# openadc_ztex.net
KiCad netlist of a schematic drawn in EAGLE
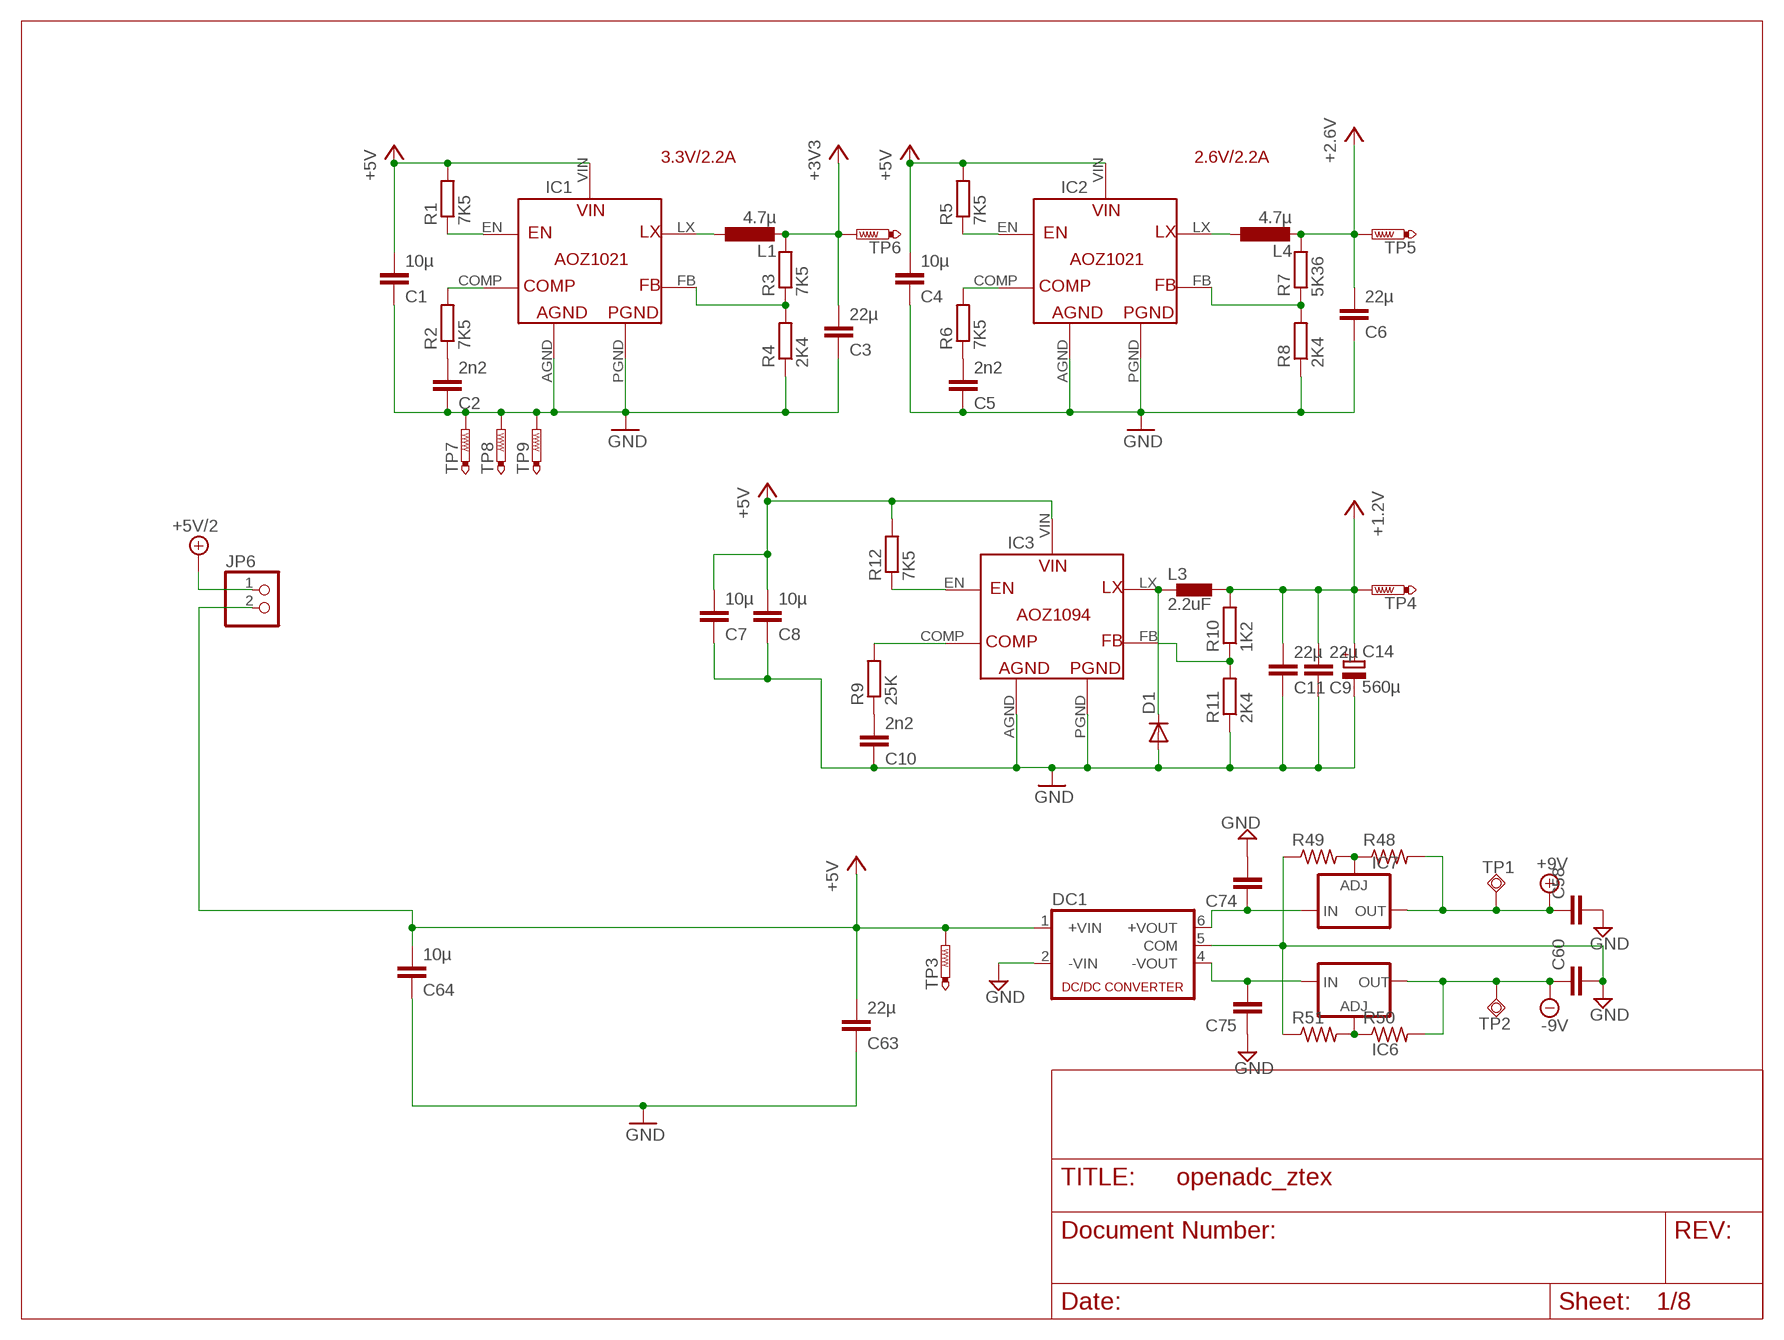
[diagram p0: schematic, sheet 1]
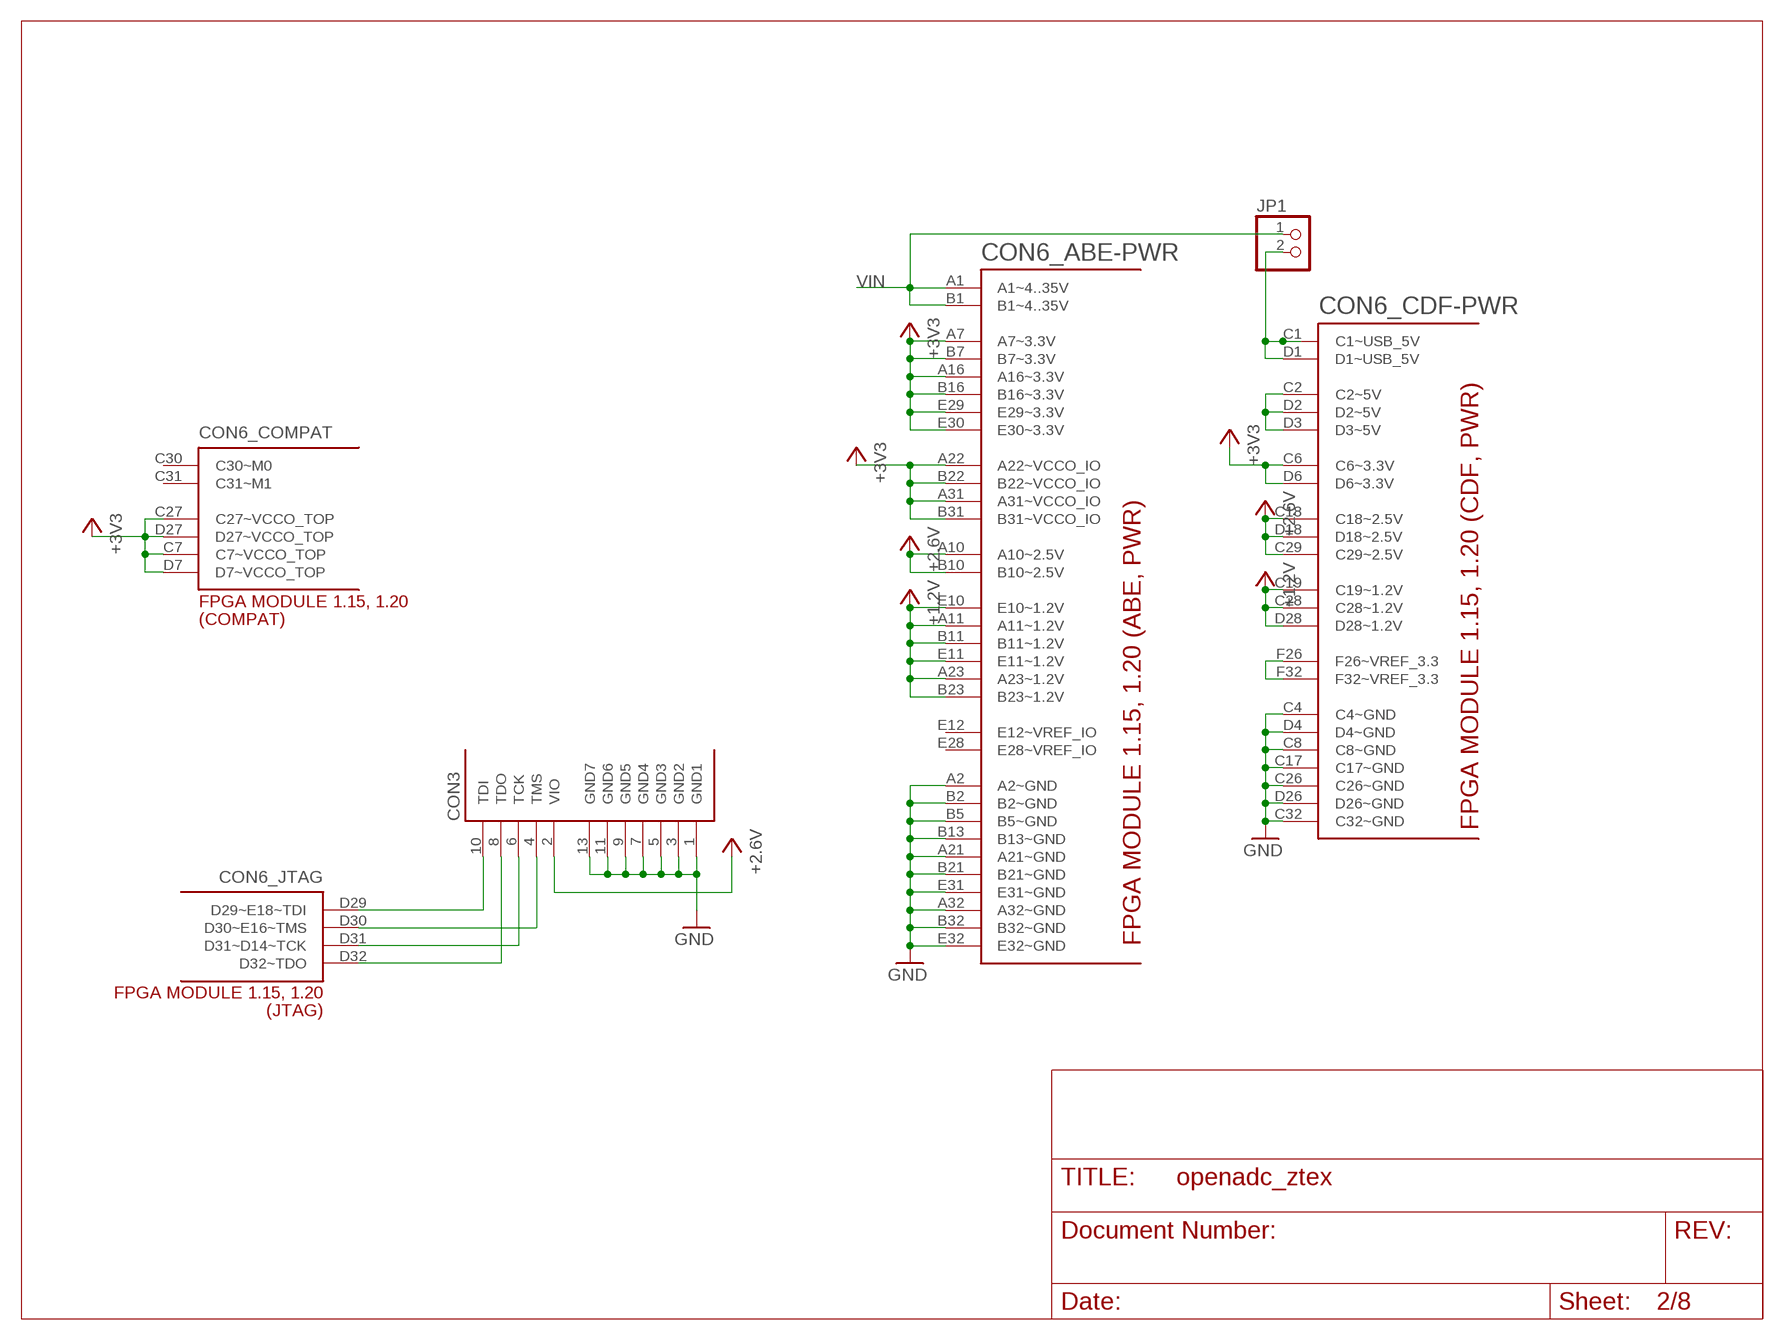
[diagram p1: schematic, sheet 2]
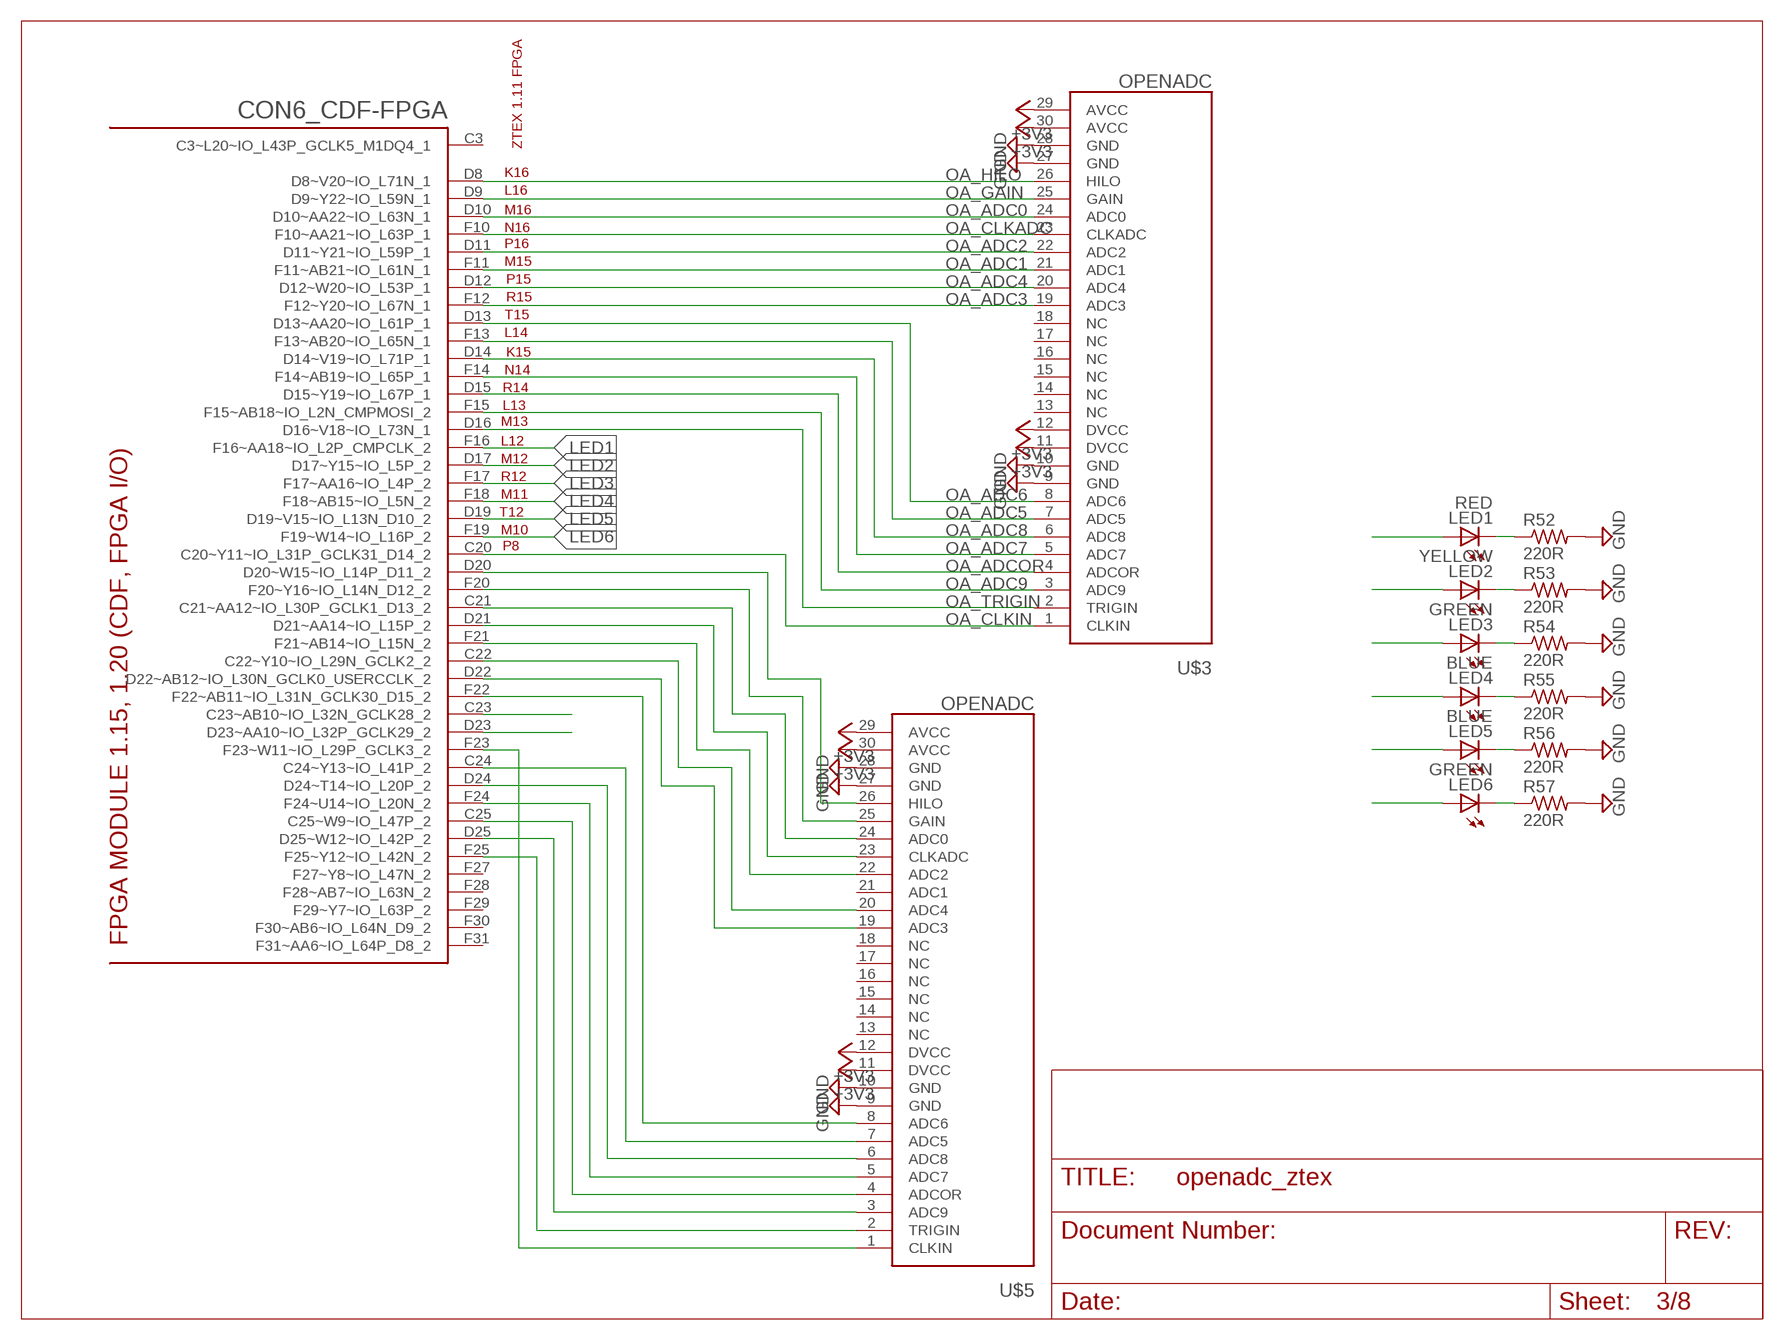
[diagram p2: schematic, sheet 3]
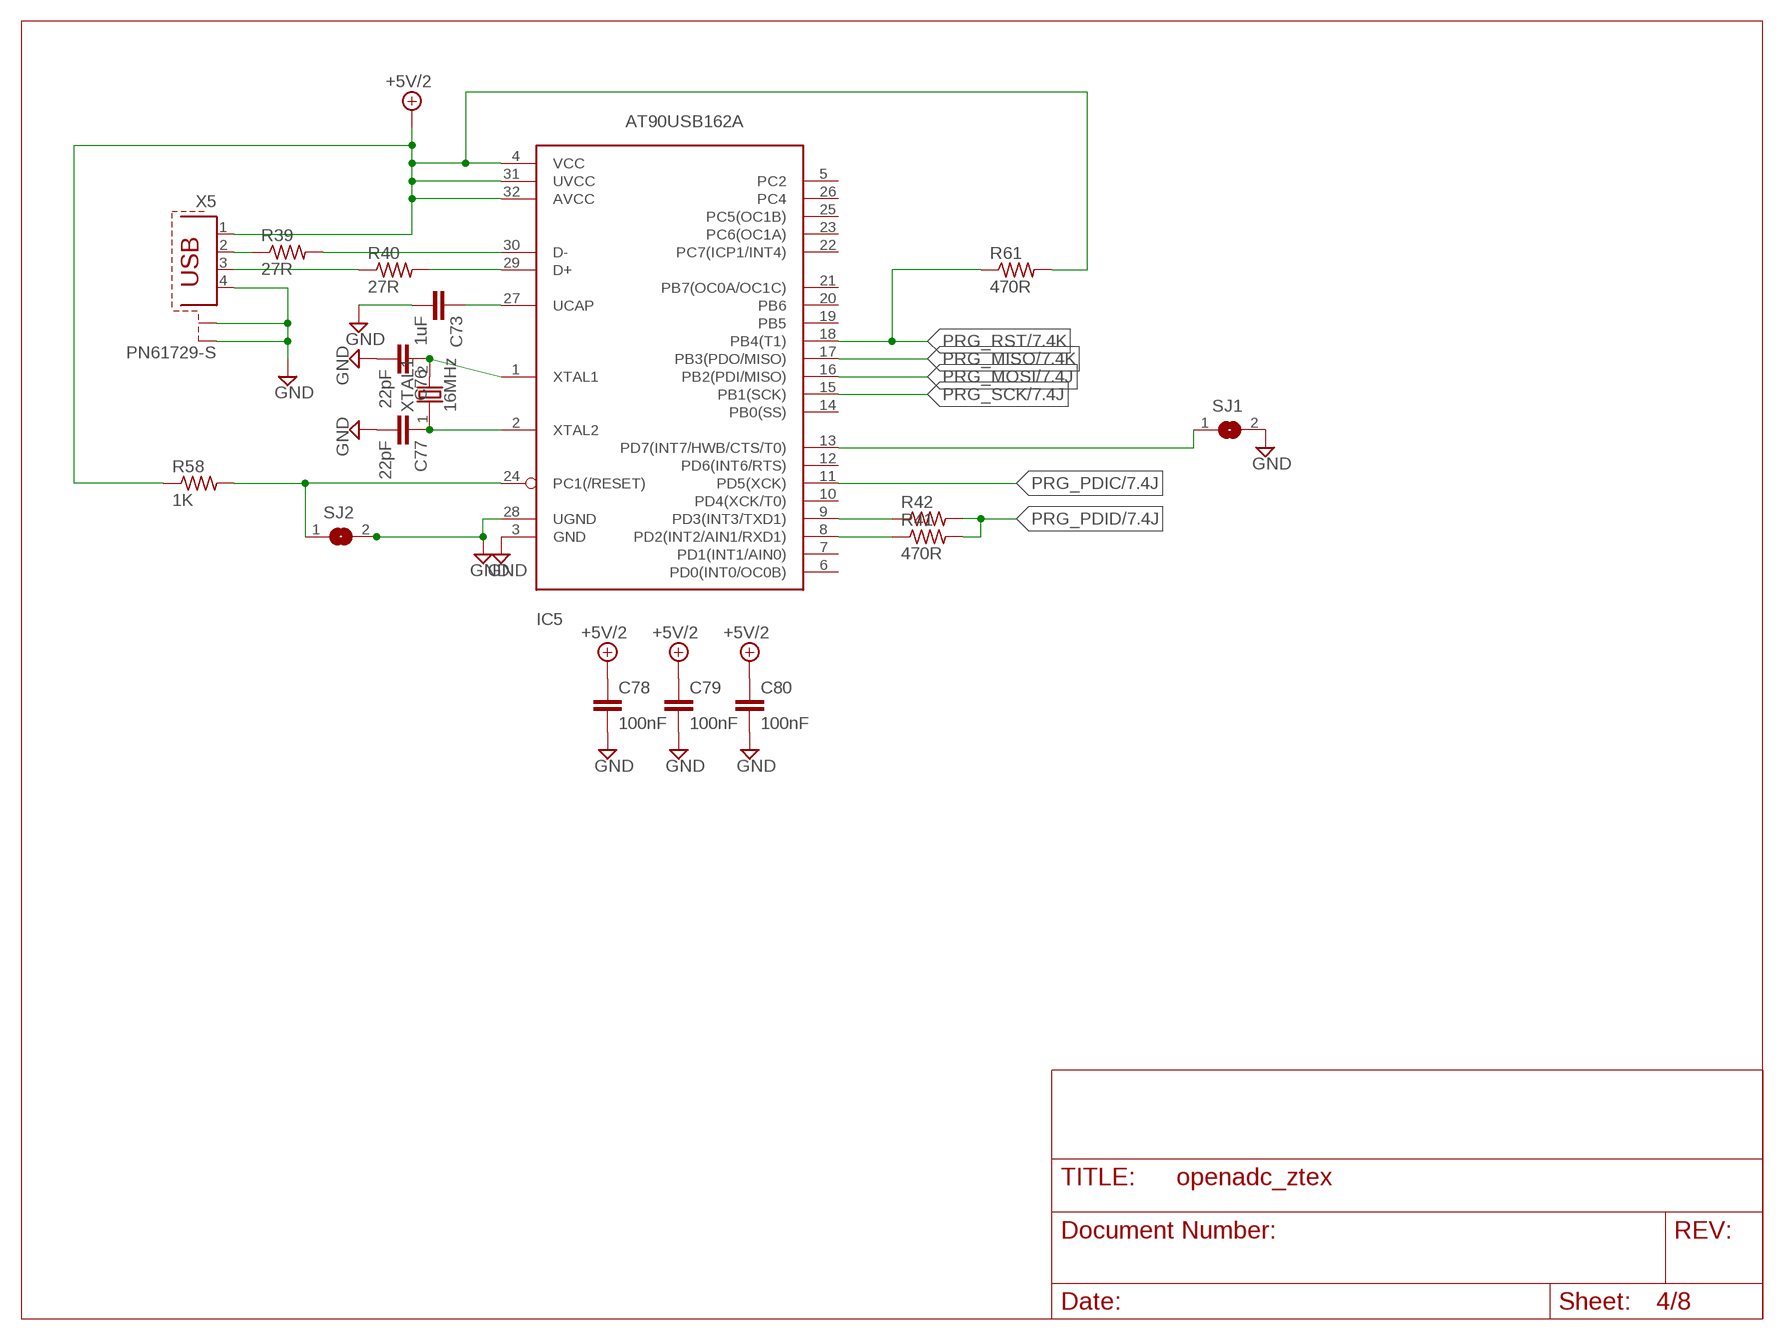
[diagram p3: schematic, sheet 4]
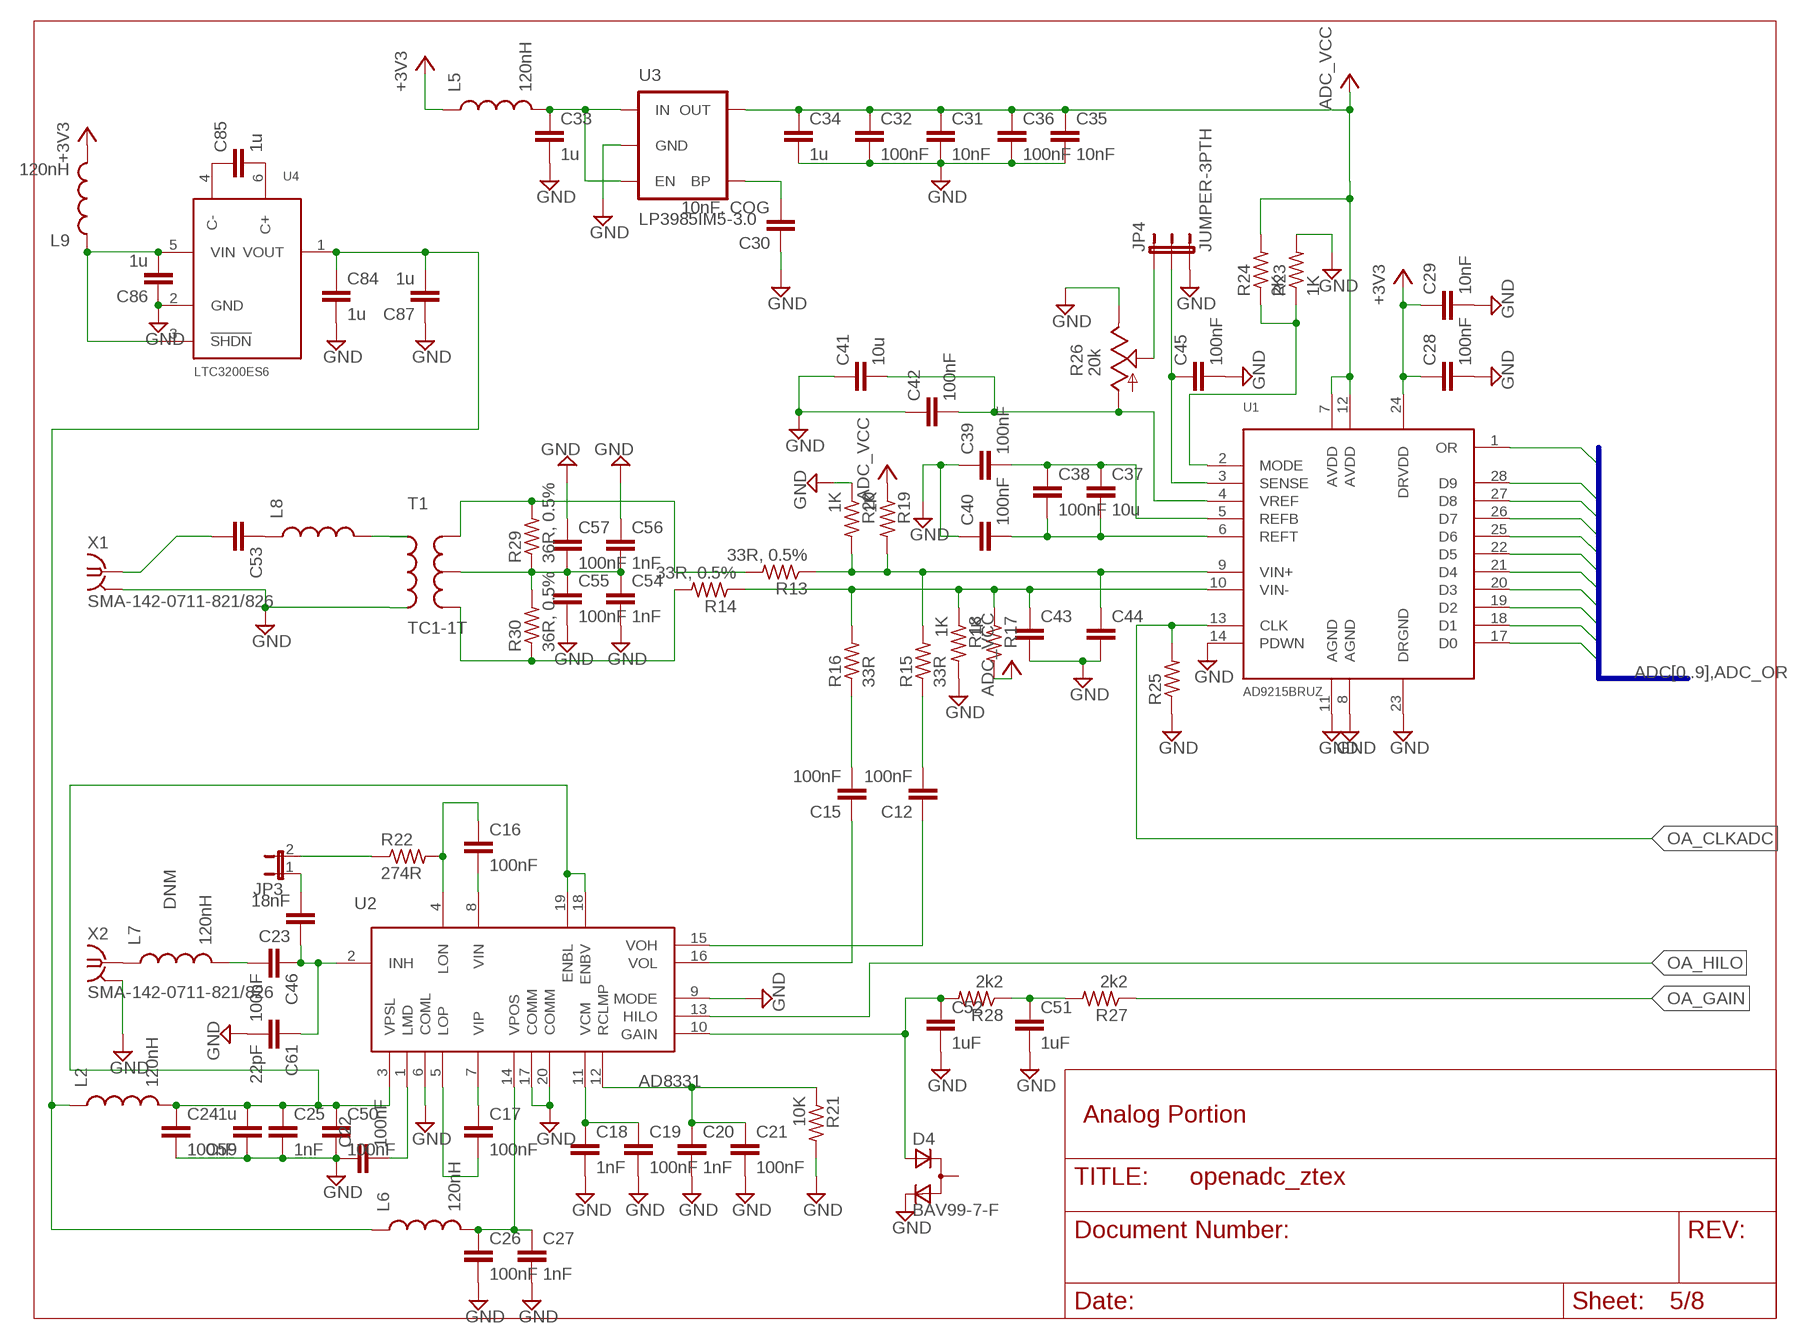
[diagram p4: schematic, sheet 5]
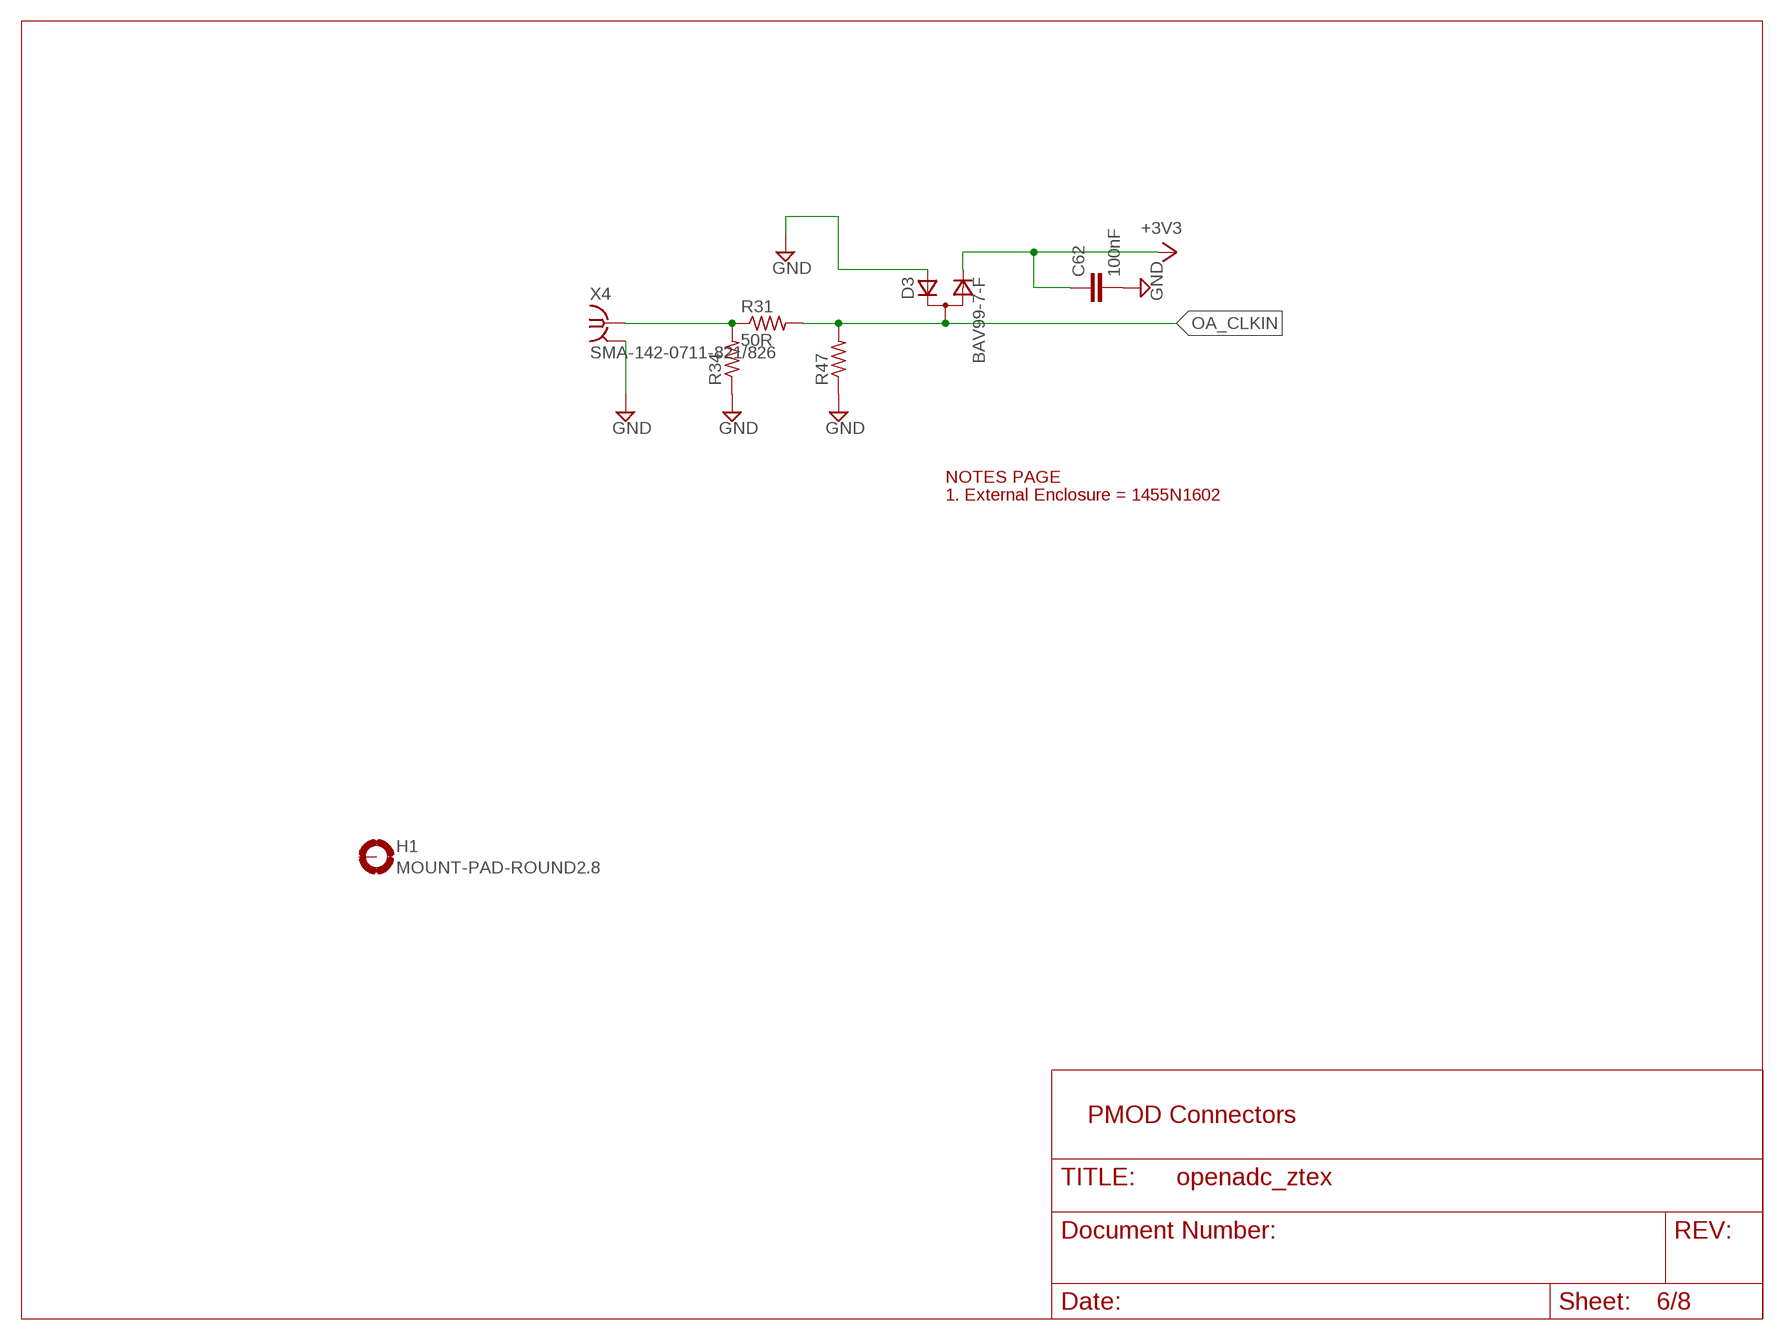
[diagram p5: schematic, sheet 6]
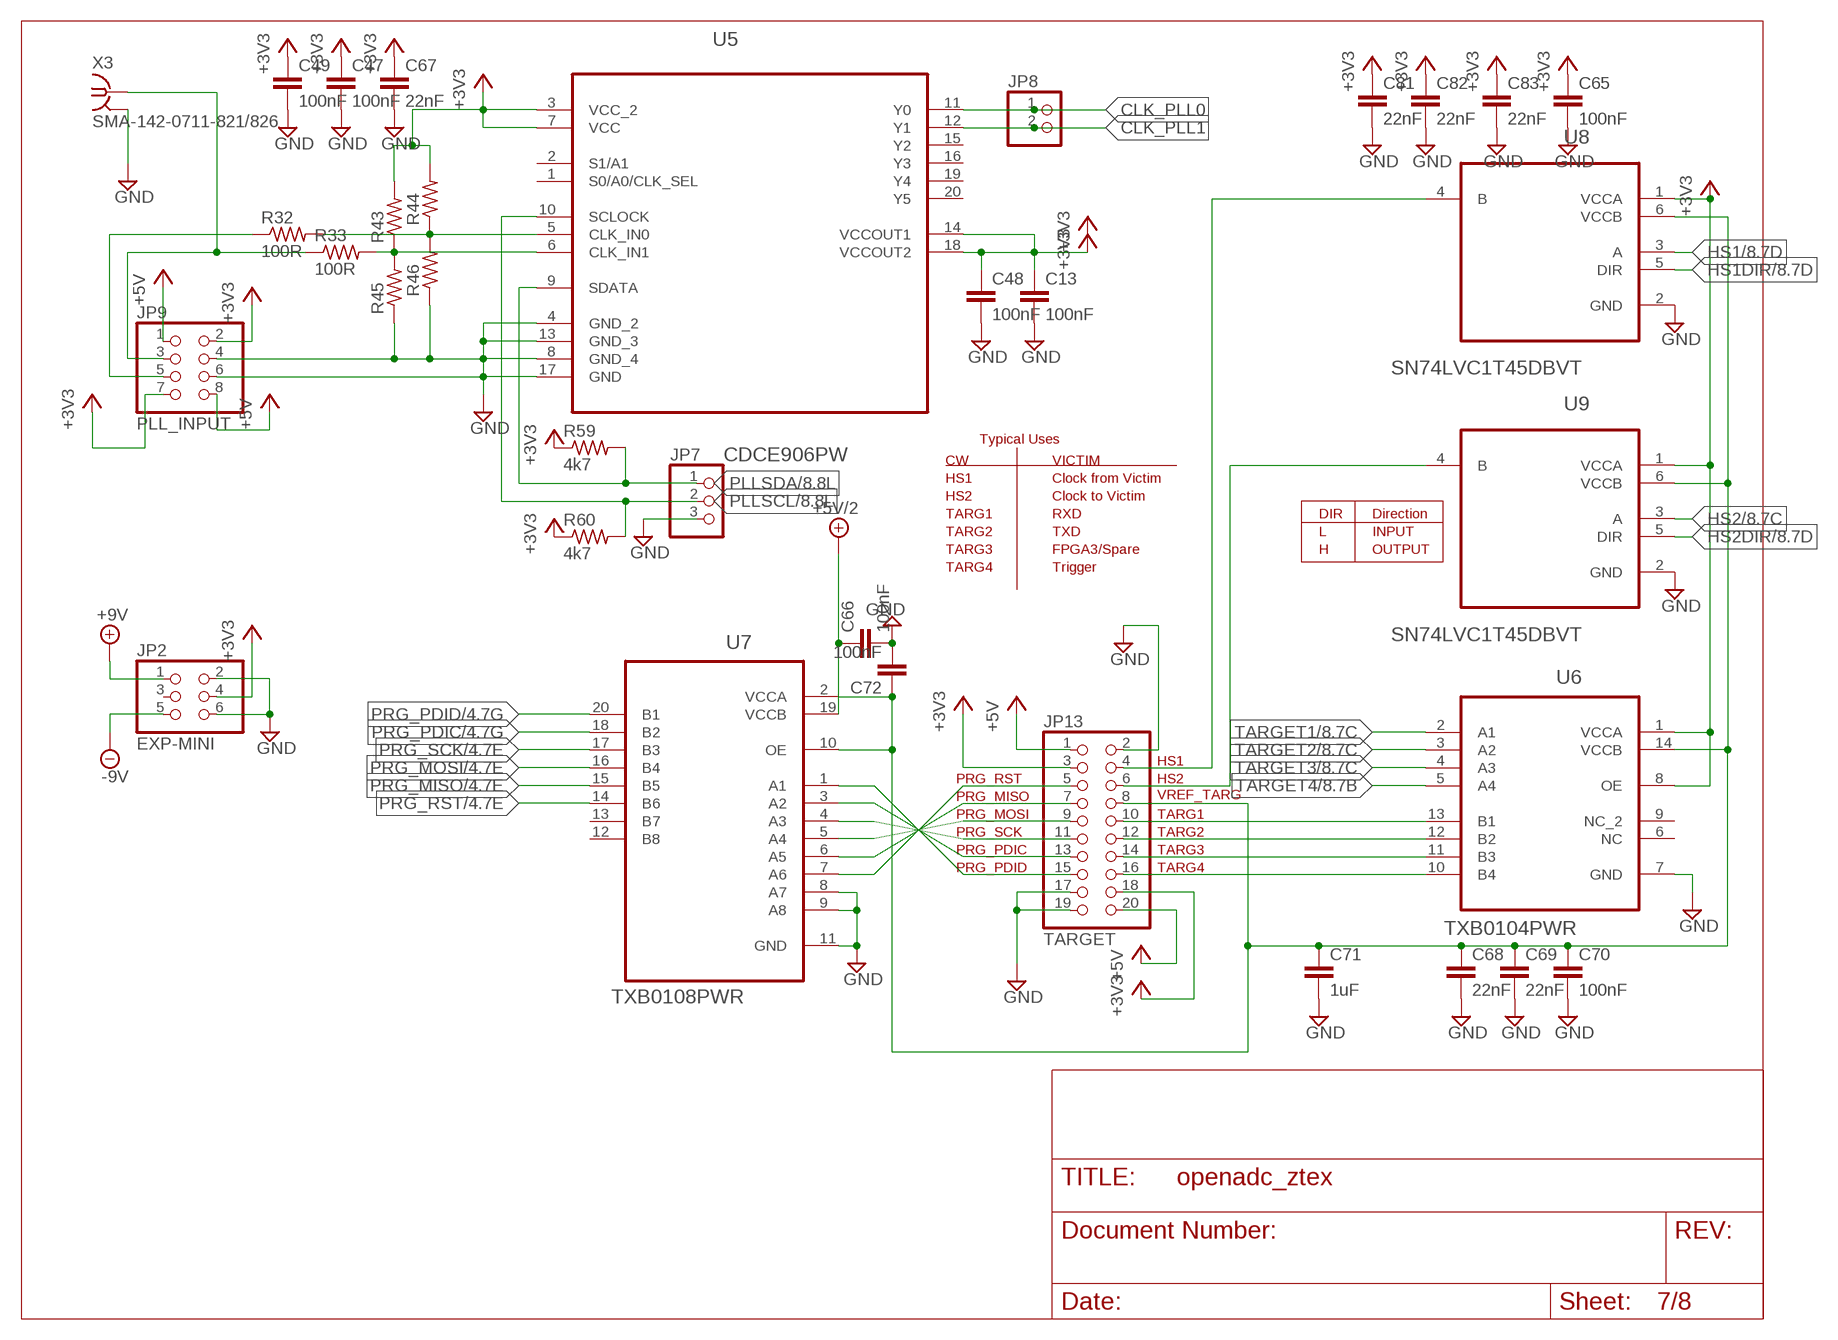
[diagram p6: schematic, sheet 7]
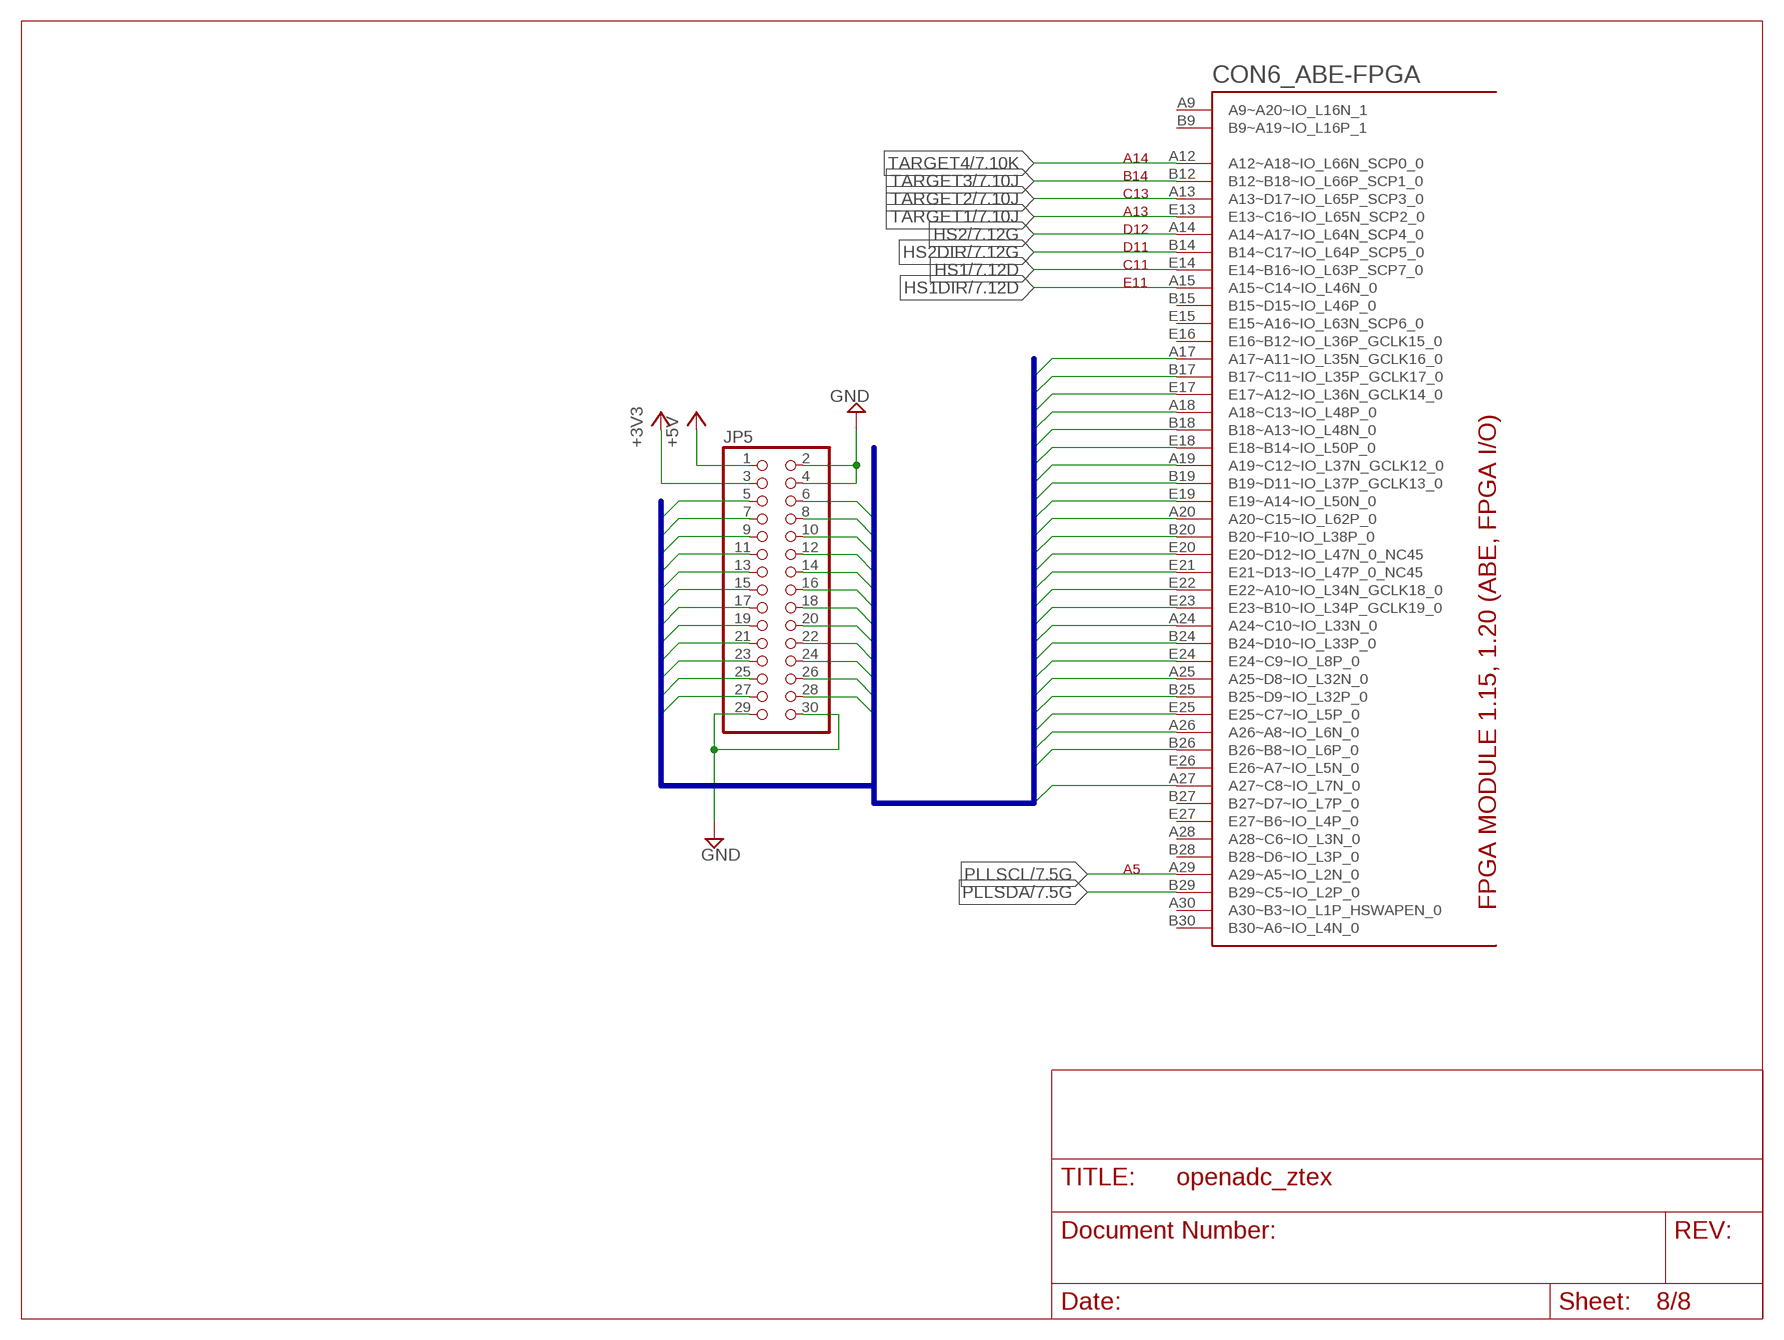
[diagram p7: schematic, sheet 8]

(export (version "E")
  (design (tool "Eeschema 10.0.6"))
  (components
    (comp (ref "C62")
      (value "100nF")
      (footprint "eagle-import:C0603")
      (libsource (lib "eagle-import") (part "C-EUC0603"))
    )
    (comp (ref "D3")
      (value "BAV99-7-F")
      (footprint "eagle-import:SOT-23")
      (libsource (lib "eagle-import") (part "D_ACACSOT23"))
    )
    (comp (ref "H1")
      (value "MOUNT-PAD-ROUND2.8")
      (footprint "eagle-import:2,8-PAD")
      (libsource (lib "eagle-import") (part "MOUNT-PAD-ROUND2.8"))
    )
    (comp (ref "R31")
      (value "50R")
      (footprint "eagle-import:R0805")
      (libsource (lib "eagle-import") (part "R-US_R0805"))
    )
    (comp (ref "R34")
      (value "R-US_R0805")
      (footprint "eagle-import:R0805")
      (libsource (lib "eagle-import") (part "R-US_R0805"))
    )
    (comp (ref "R47")
      (value "R-US_R0805")
      (footprint "eagle-import:R0805")
      (libsource (lib "eagle-import") (part "R-US_R0805"))
    )
    (comp (ref "X4")
      (value "SMA-142-0711-821/826")
      (footprint "eagle-import:J502-ND-142-0711-821_826")
      (fields (field (name "MF") "JOHNSON COMPONENTS") (field (name "MPN") "142-0711-821"))
      (libsource (lib "eagle-import") (part "SMA-142-0711-821/826"))
    )
    (comp (ref "C12")
      (value "100nF")
      (footprint "eagle-import:C0603K")
      (libsource (lib "eagle-import") (part "rcl_C-EUC0603K"))
    )
    (comp (ref "C15")
      (value "100nF")
      (footprint "eagle-import:C0603K")
      (libsource (lib "eagle-import") (part "rcl_C-EUC0603K"))
    )
    (comp (ref "C16")
      (value "100nF")
      (footprint "eagle-import:C0402")
      (libsource (lib "eagle-import") (part "rcl_C-EUC0402"))
    )
    (comp (ref "C17")
      (value "100nF")
      (footprint "eagle-import:C0402")
      (libsource (lib "eagle-import") (part "rcl_C-EUC0402"))
    )
    (comp (ref "C18")
      (value "1nF")
      (footprint "eagle-import:C0402")
      (fields (field (name "PART#") "C1005X7R1E102K"))
      (libsource (lib "eagle-import") (part "rcl_C-EUC0402"))
    )
    (comp (ref "C19")
      (value "100nF")
      (footprint "eagle-import:C0402")
      (fields (field (name "PART#") "GRM155R61A104KA01D"))
      (libsource (lib "eagle-import") (part "rcl_C-EUC0402"))
    )
    (comp (ref "C20")
      (value "1nF")
      (footprint "eagle-import:C0402")
      (fields (field (name "PART#") "C1005X7R1E102K"))
      (libsource (lib "eagle-import") (part "rcl_C-EUC0402"))
    )
    (comp (ref "C21")
      (value "100nF")
      (footprint "eagle-import:C0402")
      (fields (field (name "PART#") "GRM155R61A104KA01D"))
      (libsource (lib "eagle-import") (part "rcl_C-EUC0402"))
    )
    (comp (ref "C22")
      (value "100nF")
      (footprint "eagle-import:C0402")
      (fields (field (name "PART#") "GRM155R61A104KA01D"))
      (libsource (lib "eagle-import") (part "rcl_C-EUC0402"))
    )
    (comp (ref "C23")
      (value "18nF")
      (footprint "eagle-import:C0603")
      (libsource (lib "eagle-import") (part "rcl_C-EUC0603"))
    )
    (comp (ref "C24")
      (value "100nF")
      (footprint "eagle-import:C0402")
      (fields (field (name "PART#") "GRM155R61A104KA01D"))
      (libsource (lib "eagle-import") (part "rcl_C-EUC0402"))
    )
    (comp (ref "C25")
      (value "1nF")
      (footprint "eagle-import:C0402")
      (fields (field (name "PART#") "C1005X7R1E102K"))
      (libsource (lib "eagle-import") (part "rcl_C-EUC0402"))
    )
    (comp (ref "C26")
      (value "100nF")
      (footprint "eagle-import:C0402")
      (fields (field (name "PART#") "GRM155R61A104KA01D"))
      (libsource (lib "eagle-import") (part "rcl_C-EUC0402"))
    )
    (comp (ref "C27")
      (value "1nF")
      (footprint "eagle-import:C0402")
      (fields (field (name "PART#") "C1005X7R1E102K"))
      (libsource (lib "eagle-import") (part "rcl_C-EUC0402"))
    )
    (comp (ref "C28")
      (value "100nF")
      (footprint "eagle-import:C0402")
      (fields (field (name "PART#") "GRM155R61A104KA01D"))
      (libsource (lib "eagle-import") (part "rcl_C-EUC0402"))
    )
    (comp (ref "C29")
      (value "10nF")
      (footprint "eagle-import:C0402")
      (libsource (lib "eagle-import") (part "rcl_C-EUC0402"))
    )
    (comp (ref "C30")
      (value "10nF, COG")
      (footprint "eagle-import:C0402")
      (libsource (lib "eagle-import") (part "rcl_C-EUC0402"))
    )
    (comp (ref "C31")
      (value "10nF")
      (footprint "eagle-import:C0402")
      (fields (field (name "PART#") "GRM155R71E103KA01D"))
      (libsource (lib "eagle-import") (part "rcl_C-EUC0402"))
    )
    (comp (ref "C32")
      (value "100nF")
      (footprint "eagle-import:C0402")
      (fields (field (name "PART#") "GRM155R61A104KA01D"))
      (libsource (lib "eagle-import") (part "rcl_C-EUC0402"))
    )
    (comp (ref "C33")
      (value "1u")
      (footprint "eagle-import:C0603")
      (fields (field (name "PART#") "GRM188R61A105KA61D"))
      (libsource (lib "eagle-import") (part "rcl_C-EUC0603"))
    )
    (comp (ref "C34")
      (value "1u")
      (footprint "eagle-import:C0603")
      (fields (field (name "PART#") "GRM188R61A105KA61D"))
      (libsource (lib "eagle-import") (part "rcl_C-EUC0603"))
    )
    (comp (ref "C35")
      (value "10nF")
      (footprint "eagle-import:C0402")
      (fields (field (name "PART#") "GRM155R71E103KA01D"))
      (libsource (lib "eagle-import") (part "rcl_C-EUC0402"))
    )
    (comp (ref "C36")
      (value "100nF")
      (footprint "eagle-import:C0402")
      (fields (field (name "PART#") "GRM155R61A104KA01D"))
      (libsource (lib "eagle-import") (part "rcl_C-EUC0402"))
    )
    (comp (ref "C37")
      (value "10u")
      (footprint "eagle-import:C0603")
      (libsource (lib "eagle-import") (part "rcl_C-EUC0603"))
    )
    (comp (ref "C38")
      (value "100nF")
      (footprint "eagle-import:C0402")
      (fields (field (name "PART#") "GRM155R61A104KA01D"))
      (libsource (lib "eagle-import") (part "rcl_C-EUC0402"))
    )
    (comp (ref "C39")
      (value "100nF")
      (footprint "eagle-import:C0402")
      (fields (field (name "PART#") "GRM155R61A104KA01D"))
      (libsource (lib "eagle-import") (part "rcl_C-EUC0402"))
    )
    (comp (ref "C40")
      (value "100nF")
      (footprint "eagle-import:C0402")
      (fields (field (name "PART#") "GRM155R61A104KA01D"))
      (libsource (lib "eagle-import") (part "rcl_C-EUC0402"))
    )
    (comp (ref "C41")
      (value "10u")
      (footprint "eagle-import:C0603")
      (libsource (lib "eagle-import") (part "rcl_C-EUC0603"))
    )
    (comp (ref "C42")
      (value "100nF")
      (footprint "eagle-import:C0402")
      (fields (field (name "PART#") "GRM155R61A104KA01D"))
      (libsource (lib "eagle-import") (part "rcl_C-EUC0402"))
    )
    (comp (ref "C43")
      (value "C-EUC0402")
      (footprint "eagle-import:C0402")
      (libsource (lib "eagle-import") (part "rcl_C-EUC0402"))
    )
    (comp (ref "C44")
      (value "C-EUC0402")
      (footprint "eagle-import:C0402")
      (libsource (lib "eagle-import") (part "rcl_C-EUC0402"))
    )
    (comp (ref "C45")
      (value "100nF")
      (footprint "eagle-import:C0402")
      (fields (field (name "PART#") "GRM155R61A104KA01D"))
      (libsource (lib "eagle-import") (part "rcl_C-EUC0402"))
    )
    (comp (ref "C46")
      (value "100nF")
      (footprint "eagle-import:C0603K")
      (libsource (lib "eagle-import") (part "rcl_C-EUC0603K"))
    )
    (comp (ref "C50")
      (value "100nF")
      (footprint "eagle-import:C0402")
      (fields (field (name "PART#") "GRM155R61A104KA01D"))
      (libsource (lib "eagle-import") (part "rcl_C-EUC0402"))
    )
    (comp (ref "C51")
      (value "1uF")
      (footprint "eagle-import:C0603")
      (libsource (lib "eagle-import") (part "rcl_C-EUC0603"))
    )
    (comp (ref "C52")
      (value "1uF")
      (footprint "eagle-import:C0603")
      (libsource (lib "eagle-import") (part "rcl_C-EUC0603"))
    )
    (comp (ref "C53")
      (value "C-EUC0603K")
      (footprint "eagle-import:C0603K")
      (libsource (lib "eagle-import") (part "rcl_C-EUC0603K"))
    )
    (comp (ref "C54")
      (value "1nF")
      (footprint "eagle-import:C0402")
      (fields (field (name "PART#") "C1005X7R1E102K"))
      (libsource (lib "eagle-import") (part "rcl_C-EUC0402"))
    )
    (comp (ref "C55")
      (value "100nF")
      (footprint "eagle-import:C0402")
      (fields (field (name "PART#") "GRM155R61A104KA01D"))
      (libsource (lib "eagle-import") (part "rcl_C-EUC0402"))
    )
    (comp (ref "C56")
      (value "1nF")
      (footprint "eagle-import:C0402")
      (fields (field (name "PART#") "C1005X7R1E102K"))
      (libsource (lib "eagle-import") (part "rcl_C-EUC0402"))
    )
    (comp (ref "C57")
      (value "100nF")
      (footprint "eagle-import:C0402")
      (fields (field (name "PART#") "GRM155R61A104KA01D"))
      (libsource (lib "eagle-import") (part "rcl_C-EUC0402"))
    )
    (comp (ref "C59")
      (value "1u")
      (footprint "eagle-import:C0402")
      (fields (field (name "PART#") "GRM188R61A105KA61D"))
      (libsource (lib "eagle-import") (part "rcl_C-EUC0402"))
    )
    (comp (ref "C61")
      (value "22pF")
      (footprint "eagle-import:C0603")
      (libsource (lib "eagle-import") (part "rcl_C-EUC0603"))
    )
    (comp (ref "C84")
      (value "1u")
      (footprint "eagle-import:C0603")
      (fields (field (name "PART#") "GRM188R61A105KA61D"))
      (libsource (lib "eagle-import") (part "rcl_C-EUC0603"))
    )
    (comp (ref "C85")
      (value "1u")
      (footprint "eagle-import:C0603")
      (fields (field (name "PART#") "GRM188R61A105KA61D"))
      (libsource (lib "eagle-import") (part "rcl_C-EUC0603"))
    )
    (comp (ref "C86")
      (value "1u")
      (footprint "eagle-import:C0603")
      (fields (field (name "PART#") "GRM188R61A105KA61D"))
      (libsource (lib "eagle-import") (part "rcl_C-EUC0603"))
    )
    (comp (ref "C87")
      (value "1u")
      (footprint "eagle-import:C0603")
      (fields (field (name "PART#") "GRM188R61A105KA61D"))
      (libsource (lib "eagle-import") (part "rcl_C-EUC0603"))
    )
    (comp (ref "D4")
      (value "BAV99-7-F")
      (footprint "eagle-import:SOT-23")
      (libsource (lib "eagle-import") (part "D_ACACSOT23"))
    )
    (comp (ref "JP3")
      (value "JUMPER-2SMD-NC")
      (footprint "eagle-import:SJ_2S")
      (libsource (lib "eagle-import") (part "JUMPER-2SMD-NC"))
    )
    (comp (ref "JP4")
      (value "JUMPER-3PTH")
      (footprint "eagle-import:1X03")
      (libsource (lib "eagle-import") (part "JUMPER-3PTH"))
    )
    (comp (ref "L2")
      (value "120nH")
      (footprint "eagle-import:0603")
      (fields (field (name "PART#") "MLF1608DR12M"))
      (libsource (lib "eagle-import") (part "INDUCTOR0603"))
    )
    (comp (ref "L5")
      (value "120nH")
      (footprint "eagle-import:0603")
      (libsource (lib "eagle-import") (part "INDUCTOR0603"))
    )
    (comp (ref "L6")
      (value "120nH")
      (footprint "eagle-import:0603")
      (libsource (lib "eagle-import") (part "INDUCTOR0603"))
    )
    (comp (ref "L7")
      (value "120nH")
      (footprint "eagle-import:0603")
      (libsource (lib "eagle-import") (part "INDUCTOR0603"))
    )
    (comp (ref "L8")
      (value "INDUCTOR0603")
      (footprint "eagle-import:0603")
      (libsource (lib "eagle-import") (part "INDUCTOR0603"))
    )
    (comp (ref "L9")
      (value "120nH")
      (footprint "eagle-import:0603")
      (libsource (lib "eagle-import") (part "INDUCTOR0603"))
    )
    (comp (ref "R13")
      (value "33R, 0.5%")
      (footprint "eagle-import:R0603")
      (libsource (lib "eagle-import") (part "R-US_R0603"))
    )
    (comp (ref "R14")
      (value "33R, 0.5%")
      (footprint "eagle-import:R0603")
      (libsource (lib "eagle-import") (part "R-US_R0603"))
    )
    (comp (ref "R15")
      (value "33R")
      (footprint "eagle-import:R0603")
      (libsource (lib "eagle-import") (part "R-US_R0603"))
    )
    (comp (ref "R16")
      (value "33R")
      (footprint "eagle-import:R0603")
      (libsource (lib "eagle-import") (part "R-US_R0603"))
    )
    (comp (ref "R17")
      (value "1K")
      (footprint "eagle-import:R0402")
      (libsource (lib "eagle-import") (part "R-US_R0402"))
    )
    (comp (ref "R18")
      (value "1K")
      (footprint "eagle-import:R0402")
      (libsource (lib "eagle-import") (part "R-US_R0402"))
    )
    (comp (ref "R19")
      (value "1K")
      (footprint "eagle-import:R0402")
      (libsource (lib "eagle-import") (part "R-US_R0402"))
    )
    (comp (ref "R20")
      (value "1K")
      (footprint "eagle-import:R0402")
      (libsource (lib "eagle-import") (part "R-US_R0402"))
    )
    (comp (ref "R21")
      (value "10K")
      (footprint "eagle-import:R0603")
      (libsource (lib "eagle-import") (part "R-US_R0603"))
    )
    (comp (ref "R22")
      (value "274R")
      (footprint "eagle-import:R0603")
      (libsource (lib "eagle-import") (part "R-US_R0603"))
    )
    (comp (ref "R23")
      (value "1K")
      (footprint "eagle-import:R0402")
      (libsource (lib "eagle-import") (part "R-US_R0402"))
    )
    (comp (ref "R24")
      (value "2K")
      (footprint "eagle-import:R0603")
      (libsource (lib "eagle-import") (part "R-US_R0603"))
    )
    (comp (ref "R25")
      (value "R-US_R0603")
      (footprint "eagle-import:R0603")
      (libsource (lib "eagle-import") (part "R-US_R0603"))
    )
    (comp (ref "R26")
      (value "20k")
      (footprint "eagle-import:3361P")
      (fields (field (name "PART#") "3361P-1-203GLF"))
      (libsource (lib "eagle-import") (part "TRIM_US-3361P"))
    )
    (comp (ref "R27")
      (value "2k2")
      (footprint "eagle-import:R0603")
      (libsource (lib "eagle-import") (part "R-US_R0603"))
    )
    (comp (ref "R28")
      (value "2k2")
      (footprint "eagle-import:R0603")
      (libsource (lib "eagle-import") (part "R-US_R0603"))
    )
    (comp (ref "R29")
      (value "36R, 0.5%")
      (footprint "eagle-import:R0603")
      (libsource (lib "eagle-import") (part "R-US_R0603"))
    )
    (comp (ref "R30")
      (value "36R, 0.5%")
      (footprint "eagle-import:R0603")
      (libsource (lib "eagle-import") (part "R-US_R0603"))
    )
    (comp (ref "T1")
      (value "TC1-1T")
      (footprint "eagle-import:AT224-1A")
      (libsource (lib "eagle-import") (part "TC1-1T"))
    )
    (comp (ref "U1")
      (value "AD9215BRUZ")
      (footprint "eagle-import:TSSOP28")
      (libsource (lib "eagle-import") (part "AD9215BRUZ"))
    )
    (comp (ref "U2")
      (value "AD8331")
      (footprint "eagle-import:QSOP20")
      (fields (field (name "PART#") "AD8331ARQZ"))
      (libsource (lib "eagle-import") (part "AD8331"))
    )
    (comp (ref "U3")
      (value "LP3985IM5-3.0")
      (footprint "eagle-import:SOT23-5")
      (libsource (lib "eagle-import") (part "V_REG_LDOSMD"))
    )
    (comp (ref "U4")
      (value "LTC3200ES6")
      (footprint "eagle-import:SOT23-6L")
      (libsource (lib "eagle-import") (part "LTC3200ES6"))
    )
    (comp (ref "X1")
      (value "SMA-142-0711-821/826")
      (footprint "eagle-import:J502-ND-142-0711-821_826")
      (fields (field (name "MF") "JOHNSON COMPONENTS") (field (name "MPN") "142-0711-821"))
      (libsource (lib "eagle-import") (part "SMA-142-0711-821/826"))
    )
    (comp (ref "X2")
      (value "SMA-142-0711-821/826")
      (footprint "eagle-import:J502-ND-142-0711-821_826")
      (fields (field (name "MF") "JOHNSON COMPONENTS") (field (name "MPN") "142-0711-821"))
      (libsource (lib "eagle-import") (part "SMA-142-0711-821/826"))
    )
    (comp (ref "C13")
      (value "100nF")
      (footprint "eagle-import:C0603")
      (libsource (lib "eagle-import") (part "rcl_C-EUC0603"))
    )
    (comp (ref "C47")
      (value "100nF")
      (footprint "eagle-import:C0603")
      (libsource (lib "eagle-import") (part "rcl_C-EUC0603"))
    )
    (comp (ref "C48")
      (value "100nF")
      (footprint "eagle-import:C0603")
      (libsource (lib "eagle-import") (part "rcl_C-EUC0603"))
    )
    (comp (ref "C49")
      (value "100nF")
      (footprint "eagle-import:C0603")
      (libsource (lib "eagle-import") (part "rcl_C-EUC0603"))
    )
    (comp (ref "C65")
      (value "100nF")
      (footprint "eagle-import:C0603")
      (libsource (lib "eagle-import") (part "rcl_C-EUC0603"))
    )
    (comp (ref "C66")
      (value "100nF")
      (footprint "eagle-import:C0603")
      (libsource (lib "eagle-import") (part "rcl_C-EUC0603"))
    )
    (comp (ref "C67")
      (value "22nF")
      (footprint "eagle-import:C0603")
      (libsource (lib "eagle-import") (part "rcl_C-EUC0603"))
    )
    (comp (ref "C68")
      (value "22nF")
      (footprint "eagle-import:C0603")
      (libsource (lib "eagle-import") (part "rcl_C-EUC0603"))
    )
    (comp (ref "C69")
      (value "22nF")
      (footprint "eagle-import:C0603")
      (libsource (lib "eagle-import") (part "rcl_C-EUC0603"))
    )
    (comp (ref "C70")
      (value "100nF")
      (footprint "eagle-import:C0603")
      (libsource (lib "eagle-import") (part "rcl_C-EUC0603"))
    )
    (comp (ref "C71")
      (value "1uF")
      (footprint "eagle-import:C0603")
      (libsource (lib "eagle-import") (part "rcl_C-EUC0603"))
    )
    (comp (ref "C72")
      (value "100nF")
      (footprint "eagle-import:C0603")
      (libsource (lib "eagle-import") (part "rcl_C-EUC0603"))
    )
    (comp (ref "C81")
      (value "22nF")
      (footprint "eagle-import:C0603")
      (libsource (lib "eagle-import") (part "rcl_C-EUC0603"))
    )
    (comp (ref "C82")
      (value "22nF")
      (footprint "eagle-import:C0603")
      (libsource (lib "eagle-import") (part "rcl_C-EUC0603"))
    )
    (comp (ref "C83")
      (value "22nF")
      (footprint "eagle-import:C0603")
      (libsource (lib "eagle-import") (part "rcl_C-EUC0603"))
    )
    (comp (ref "JP2")
      (value "EXP-MINI")
      (footprint "eagle-import:2X03_90")
      (libsource (lib "eagle-import") (part "PINHD-2X3/90"))
    )
    (comp (ref "JP7")
      (value "PINHD-1X3")
      (footprint "eagle-import:1X03")
      (libsource (lib "eagle-import") (part "PINHD-1X3"))
    )
    (comp (ref "JP8")
      (value "PINHD-1X2")
      (footprint "eagle-import:1X02")
      (libsource (lib "eagle-import") (part "PINHD-1X2"))
    )
    (comp (ref "JP9")
      (value "PLL_INPUT")
      (footprint "eagle-import:2X04_90")
      (libsource (lib "eagle-import") (part "PINHD-2X4/90"))
    )
    (comp (ref "JP13")
      (value "TARGET")
      (footprint "eagle-import:2X10_90")
      (libsource (lib "eagle-import") (part "PINHD-2X10/90"))
    )
    (comp (ref "R32")
      (value "100R")
      (footprint "eagle-import:R0603")
      (libsource (lib "eagle-import") (part "resistor_R-US_R0603"))
    )
    (comp (ref "R33")
      (value "100R")
      (footprint "eagle-import:R0603")
      (libsource (lib "eagle-import") (part "resistor_R-US_R0603"))
    )
    (comp (ref "R43")
      (value "R-US_R0603")
      (footprint "eagle-import:R0603")
      (libsource (lib "eagle-import") (part "resistor_R-US_R0603"))
    )
    (comp (ref "R44")
      (value "R-US_R0603")
      (footprint "eagle-import:R0603")
      (libsource (lib "eagle-import") (part "resistor_R-US_R0603"))
    )
    (comp (ref "R45")
      (value "R-US_R0603")
      (footprint "eagle-import:R0603")
      (libsource (lib "eagle-import") (part "resistor_R-US_R0603"))
    )
    (comp (ref "R46")
      (value "R-US_R0603")
      (footprint "eagle-import:R0603")
      (libsource (lib "eagle-import") (part "resistor_R-US_R0603"))
    )
    (comp (ref "R59")
      (value "4k7")
      (footprint "eagle-import:R0603")
      (libsource (lib "eagle-import") (part "resistor_R-US_R0603"))
    )
    (comp (ref "R60")
      (value "4k7")
      (footprint "eagle-import:R0603")
      (libsource (lib "eagle-import") (part "resistor_R-US_R0603"))
    )
    (comp (ref "U5")
      (value "CDCE906PW")
      (footprint "eagle-import:SOP65P640X120-20N")
      (libsource (lib "eagle-import") (part "CDCE906PW"))
    )
    (comp (ref "U6")
      (value "TXB0104PWR")
      (footprint "eagle-import:SOP65P640X120-14N")
      (libsource (lib "eagle-import") (part "TXB0104PWR"))
    )
    (comp (ref "U7")
      (value "TXB0108PWR")
      (footprint "eagle-import:SOP65P640X120-20N")
      (libsource (lib "eagle-import") (part "TXB0108PWR"))
    )
    (comp (ref "U8")
      (value "SN74LVC1T45DBVT")
      (footprint "eagle-import:SOT95P280X145-6N")
      (libsource (lib "eagle-import") (part "SN74LVC1T45DBVT"))
    )
    (comp (ref "U9")
      (value "SN74LVC1T45DBVT")
      (footprint "eagle-import:SOT95P280X145-6N")
      (libsource (lib "eagle-import") (part "SN74LVC1T45DBVT"))
    )
    (comp (ref "X3")
      (value "SMA-142-0711-821/826")
      (footprint "eagle-import:J502-ND-142-0711-821_826")
      (fields (field (name "MF") "JOHNSON COMPONENTS") (field (name "MPN") "142-0711-821"))
      (libsource (lib "eagle-import") (part "SMA-142-0711-821/826"))
    )
    (comp (ref "C73")
      (value "1uF")
      (footprint "eagle-import:C0603")
      (libsource (lib "eagle-import") (part "rcl_C-EUC0603"))
    )
    (comp (ref "C76")
      (value "22pF")
      (footprint "eagle-import:C0603")
      (libsource (lib "eagle-import") (part "rcl_C-EUC0603"))
    )
    (comp (ref "C77")
      (value "22pF")
      (footprint "eagle-import:C0603")
      (libsource (lib "eagle-import") (part "rcl_C-EUC0603"))
    )
    (comp (ref "C78")
      (value "100nF")
      (footprint "eagle-import:C0603")
      (libsource (lib "eagle-import") (part "rcl_C-EUC0603"))
    )
    (comp (ref "C79")
      (value "100nF")
      (footprint "eagle-import:C0603")
      (libsource (lib "eagle-import") (part "rcl_C-EUC0603"))
    )
    (comp (ref "C80")
      (value "100nF")
      (footprint "eagle-import:C0603")
      (libsource (lib "eagle-import") (part "rcl_C-EUC0603"))
    )
    (comp (ref "IC5")
      (value "AT90USB162A")
      (footprint "eagle-import:TQFP32-08")
      (libsource (lib "eagle-import") (part "AT90USB162A"))
    )
    (comp (ref "R39")
      (value "27R")
      (footprint "eagle-import:R0603")
      (libsource (lib "eagle-import") (part "resistor_R-US_R0603"))
    )
    (comp (ref "R40")
      (value "27R")
      (footprint "eagle-import:R0603")
      (libsource (lib "eagle-import") (part "resistor_R-US_R0603"))
    )
    (comp (ref "R41")
      (value "470R")
      (footprint "eagle-import:R0603")
      (libsource (lib "eagle-import") (part "resistor_R-US_R0603"))
    )
    (comp (ref "R42")
      (value "R-US_R0603")
      (footprint "eagle-import:R0603")
      (libsource (lib "eagle-import") (part "resistor_R-US_R0603"))
    )
    (comp (ref "R58")
      (value "1K")
      (footprint "eagle-import:R0603")
      (libsource (lib "eagle-import") (part "resistor_R-US_R0603"))
    )
    (comp (ref "R61")
      (value "470R")
      (footprint "eagle-import:R0603")
      (libsource (lib "eagle-import") (part "resistor_R-US_R0603"))
    )
    (comp (ref "SJ1") (value "SJ") (footprint "eagle-import:SJ") (libsource (lib "eagle-import") (part "SJ")))
    (comp (ref "SJ2") (value "SJ") (footprint "eagle-import:SJ") (libsource (lib "eagle-import") (part "SJ")))
    (comp (ref "X5")
      (value "PN61729-S")
      (footprint "eagle-import:PN61729-S")
      (libsource (lib "eagle-import") (part "PN61729-S"))
    )
    (comp (ref "XTAL1")
      (value "16MHz")
      (footprint "eagle-import:HC-49U")
      (libsource (lib "eagle-import") (part "OSC-XTAL-HC-49U-SMD"))
    )
    (comp (ref "CON6")
      (value "USB-FPGA1.15")
      (footprint "eagle-import:USB-FPGA1.15")
      (libsource (lib "eagle-import") (part "USB-FPGA1.15"))
    )
    (comp (ref "JP5")
      (value "PINHD-2X15/90")
      (footprint "eagle-import:2X15_90")
      (libsource (lib "eagle-import") (part "PINHD-2X15/90"))
    )
    (comp (ref "CON3")
      (value "JTAG")
      (footprint "eagle-import:JTAG")
      (libsource (lib "eagle-import") (part "JTAG"))
    )
    (comp (ref "JP1")
      (value "PINHD-1X2")
      (footprint "eagle-import:1X02")
      (libsource (lib "eagle-import") (part "PINHD-1X2"))
    )
    (comp (ref "LED1")
      (value "RED")
      (footprint "eagle-import:LED-3MM")
      (libsource (lib "eagle-import") (part "LED-3MM"))
    )
    (comp (ref "LED2")
      (value "YELLOW")
      (footprint "eagle-import:LED-3MM")
      (libsource (lib "eagle-import") (part "LED-3MM"))
    )
    (comp (ref "LED3")
      (value "GREEN")
      (footprint "eagle-import:LED-3MM")
      (libsource (lib "eagle-import") (part "LED-3MM"))
    )
    (comp (ref "LED4")
      (value "BLUE")
      (footprint "eagle-import:LED-3MM")
      (libsource (lib "eagle-import") (part "LED-3MM"))
    )
    (comp (ref "LED5")
      (value "BLUE")
      (footprint "eagle-import:LED-3MM")
      (libsource (lib "eagle-import") (part "LED-3MM"))
    )
    (comp (ref "LED6")
      (value "GREEN")
      (footprint "eagle-import:LED-3MM")
      (libsource (lib "eagle-import") (part "LED-3MM"))
    )
    (comp (ref "R52")
      (value "220R")
      (footprint "eagle-import:R0603")
      (libsource (lib "eagle-import") (part "resistor_R-US_R0603"))
    )
    (comp (ref "R53")
      (value "220R")
      (footprint "eagle-import:R0603")
      (libsource (lib "eagle-import") (part "resistor_R-US_R0603"))
    )
    (comp (ref "R54")
      (value "220R")
      (footprint "eagle-import:R0603")
      (libsource (lib "eagle-import") (part "resistor_R-US_R0603"))
    )
    (comp (ref "R55")
      (value "220R")
      (footprint "eagle-import:R0603")
      (libsource (lib "eagle-import") (part "resistor_R-US_R0603"))
    )
    (comp (ref "R56")
      (value "220R")
      (footprint "eagle-import:R0603")
      (libsource (lib "eagle-import") (part "resistor_R-US_R0603"))
    )
    (comp (ref "R57")
      (value "220R")
      (footprint "eagle-import:R0603")
      (libsource (lib "eagle-import") (part "resistor_R-US_R0603"))
    )
    (comp (ref "U$3")
      (value "OPENADC")
      (footprint "eagle-import:OPENADCREV1")
      (libsource (lib "eagle-import") (part "OPENADC"))
    )
    (comp (ref "U$5")
      (value "OPENADC")
      (footprint "eagle-import:OPENADCREV1")
      (libsource (lib "eagle-import") (part "OPENADC"))
    )
    (comp (ref "C1")
      (value "10µ")
      (footprint "eagle-import:C1206")
      (libsource (lib "eagle-import") (part "myrcl_C-EUC1206"))
    )
    (comp (ref "C2")
      (value "2n2")
      (footprint "eagle-import:C0805K")
      (libsource (lib "eagle-import") (part "myrcl_C-EUC0805K"))
    )
    (comp (ref "C3")
      (value "22µ")
      (footprint "eagle-import:C0805K")
      (libsource (lib "eagle-import") (part "myrcl_C-EUC0805K"))
    )
    (comp (ref "C4")
      (value "10µ")
      (footprint "eagle-import:C1206")
      (libsource (lib "eagle-import") (part "myrcl_C-EUC1206"))
    )
    (comp (ref "C5")
      (value "2n2")
      (footprint "eagle-import:C0805K")
      (libsource (lib "eagle-import") (part "myrcl_C-EUC0805K"))
    )
    (comp (ref "C6")
      (value "22µ")
      (footprint "eagle-import:C0805K")
      (libsource (lib "eagle-import") (part "myrcl_C-EUC0805K"))
    )
    (comp (ref "C7")
      (value "10µ")
      (footprint "eagle-import:C1206")
      (libsource (lib "eagle-import") (part "myrcl_C-EUC1206"))
    )
    (comp (ref "C8")
      (value "10µ")
      (footprint "eagle-import:C1206")
      (libsource (lib "eagle-import") (part "myrcl_C-EUC1206"))
    )
    (comp (ref "C9")
      (value "22µ")
      (footprint "eagle-import:C0805K")
      (libsource (lib "eagle-import") (part "myrcl_C-EUC0805K"))
    )
    (comp (ref "C10")
      (value "2n2")
      (footprint "eagle-import:C0805K")
      (libsource (lib "eagle-import") (part "myrcl_C-EUC0805K"))
    )
    (comp (ref "C11")
      (value "22µ")
      (footprint "eagle-import:C0805K")
      (libsource (lib "eagle-import") (part "myrcl_C-EUC0805K"))
    )
    (comp (ref "C14")
      (value "560µ")
      (footprint "eagle-import:E2,5-6")
      (libsource (lib "eagle-import") (part "CPOL-EUE2.5-6"))
    )
    (comp (ref "C58")
      (value "C-EUC0603")
      (footprint "eagle-import:C0603")
      (libsource (lib "eagle-import") (part "resistor_C-EUC0603"))
    )
    (comp (ref "C60")
      (value "C-EUC0603")
      (footprint "eagle-import:C0603")
      (libsource (lib "eagle-import") (part "resistor_C-EUC0603"))
    )
    (comp (ref "C63")
      (value "22µ")
      (footprint "eagle-import:C0805K")
      (libsource (lib "eagle-import") (part "myrcl_C-EUC0805K"))
    )
    (comp (ref "C64")
      (value "10µ")
      (footprint "eagle-import:C1206")
      (libsource (lib "eagle-import") (part "myrcl_C-EUC1206"))
    )
    (comp (ref "C74")
      (value "C-EUC0603")
      (footprint "eagle-import:C0603")
      (libsource (lib "eagle-import") (part "resistor_C-EUC0603"))
    )
    (comp (ref "C75")
      (value "C-EUC0603")
      (footprint "eagle-import:C0603")
      (libsource (lib "eagle-import") (part "resistor_C-EUC0603"))
    )
    (comp (ref "D1")
      (value "DIODE-DO214AA")
      (footprint "eagle-import:DO214AA")
      (libsource (lib "eagle-import") (part "DIODE-DO214AA"))
    )
    (comp (ref "DC1")
      (value "NMA")
      (footprint "eagle-import:NMA")
      (fields (field (name "MF") "C & D TECHNOLOGIES, INC") (field (name "MPN") "NMA0515SC"))
      (libsource (lib "eagle-import") (part "NMA"))
    )
    (comp (ref "IC1")
      (value "AOZ1021")
      (footprint "eagle-import:AOZ1021")
      (libsource (lib "eagle-import") (part "AOZ1021"))
    )
    (comp (ref "IC2")
      (value "AOZ1021")
      (footprint "eagle-import:AOZ1021")
      (libsource (lib "eagle-import") (part "AOZ1021"))
    )
    (comp (ref "IC3")
      (value "AOZ1094")
      (footprint "eagle-import:AOZ1094.PAC")
      (libsource (lib "eagle-import") (part "AOZ1094"))
    )
    (comp (ref "IC6")
      (value "LM337L")
      (footprint "eagle-import:337L")
      (libsource (lib "eagle-import") (part "LM337L"))
    )
    (comp (ref "IC7")
      (value "LM317L")
      (footprint "eagle-import:317L")
      (libsource (lib "eagle-import") (part "LM317L"))
    )
    (comp (ref "JP6")
      (value "PINHD-1X2")
      (footprint "eagle-import:1X02")
      (libsource (lib "eagle-import") (part "PINHD-1X2"))
    )
    (comp (ref "L1")
      (value "4.7µ")
      (footprint "eagle-import:NR60")
      (libsource (lib "eagle-import") (part "L-EUNR60"))
    )
    (comp (ref "L3")
      (value "2.2uF")
      (footprint "eagle-import:DR1030")
      (fields (field (name "MPN") "CDRH104RNP-2R5NC"))
      (libsource (lib "eagle-import") (part "DR1030"))
    )
    (comp (ref "L4")
      (value "4.7µ")
      (footprint "eagle-import:NR60")
      (libsource (lib "eagle-import") (part "L-EUNR60"))
    )
    (comp (ref "R1")
      (value "7K5")
      (footprint "eagle-import:R0805K")
      (libsource (lib "eagle-import") (part "R-EU_R0805K"))
    )
    (comp (ref "R2")
      (value "7K5")
      (footprint "eagle-import:R0805K")
      (libsource (lib "eagle-import") (part "R-EU_R0805K"))
    )
    (comp (ref "R3")
      (value "7K5")
      (footprint "eagle-import:R0805K")
      (libsource (lib "eagle-import") (part "R-EU_R0805K"))
    )
    (comp (ref "R4")
      (value "2K4")
      (footprint "eagle-import:R0805K")
      (libsource (lib "eagle-import") (part "R-EU_R0805K"))
    )
    (comp (ref "R5")
      (value "7K5")
      (footprint "eagle-import:R0805K")
      (libsource (lib "eagle-import") (part "R-EU_R0805K"))
    )
    (comp (ref "R6")
      (value "7K5")
      (footprint "eagle-import:R0805K")
      (libsource (lib "eagle-import") (part "R-EU_R0805K"))
    )
    (comp (ref "R7")
      (value "5K36")
      (footprint "eagle-import:R0805K")
      (libsource (lib "eagle-import") (part "R-EU_R0805K"))
    )
    (comp (ref "R8")
      (value "2K4")
      (footprint "eagle-import:R0805K")
      (libsource (lib "eagle-import") (part "R-EU_R0805K"))
    )
    (comp (ref "R9")
      (value "25K")
      (footprint "eagle-import:R0805K")
      (libsource (lib "eagle-import") (part "R-EU_R0805K"))
    )
    (comp (ref "R10")
      (value "1K2")
      (footprint "eagle-import:R0805K")
      (libsource (lib "eagle-import") (part "R-EU_R0805K"))
    )
    (comp (ref "R11")
      (value "2K4")
      (footprint "eagle-import:R0805K")
      (libsource (lib "eagle-import") (part "R-EU_R0805K"))
    )
    (comp (ref "R12")
      (value "7K5")
      (footprint "eagle-import:R0805K")
      (libsource (lib "eagle-import") (part "R-EU_R0805K"))
    )
    (comp (ref "R48")
      (value "R-US_R0603")
      (footprint "eagle-import:R0603")
      (libsource (lib "eagle-import") (part "resistor_R-US_R0603"))
    )
    (comp (ref "R49")
      (value "R-US_R0603")
      (footprint "eagle-import:R0603")
      (libsource (lib "eagle-import") (part "resistor_R-US_R0603"))
    )
    (comp (ref "R50")
      (value "R-US_R0603")
      (footprint "eagle-import:R0603")
      (libsource (lib "eagle-import") (part "resistor_R-US_R0603"))
    )
    (comp (ref "R51")
      (value "R-US_R0603")
      (footprint "eagle-import:R0603")
      (libsource (lib "eagle-import") (part "resistor_R-US_R0603"))
    )
    (comp (ref "TP1")
      (value "TPSQPAD1-13")
      (footprint "eagle-import:P1-13")
      (libsource (lib "eagle-import") (part "TPSQPAD1-13"))
    )
    (comp (ref "TP2")
      (value "TPSQPAD1-13")
      (footprint "eagle-import:P1-13")
      (libsource (lib "eagle-import") (part "TPSQPAD1-13"))
    )
    (comp (ref "TP3")
      (value "PTR1PAD1-13")
      (footprint "eagle-import:P1-13")
      (libsource (lib "eagle-import") (part "PTR1PAD1-13"))
    )
    (comp (ref "TP4")
      (value "PTR1PAD1-13")
      (footprint "eagle-import:P1-13")
      (libsource (lib "eagle-import") (part "PTR1PAD1-13"))
    )
    (comp (ref "TP5")
      (value "PTR1PAD1-13")
      (footprint "eagle-import:P1-13")
      (libsource (lib "eagle-import") (part "PTR1PAD1-13"))
    )
    (comp (ref "TP6")
      (value "PTR1PAD1-13")
      (footprint "eagle-import:P1-13")
      (libsource (lib "eagle-import") (part "PTR1PAD1-13"))
    )
    (comp (ref "TP7")
      (value "PTR1PAD1-13")
      (footprint "eagle-import:P1-13")
      (libsource (lib "eagle-import") (part "PTR1PAD1-13"))
    )
    (comp (ref "TP8")
      (value "PTR1PAD1-13")
      (footprint "eagle-import:P1-13")
      (libsource (lib "eagle-import") (part "PTR1PAD1-13"))
    )
    (comp (ref "TP9")
      (value "PTR1PAD1-13")
      (footprint "eagle-import:P1-13")
      (libsource (lib "eagle-import") (part "PTR1PAD1-13"))
    )
  )
  (nets
    (net (code "2") (name "+1.2V") (class "Default")
      (node (ref "C11") (pin "2") (pinfunction "2_2") (pintype "passive"))
      (node (ref "C14") (pin "+") (pinfunction "+_+") (pintype "passive"))
      (node (ref "C9") (pin "2") (pinfunction "2_2") (pintype "passive"))
      (node (ref "CON6") (pin "A11") (pinfunction "A11~{1.2V}_A11") (pintype "bidirectional"))
      (node (ref "CON6") (pin "A23") (pinfunction "A23~{1.2V}_A23") (pintype "bidirectional"))
      (node (ref "CON6") (pin "B11") (pinfunction "B11~{1.2V}_B11") (pintype "bidirectional"))
      (node (ref "CON6") (pin "B23") (pinfunction "B23~{1.2V}_B23") (pintype "bidirectional"))
      (node (ref "CON6") (pin "C19") (pinfunction "C19~{1.2V}_C19") (pintype "bidirectional"))
      (node (ref "CON6") (pin "C28") (pinfunction "C28~{1.2V}_C28") (pintype "bidirectional"))
      (node (ref "CON6") (pin "D28") (pinfunction "D28~{1.2V}_D28") (pintype "bidirectional"))
      (node (ref "CON6") (pin "E10") (pinfunction "E10~{1.2V}_E10") (pintype "bidirectional"))
      (node (ref "CON6") (pin "E11") (pinfunction "E11~{1.2V}_E11") (pintype "bidirectional"))
      (node (ref "L3") (pin "2") (pinfunction "2_2") (pintype "passive"))
      (node (ref "R10") (pin "2") (pinfunction "2_2") (pintype "passive"))
      (node (ref "TP4") (pin "TP") (pinfunction "TP_TP") (pintype "input"))
    )
    (net (code "3") (name "+2.6V") (class "Default")
      (node (ref "C6") (pin "2") (pinfunction "2_2") (pintype "passive"))
      (node (ref "CON3") (pin "2") (pinfunction "VIO_2") (pintype "bidirectional"))
      (node (ref "CON6") (pin "A10") (pinfunction "A10~{2.5V}_A10") (pintype "bidirectional"))
      (node (ref "CON6") (pin "B10") (pinfunction "B10~{2.5V}_B10") (pintype "bidirectional"))
      (node (ref "CON6") (pin "C18") (pinfunction "C18~{2.5V}_C18") (pintype "bidirectional"))
      (node (ref "CON6") (pin "C29") (pinfunction "C29~{2.5V}_C29") (pintype "bidirectional"))
      (node (ref "CON6") (pin "D18") (pinfunction "D18~{2.5V}_D18") (pintype "bidirectional"))
      (node (ref "L4") (pin "P$2") (pinfunction "2_P$2") (pintype "passive"))
      (node (ref "R7") (pin "2") (pinfunction "2_2") (pintype "passive"))
      (node (ref "TP5") (pin "TP") (pinfunction "TP_TP") (pintype "input"))
    )
    (net (code "4") (name "+3V3") (class "Default")
      (node (ref "C13") (pin "1") (pinfunction "1_1") (pintype "passive"))
      (node (ref "C28") (pin "1") (pinfunction "1_1") (pintype "passive"))
      (node (ref "C29") (pin "1") (pinfunction "1_1") (pintype "passive"))
      (node (ref "C3") (pin "2") (pinfunction "2_2") (pintype "passive"))
      (node (ref "C47") (pin "1") (pinfunction "1_1") (pintype "passive"))
      (node (ref "C48") (pin "1") (pinfunction "1_1") (pintype "passive"))
      (node (ref "C49") (pin "1") (pinfunction "1_1") (pintype "passive"))
      (node (ref "C62") (pin "1") (pinfunction "1_1") (pintype "passive"))
      (node (ref "C65") (pin "1") (pinfunction "1_1") (pintype "passive"))
      (node (ref "C67") (pin "1") (pinfunction "1_1") (pintype "passive"))
      (node (ref "C81") (pin "1") (pinfunction "1_1") (pintype "passive"))
      (node (ref "C82") (pin "1") (pinfunction "1_1") (pintype "passive"))
      (node (ref "C83") (pin "1") (pinfunction "1_1") (pintype "passive"))
      (node (ref "CON6") (pin "A16") (pinfunction "A16~{3.3V}_A16") (pintype "bidirectional"))
      (node (ref "CON6") (pin "A22") (pinfunction "A22~{VCCO_IO}_A22") (pintype "bidirectional"))
      (node (ref "CON6") (pin "A31") (pinfunction "A31~{VCCO_IO}_A31") (pintype "bidirectional"))
      (node (ref "CON6") (pin "A7") (pinfunction "A7~{3.3V}_A7") (pintype "bidirectional"))
      (node (ref "CON6") (pin "B16") (pinfunction "B16~{3.3V}_B16") (pintype "bidirectional"))
      (node (ref "CON6") (pin "B22") (pinfunction "B22~{VCCO_IO}_B22") (pintype "bidirectional"))
      (node (ref "CON6") (pin "B31") (pinfunction "B31~{VCCO_IO}_B31") (pintype "bidirectional"))
      (node (ref "CON6") (pin "B7") (pinfunction "B7~{3.3V}_B7") (pintype "bidirectional"))
      (node (ref "CON6") (pin "C27") (pinfunction "C27~{VCCO_TOP}_C27") (pintype "bidirectional"))
      (node (ref "CON6") (pin "C6") (pinfunction "C6~{3.3V}_C6") (pintype "bidirectional"))
      (node (ref "CON6") (pin "C7") (pinfunction "C7~{VCCO_TOP}_C7") (pintype "bidirectional"))
      (node (ref "CON6") (pin "D27") (pinfunction "D27~{VCCO_TOP}_D27") (pintype "bidirectional"))
      (node (ref "CON6") (pin "D6") (pinfunction "D6~{3.3V}_D6") (pintype "bidirectional"))
      (node (ref "CON6") (pin "D7") (pinfunction "D7~{VCCO_TOP}_D7") (pintype "bidirectional"))
      (node (ref "CON6") (pin "E29") (pinfunction "E29~{3.3V}_E29") (pintype "bidirectional"))
      (node (ref "CON6") (pin "E30") (pinfunction "E30~{3.3V}_E30") (pintype "bidirectional"))
      (node (ref "D3") (pin "2") (pinfunction "C_2") (pintype "passive"))
      (node (ref "JP13") (pin "18") (pinfunction "18_18") (pintype "passive"))
      (node (ref "JP13") (pin "3") (pinfunction "3_3") (pintype "passive"))
      (node (ref "JP2") (pin "4") (pinfunction "4_4") (pintype "passive"))
      (node (ref "JP5") (pin "3") (pinfunction "3_3") (pintype "passive"))
      (node (ref "JP9") (pin "2") (pinfunction "2_2") (pintype "passive"))
      (node (ref "JP9") (pin "7") (pinfunction "7_7") (pintype "passive"))
      (node (ref "L1") (pin "P$2") (pinfunction "2_P$2") (pintype "passive"))
      (node (ref "L5") (pin "1") (pinfunction "1_1") (pintype "passive"))
      (node (ref "L9") (pin "2") (pinfunction "2_2") (pintype "passive"))
      (node (ref "R3") (pin "2") (pinfunction "2_2") (pintype "passive"))
      (node (ref "R43") (pin "2") (pinfunction "2_2") (pintype "passive"))
      (node (ref "R44") (pin "2") (pinfunction "2_2") (pintype "passive"))
      (node (ref "R59") (pin "1") (pinfunction "1_1") (pintype "passive"))
      (node (ref "R60") (pin "1") (pinfunction "1_1") (pintype "passive"))
      (node (ref "TP6") (pin "TP") (pinfunction "TP_TP") (pintype "input"))
      (node (ref "U$3") (pin "11") (pinfunction "DVCC_11") (pintype "bidirectional"))
      (node (ref "U$3") (pin "12") (pinfunction "DVCC_12") (pintype "bidirectional"))
      (node (ref "U$3") (pin "29") (pinfunction "AVCC_29") (pintype "bidirectional"))
      (node (ref "U$3") (pin "30") (pinfunction "AVCC_30") (pintype "bidirectional"))
      (node (ref "U$5") (pin "11") (pinfunction "DVCC_11") (pintype "bidirectional"))
      (node (ref "U$5") (pin "12") (pinfunction "DVCC_12") (pintype "bidirectional"))
      (node (ref "U$5") (pin "29") (pinfunction "AVCC_29") (pintype "bidirectional"))
      (node (ref "U$5") (pin "30") (pinfunction "AVCC_30") (pintype "bidirectional"))
      (node (ref "U1") (pin "24") (pinfunction "DRVDD_24") (pintype "bidirectional"))
      (node (ref "U5") (pin "14") (pinfunction "VCCOUT1_14") (pintype "output"))
      (node (ref "U5") (pin "18") (pinfunction "VCCOUT2_18") (pintype "output"))
      (node (ref "U5") (pin "3") (pinfunction "VCC_2_3") (pintype "power_in"))
      (node (ref "U5") (pin "7") (pinfunction "VCC_7") (pintype "power_in"))
      (node (ref "U6") (pin "1") (pinfunction "VCCA_1") (pintype "power_in"))
      (node (ref "U6") (pin "8") (pinfunction "OE_8") (pintype "input"))
      (node (ref "U8") (pin "1") (pinfunction "VCCA_1") (pintype "power_in"))
      (node (ref "U9") (pin "1") (pinfunction "VCCA_1") (pintype "power_in"))
    )
    (net (code "5") (name "+5V") (class "Default")
      (node (ref "C1") (pin "2") (pinfunction "2_2") (pintype "passive"))
      (node (ref "C4") (pin "2") (pinfunction "2_2") (pintype "passive"))
      (node (ref "C63") (pin "2") (pinfunction "2_2") (pintype "passive"))
      (node (ref "C64") (pin "2") (pinfunction "2_2") (pintype "passive"))
      (node (ref "C7") (pin "2") (pinfunction "2_2") (pintype "passive"))
      (node (ref "C8") (pin "2") (pinfunction "2_2") (pintype "passive"))
      (node (ref "DC1") (pin "1") (pinfunction "+VIN_1") (pintype "passive"))
      (node (ref "IC1") (pin "VIN") (pinfunction "VIN_VIN") (pintype "bidirectional"))
      (node (ref "IC2") (pin "VIN") (pinfunction "VIN_VIN") (pintype "bidirectional"))
      (node (ref "IC3") (pin "VIN") (pinfunction "VIN_VIN") (pintype "bidirectional"))
      (node (ref "JP13") (pin "1") (pinfunction "1_1") (pintype "passive"))
      (node (ref "JP13") (pin "20") (pinfunction "20_20") (pintype "passive"))
      (node (ref "JP5") (pin "1") (pinfunction "1_1") (pintype "passive"))
      (node (ref "JP6") (pin "2") (pinfunction "2_2") (pintype "passive"))
      (node (ref "JP9") (pin "1") (pinfunction "1_1") (pintype "passive"))
      (node (ref "JP9") (pin "8") (pinfunction "8_8") (pintype "passive"))
      (node (ref "R1") (pin "2") (pinfunction "2_2") (pintype "passive"))
      (node (ref "R12") (pin "2") (pinfunction "2_2") (pintype "passive"))
      (node (ref "R5") (pin "2") (pinfunction "2_2") (pintype "passive"))
      (node (ref "TP3") (pin "TP") (pinfunction "TP_TP") (pintype "input"))
    )
    (net (code "6") (name "+5V{slash}2") (class "Default")
      (node (ref "C66") (pin "1") (pinfunction "1_1") (pintype "passive"))
      (node (ref "C78") (pin "1") (pinfunction "1_1") (pintype "passive"))
      (node (ref "C79") (pin "1") (pinfunction "1_1") (pintype "passive"))
      (node (ref "C80") (pin "1") (pinfunction "1_1") (pintype "passive"))
      (node (ref "IC5") (pin "31") (pinfunction "UVCC_31") (pintype "bidirectional"))
      (node (ref "IC5") (pin "32") (pinfunction "AVCC_32") (pintype "bidirectional"))
      (node (ref "IC5") (pin "4") (pinfunction "VCC_4") (pintype "bidirectional"))
      (node (ref "JP6") (pin "1") (pinfunction "1_1") (pintype "passive"))
      (node (ref "R58") (pin "1") (pinfunction "1_1") (pintype "passive"))
      (node (ref "R61") (pin "2") (pinfunction "2_2") (pintype "passive"))
      (node (ref "U7") (pin "19") (pinfunction "VCCB_19") (pintype "power_in"))
      (node (ref "X5") (pin "1") (pinfunction "1_1") (pintype "passive"))
    )
    (net (code "7") (name "+9V") (class "Default")
      (node (ref "C58") (pin "1") (pinfunction "1_1") (pintype "passive"))
      (node (ref "IC7") (pin "2") (pinfunction "OUT_2") (pintype "passive"))
      (node (ref "JP2") (pin "1") (pinfunction "1_1") (pintype "passive"))
      (node (ref "R48") (pin "2") (pinfunction "2_2") (pintype "passive"))
      (node (ref "TP1") (pin "TP") (pinfunction "TP_TP") (pintype "input"))
    )
    (net (code "8") (name "-9V") (class "Default")
      (node (ref "C60") (pin "1") (pinfunction "1_1") (pintype "passive"))
      (node (ref "IC6") (pin "OUT") (pinfunction "OUT_OUT") (pintype "passive"))
      (node (ref "JP2") (pin "5") (pinfunction "5_5") (pintype "passive"))
      (node (ref "R50") (pin "2") (pinfunction "2_2") (pintype "passive"))
      (node (ref "TP2") (pin "TP") (pinfunction "TP_TP") (pintype "input"))
    )
    (net (code "10") (name "ADC_VCC") (class "Default")
      (node (ref "C31") (pin "1") (pinfunction "1_1") (pintype "passive"))
      (node (ref "C32") (pin "1") (pinfunction "1_1") (pintype "passive"))
      (node (ref "C34") (pin "1") (pinfunction "1_1") (pintype "passive"))
      (node (ref "C35") (pin "1") (pinfunction "1_1") (pintype "passive"))
      (node (ref "C36") (pin "1") (pinfunction "1_1") (pintype "passive"))
      (node (ref "R17") (pin "2") (pinfunction "2_2") (pintype "passive"))
      (node (ref "R19") (pin "1") (pinfunction "1_1") (pintype "passive"))
      (node (ref "R24") (pin "2") (pinfunction "2_2") (pintype "passive"))
      (node (ref "U1") (pin "12") (pinfunction "AVDD_12") (pintype "bidirectional"))
      (node (ref "U1") (pin "7") (pinfunction "AVDD_7") (pintype "bidirectional"))
      (node (ref "U3") (pin "5") (pinfunction "OUT_5") (pintype "passive"))
    )
    (net (code "11") (name "CLK_PLL0") (class "Default")
      (node (ref "CON6") (pin "D23") (pinfunction "D23~{AA10}IO_L32P_GCLK29_2_D23") (pintype "bidirectional"))
      (node (ref "JP8") (pin "1") (pinfunction "1_1") (pintype "passive"))
      (node (ref "U5") (pin "11") (pinfunction "Y0_11") (pintype "output"))
    )
    (net (code "12") (name "CLK_PLL1") (class "Default")
      (node (ref "CON6") (pin "C23") (pinfunction "C23~{AB10}IO_L32N_GCLK28_2_C23") (pintype "bidirectional"))
      (node (ref "JP8") (pin "2") (pinfunction "2_2") (pintype "passive"))
      (node (ref "U5") (pin "12") (pinfunction "Y1_12") (pintype "output"))
    )
    (net (code "13") (name "EXPIO5") (class "Default")
      (node (ref "CON6") (pin "A27") (pinfunction "A27~{C8}IO_L7N_0_A27") (pintype "bidirectional"))
      (node (ref "JP5") (pin "5") (pinfunction "5_5") (pintype "passive"))
    )
    (net (code "14") (name "EXPIO6") (class "Default")
      (node (ref "CON6") (pin "B26") (pinfunction "B26~{B8}IO_L6P_0_B26") (pintype "bidirectional"))
      (node (ref "JP5") (pin "6") (pinfunction "6_6") (pintype "passive"))
    )
    (net (code "15") (name "EXPIO7") (class "Default")
      (node (ref "CON6") (pin "A26") (pinfunction "A26~{A8}IO_L6N_0_A26") (pintype "bidirectional"))
      (node (ref "JP5") (pin "7") (pinfunction "7_7") (pintype "passive"))
    )
    (net (code "16") (name "EXPIO8") (class "Default")
      (node (ref "CON6") (pin "A25") (pinfunction "A25~{D8}IO_L32N_0_A25") (pintype "bidirectional"))
      (node (ref "JP5") (pin "8") (pinfunction "8_8") (pintype "passive"))
    )
    (net (code "17") (name "EXPIO9") (class "Default")
      (node (ref "CON6") (pin "B25") (pinfunction "B25~{D9}IO_L32P_0_B25") (pintype "bidirectional"))
      (node (ref "JP5") (pin "9") (pinfunction "9_9") (pintype "passive"))
    )
    (net (code "18") (name "EXPIO10") (class "Default")
      (node (ref "CON6") (pin "E25") (pinfunction "E25~{C7}IO_L5P_0_E25") (pintype "bidirectional"))
      (node (ref "JP5") (pin "10") (pinfunction "10_10") (pintype "passive"))
    )
    (net (code "19") (name "EXPIO11") (class "Default")
      (node (ref "CON6") (pin "A24") (pinfunction "A24~{C10}IO_L33N_0_A24") (pintype "bidirectional"))
      (node (ref "JP5") (pin "11") (pinfunction "11_11") (pintype "passive"))
    )
    (net (code "20") (name "EXPIO12") (class "Default")
      (node (ref "CON6") (pin "B24") (pinfunction "B24~{D10}IO_L33P_0_B24") (pintype "bidirectional"))
      (node (ref "JP5") (pin "12") (pinfunction "12_12") (pintype "passive"))
    )
    (net (code "21") (name "EXPIO13") (class "Default")
      (node (ref "CON6") (pin "E24") (pinfunction "E24~{C9}IO_L8P_0_E24") (pintype "bidirectional"))
      (node (ref "JP5") (pin "13") (pinfunction "13_13") (pintype "passive"))
    )
    (net (code "22") (name "EXPIO14") (class "Default")
      (node (ref "CON6") (pin "E23") (pinfunction "E23~{B10}IO_L34P_GCLK19_0_E23") (pintype "bidirectional"))
      (node (ref "JP5") (pin "14") (pinfunction "14_14") (pintype "passive"))
    )
    (net (code "23") (name "EXPIO15") (class "Default")
      (node (ref "CON6") (pin "E22") (pinfunction "E22~{A10}IO_L34N_GCLK18_0_E22") (pintype "bidirectional"))
      (node (ref "JP5") (pin "15") (pinfunction "15_15") (pintype "passive"))
    )
    (net (code "24") (name "EXPIO16") (class "Default")
      (node (ref "CON6") (pin "E21") (pinfunction "E21~{D13}IO_L47P_0_NC45_E21") (pintype "bidirectional"))
      (node (ref "JP5") (pin "16") (pinfunction "16_16") (pintype "passive"))
    )
    (net (code "25") (name "EXPIO17") (class "Default")
      (node (ref "CON6") (pin "E20") (pinfunction "E20~{D12}IO_L47N_0_NC45_E20") (pintype "bidirectional"))
      (node (ref "JP5") (pin "17") (pinfunction "17_17") (pintype "passive"))
    )
    (net (code "26") (name "EXPIO18") (class "Default")
      (node (ref "CON6") (pin "B20") (pinfunction "B20~{F10}IO_L38P_0_B20") (pintype "bidirectional"))
      (node (ref "JP5") (pin "18") (pinfunction "18_18") (pintype "passive"))
    )
    (net (code "27") (name "EXPIO19") (class "Default")
      (node (ref "CON6") (pin "A20") (pinfunction "A20~{C15}IO_L62P_0_A20") (pintype "bidirectional"))
      (node (ref "JP5") (pin "19") (pinfunction "19_19") (pintype "passive"))
    )
    (net (code "28") (name "EXPIO20") (class "Default")
      (node (ref "CON6") (pin "E19") (pinfunction "E19~{A14}IO_L50N_0_E19") (pintype "bidirectional"))
      (node (ref "JP5") (pin "20") (pinfunction "20_20") (pintype "passive"))
    )
    (net (code "29") (name "EXPIO21") (class "Default")
      (node (ref "CON6") (pin "B19") (pinfunction "B19~{D11}IO_L37P_GCLK13_0_B19") (pintype "bidirectional"))
      (node (ref "JP5") (pin "21") (pinfunction "21_21") (pintype "passive"))
    )
    (net (code "30") (name "EXPIO22") (class "Default")
      (node (ref "CON6") (pin "A19") (pinfunction "A19~{C12}IO_L37N_GCLK12_0_A19") (pintype "bidirectional"))
      (node (ref "JP5") (pin "22") (pinfunction "22_22") (pintype "passive"))
    )
    (net (code "31") (name "EXPIO23") (class "Default")
      (node (ref "CON6") (pin "A18") (pinfunction "A18~{C13}IO_L48P_0_A18") (pintype "bidirectional"))
      (node (ref "JP5") (pin "23") (pinfunction "23_23") (pintype "passive"))
    )
    (net (code "32") (name "EXPIO24") (class "Default")
      (node (ref "CON6") (pin "B18") (pinfunction "B18~{A13}IO_L48N_0_B18") (pintype "bidirectional"))
      (node (ref "JP5") (pin "24") (pinfunction "24_24") (pintype "passive"))
    )
    (net (code "33") (name "EXPIO25") (class "Default")
      (node (ref "CON6") (pin "E18") (pinfunction "E18~{B14}IO_L50P_0_E18") (pintype "bidirectional"))
      (node (ref "JP5") (pin "25") (pinfunction "25_25") (pintype "passive"))
    )
    (net (code "34") (name "EXPIO26") (class "Default")
      (node (ref "CON6") (pin "B17") (pinfunction "B17~{C11}IO_L35P_GCLK17_0_B17") (pintype "bidirectional"))
      (node (ref "JP5") (pin "26") (pinfunction "26_26") (pintype "passive"))
    )
    (net (code "35") (name "EXPIO27") (class "Default")
      (node (ref "CON6") (pin "A17") (pinfunction "A17~{A11}IO_L35N_GCLK16_0_A17") (pintype "bidirectional"))
      (node (ref "JP5") (pin "27") (pinfunction "27_27") (pintype "passive"))
    )
    (net (code "36") (name "EXPIO28") (class "Default")
      (node (ref "CON6") (pin "E17") (pinfunction "E17~{A12}IO_L36N_GCLK14_0_E17") (pintype "bidirectional"))
      (node (ref "JP5") (pin "28") (pinfunction "28_28") (pintype "passive"))
    )
    (net (code "37") (name "GND") (class "Default")
      (node (ref "C1") (pin "1") (pinfunction "1_1") (pintype "passive"))
      (node (ref "C10") (pin "1") (pinfunction "1_1") (pintype "passive"))
      (node (ref "C11") (pin "1") (pinfunction "1_1") (pintype "passive"))
      (node (ref "C13") (pin "2") (pinfunction "2_2") (pintype "passive"))
      (node (ref "C14") (pin "-") (pinfunction "-_-") (pintype "passive"))
      (node (ref "C18") (pin "2") (pinfunction "2_2") (pintype "passive"))
      (node (ref "C19") (pin "2") (pinfunction "2_2") (pintype "passive"))
      (node (ref "C2") (pin "1") (pinfunction "1_1") (pintype "passive"))
      (node (ref "C20") (pin "2") (pinfunction "2_2") (pintype "passive"))
      (node (ref "C21") (pin "2") (pinfunction "2_2") (pintype "passive"))
      (node (ref "C22") (pin "1") (pinfunction "1_1") (pintype "passive"))
      (node (ref "C24") (pin "2") (pinfunction "2_2") (pintype "passive"))
      (node (ref "C25") (pin "2") (pinfunction "2_2") (pintype "passive"))
      (node (ref "C26") (pin "2") (pinfunction "2_2") (pintype "passive"))
      (node (ref "C27") (pin "2") (pinfunction "2_2") (pintype "passive"))
      (node (ref "C28") (pin "2") (pinfunction "2_2") (pintype "passive"))
      (node (ref "C29") (pin "2") (pinfunction "2_2") (pintype "passive"))
      (node (ref "C3") (pin "1") (pinfunction "1_1") (pintype "passive"))
      (node (ref "C30") (pin "1") (pinfunction "1_1") (pintype "passive"))
      (node (ref "C31") (pin "2") (pinfunction "2_2") (pintype "passive"))
      (node (ref "C32") (pin "2") (pinfunction "2_2") (pintype "passive"))
      (node (ref "C33") (pin "2") (pinfunction "2_2") (pintype "passive"))
      (node (ref "C34") (pin "2") (pinfunction "2_2") (pintype "passive"))
      (node (ref "C35") (pin "2") (pinfunction "2_2") (pintype "passive"))
      (node (ref "C36") (pin "2") (pinfunction "2_2") (pintype "passive"))
      (node (ref "C39") (pin "1") (pinfunction "1_1") (pintype "passive"))
      (node (ref "C4") (pin "1") (pinfunction "1_1") (pintype "passive"))
      (node (ref "C40") (pin "1") (pinfunction "1_1") (pintype "passive"))
      (node (ref "C41") (pin "1") (pinfunction "1_1") (pintype "passive"))
      (node (ref "C42") (pin "1") (pinfunction "1_1") (pintype "passive"))
      (node (ref "C43") (pin "2") (pinfunction "2_2") (pintype "passive"))
      (node (ref "C44") (pin "2") (pinfunction "2_2") (pintype "passive"))
      (node (ref "C45") (pin "2") (pinfunction "2_2") (pintype "passive"))
      (node (ref "C47") (pin "2") (pinfunction "2_2") (pintype "passive"))
      (node (ref "C48") (pin "2") (pinfunction "2_2") (pintype "passive"))
      (node (ref "C49") (pin "2") (pinfunction "2_2") (pintype "passive"))
      (node (ref "C5") (pin "1") (pinfunction "1_1") (pintype "passive"))
      (node (ref "C50") (pin "2") (pinfunction "2_2") (pintype "passive"))
      (node (ref "C51") (pin "2") (pinfunction "2_2") (pintype "passive"))
      (node (ref "C52") (pin "2") (pinfunction "2_2") (pintype "passive"))
      (node (ref "C54") (pin "2") (pinfunction "2_2") (pintype "passive"))
      (node (ref "C55") (pin "2") (pinfunction "2_2") (pintype "passive"))
      (node (ref "C56") (pin "1") (pinfunction "1_1") (pintype "passive"))
      (node (ref "C57") (pin "1") (pinfunction "1_1") (pintype "passive"))
      (node (ref "C58") (pin "2") (pinfunction "2_2") (pintype "passive"))
      (node (ref "C59") (pin "1") (pinfunction "1_1") (pintype "passive"))
      (node (ref "C6") (pin "1") (pinfunction "1_1") (pintype "passive"))
      (node (ref "C60") (pin "2") (pinfunction "2_2") (pintype "passive"))
      (node (ref "C61") (pin "2") (pinfunction "2_2") (pintype "passive"))
      (node (ref "C62") (pin "2") (pinfunction "2_2") (pintype "passive"))
      (node (ref "C63") (pin "1") (pinfunction "1_1") (pintype "passive"))
      (node (ref "C64") (pin "1") (pinfunction "1_1") (pintype "passive"))
      (node (ref "C65") (pin "2") (pinfunction "2_2") (pintype "passive"))
      (node (ref "C66") (pin "2") (pinfunction "2_2") (pintype "passive"))
      (node (ref "C67") (pin "2") (pinfunction "2_2") (pintype "passive"))
      (node (ref "C68") (pin "2") (pinfunction "2_2") (pintype "passive"))
      (node (ref "C69") (pin "2") (pinfunction "2_2") (pintype "passive"))
      (node (ref "C7") (pin "1") (pinfunction "1_1") (pintype "passive"))
      (node (ref "C70") (pin "2") (pinfunction "2_2") (pintype "passive"))
      (node (ref "C71") (pin "2") (pinfunction "2_2") (pintype "passive"))
      (node (ref "C72") (pin "2") (pinfunction "2_2") (pintype "passive"))
      (node (ref "C73") (pin "2") (pinfunction "2_2") (pintype "passive"))
      (node (ref "C74") (pin "2") (pinfunction "2_2") (pintype "passive"))
      (node (ref "C75") (pin "1") (pinfunction "1_1") (pintype "passive"))
      (node (ref "C76") (pin "2") (pinfunction "2_2") (pintype "passive"))
      (node (ref "C77") (pin "2") (pinfunction "2_2") (pintype "passive"))
      (node (ref "C78") (pin "2") (pinfunction "2_2") (pintype "passive"))
      (node (ref "C79") (pin "2") (pinfunction "2_2") (pintype "passive"))
      (node (ref "C8") (pin "1") (pinfunction "1_1") (pintype "passive"))
      (node (ref "C80") (pin "2") (pinfunction "2_2") (pintype "passive"))
      (node (ref "C81") (pin "2") (pinfunction "2_2") (pintype "passive"))
      (node (ref "C82") (pin "2") (pinfunction "2_2") (pintype "passive"))
      (node (ref "C83") (pin "2") (pinfunction "2_2") (pintype "passive"))
      (node (ref "C84") (pin "2") (pinfunction "2_2") (pintype "passive"))
      (node (ref "C86") (pin "1") (pinfunction "1_1") (pintype "passive"))
      (node (ref "C87") (pin "1") (pinfunction "1_1") (pintype "passive"))
      (node (ref "C9") (pin "1") (pinfunction "1_1") (pintype "passive"))
      (node (ref "CON3") (pin "1") (pinfunction "GND1_1") (pintype "bidirectional"))
      (node (ref "CON3") (pin "11") (pinfunction "GND6_11") (pintype "bidirectional"))
      (node (ref "CON3") (pin "13") (pinfunction "GND7_13") (pintype "bidirectional"))
      (node (ref "CON3") (pin "3") (pinfunction "GND2_3") (pintype "bidirectional"))
      (node (ref "CON3") (pin "5") (pinfunction "GND3_5") (pintype "bidirectional"))
      (node (ref "CON3") (pin "7") (pinfunction "GND4_7") (pintype "bidirectional"))
      (node (ref "CON3") (pin "9") (pinfunction "GND5_9") (pintype "bidirectional"))
      (node (ref "CON6") (pin "A2") (pinfunction "A2~{GND}_A2") (pintype "bidirectional"))
      (node (ref "CON6") (pin "A21") (pinfunction "A21~{GND}_A21") (pintype "bidirectional"))
      (node (ref "CON6") (pin "A32") (pinfunction "A32~{GND}_A32") (pintype "bidirectional"))
      (node (ref "CON6") (pin "B13") (pinfunction "B13~{GND}_B13") (pintype "bidirectional"))
      (node (ref "CON6") (pin "B2") (pinfunction "B2~{GND}_B2") (pintype "bidirectional"))
      (node (ref "CON6") (pin "B21") (pinfunction "B21~{GND}_B21") (pintype "bidirectional"))
      (node (ref "CON6") (pin "B32") (pinfunction "B32~{GND}_B32") (pintype "bidirectional"))
      (node (ref "CON6") (pin "B5") (pinfunction "B5~{GND}_B5") (pintype "bidirectional"))
      (node (ref "CON6") (pin "C17") (pinfunction "C17~{GND}_C17") (pintype "bidirectional"))
      (node (ref "CON6") (pin "C26") (pinfunction "C26~{GND}_C26") (pintype "bidirectional"))
      (node (ref "CON6") (pin "C32") (pinfunction "C32~{GND}_C32") (pintype "bidirectional"))
      (node (ref "CON6") (pin "C4") (pinfunction "C4~{GND}_C4") (pintype "bidirectional"))
      (node (ref "CON6") (pin "C8") (pinfunction "C8~{GND}_C8") (pintype "bidirectional"))
      (node (ref "CON6") (pin "D26") (pinfunction "D26~{GND}_D26") (pintype "bidirectional"))
      (node (ref "CON6") (pin "D4") (pinfunction "D4~{GND}_D4") (pintype "bidirectional"))
      (node (ref "CON6") (pin "E31") (pinfunction "E31~{GND}_E31") (pintype "bidirectional"))
      (node (ref "CON6") (pin "E32") (pinfunction "E32~{GND}_E32") (pintype "bidirectional"))
      (node (ref "D1") (pin "A") (pinfunction "A_A") (pintype "passive"))
      (node (ref "D3") (pin "3") (pinfunction "A_3") (pintype "passive"))
      (node (ref "D4") (pin "2") (pinfunction "C_2") (pintype "passive"))
      (node (ref "DC1") (pin "2") (pinfunction "-VIN_2") (pintype "passive"))
      (node (ref "DC1") (pin "5") (pinfunction "COM_5") (pintype "passive"))
      (node (ref "IC1") (pin "AGND") (pinfunction "AGND_AGND") (pintype "bidirectional"))
      (node (ref "IC1") (pin "PGND") (pinfunction "PGND_PGND") (pintype "bidirectional"))
      (node (ref "IC2") (pin "AGND") (pinfunction "AGND_AGND") (pintype "bidirectional"))
      (node (ref "IC2") (pin "PGND") (pinfunction "PGND_PGND") (pintype "bidirectional"))
      (node (ref "IC3") (pin "AGND") (pinfunction "AGND_AGND") (pintype "bidirectional"))
      (node (ref "IC3") (pin "PGND") (pinfunction "PGND_PGND") (pintype "bidirectional"))
      (node (ref "IC5") (pin "28") (pinfunction "UGND_28") (pintype "bidirectional"))
      (node (ref "IC5") (pin "3") (pinfunction "GND_3") (pintype "bidirectional"))
      (node (ref "JP13") (pin "17") (pinfunction "17_17") (pintype "passive"))
      (node (ref "JP13") (pin "19") (pinfunction "19_19") (pintype "passive"))
      (node (ref "JP13") (pin "2") (pinfunction "2_2") (pintype "passive"))
      (node (ref "JP2") (pin "2") (pinfunction "2_2") (pintype "passive"))
      (node (ref "JP2") (pin "6") (pinfunction "6_6") (pintype "passive"))
      (node (ref "JP4") (pin "3") (pinfunction "3_3") (pintype "passive"))
      (node (ref "JP5") (pin "2") (pinfunction "2_2") (pintype "passive"))
      (node (ref "JP5") (pin "29") (pinfunction "29_29") (pintype "passive"))
      (node (ref "JP5") (pin "30") (pinfunction "30_30") (pintype "passive"))
      (node (ref "JP5") (pin "4") (pinfunction "4_4") (pintype "passive"))
      (node (ref "JP7") (pin "3") (pinfunction "3_3") (pintype "passive"))
      (node (ref "JP9") (pin "4") (pinfunction "4_4") (pintype "passive"))
      (node (ref "JP9") (pin "6") (pinfunction "6_6") (pintype "passive"))
      (node (ref "R11") (pin "1") (pinfunction "1_1") (pintype "passive"))
      (node (ref "R18") (pin "2") (pinfunction "2_2") (pintype "passive"))
      (node (ref "R20") (pin "1") (pinfunction "1_1") (pintype "passive"))
      (node (ref "R21") (pin "2") (pinfunction "2_2") (pintype "passive"))
      (node (ref "R23") (pin "2") (pinfunction "2_2") (pintype "passive"))
      (node (ref "R25") (pin "1") (pinfunction "1_1") (pintype "passive"))
      (node (ref "R26") (pin "1") (pinfunction "E_1") (pintype "passive"))
      (node (ref "R34") (pin "1") (pinfunction "1_1") (pintype "passive"))
      (node (ref "R4") (pin "1") (pinfunction "1_1") (pintype "passive"))
      (node (ref "R45") (pin "1") (pinfunction "1_1") (pintype "passive"))
      (node (ref "R46") (pin "1") (pinfunction "1_1") (pintype "passive"))
      (node (ref "R47") (pin "1") (pinfunction "1_1") (pintype "passive"))
      (node (ref "R49") (pin "1") (pinfunction "1_1") (pintype "passive"))
      (node (ref "R51") (pin "1") (pinfunction "1_1") (pintype "passive"))
      (node (ref "R52") (pin "2") (pinfunction "2_2") (pintype "passive"))
      (node (ref "R53") (pin "2") (pinfunction "2_2") (pintype "passive"))
      (node (ref "R54") (pin "2") (pinfunction "2_2") (pintype "passive"))
      (node (ref "R55") (pin "2") (pinfunction "2_2") (pintype "passive"))
      (node (ref "R56") (pin "2") (pinfunction "2_2") (pintype "passive"))
      (node (ref "R57") (pin "2") (pinfunction "2_2") (pintype "passive"))
      (node (ref "R8") (pin "1") (pinfunction "1_1") (pintype "passive"))
      (node (ref "SJ1") (pin "2") (pinfunction "2_2") (pintype "passive"))
      (node (ref "SJ2") (pin "2") (pinfunction "2_2") (pintype "passive"))
      (node (ref "T1") (pin "4") (pinfunction "P2_4") (pintype "passive"))
      (node (ref "TP7") (pin "TP") (pinfunction "TP_TP") (pintype "input"))
      (node (ref "TP8") (pin "TP") (pinfunction "TP_TP") (pintype "input"))
      (node (ref "TP9") (pin "TP") (pinfunction "TP_TP") (pintype "input"))
      (node (ref "U$3") (pin "10") (pinfunction "GND_10") (pintype "bidirectional"))
      (node (ref "U$3") (pin "27") (pinfunction "GND_27") (pintype "bidirectional"))
      (node (ref "U$3") (pin "28") (pinfunction "GND_28") (pintype "bidirectional"))
      (node (ref "U$3") (pin "9") (pinfunction "GND_9") (pintype "bidirectional"))
      (node (ref "U$5") (pin "10") (pinfunction "GND_10") (pintype "bidirectional"))
      (node (ref "U$5") (pin "27") (pinfunction "GND_27") (pintype "bidirectional"))
      (node (ref "U$5") (pin "28") (pinfunction "GND_28") (pintype "bidirectional"))
      (node (ref "U$5") (pin "9") (pinfunction "GND_9") (pintype "bidirectional"))
      (node (ref "U1") (pin "11") (pinfunction "AGND_11") (pintype "bidirectional"))
      (node (ref "U1") (pin "14") (pinfunction "PDWN_14") (pintype "bidirectional"))
      (node (ref "U1") (pin "23") (pinfunction "DRGND_23") (pintype "bidirectional"))
      (node (ref "U1") (pin "8") (pinfunction "AGND_8") (pintype "bidirectional"))
      (node (ref "U2") (pin "17") (pinfunction "COMM_17") (pintype "bidirectional"))
      (node (ref "U2") (pin "20") (pinfunction "COMM_20") (pintype "bidirectional"))
      (node (ref "U2") (pin "6") (pinfunction "COML_6") (pintype "bidirectional"))
      (node (ref "U2") (pin "9") (pinfunction "MODE_9") (pintype "bidirectional"))
      (node (ref "U3") (pin "2") (pinfunction "GND_2") (pintype "input"))
      (node (ref "U4") (pin "2") (pinfunction "GND_2") (pintype "bidirectional"))
      (node (ref "U5") (pin "13") (pinfunction "GND_3_13") (pintype "passive"))
      (node (ref "U5") (pin "17") (pinfunction "GND_17") (pintype "output"))
      (node (ref "U5") (pin "4") (pinfunction "GND_2_4") (pintype "passive"))
      (node (ref "U5") (pin "8") (pinfunction "GND_4_8") (pintype "passive"))
      (node (ref "U6") (pin "7") (pinfunction "GND_7") (pintype "passive"))
      (node (ref "U7") (pin "11") (pinfunction "GND_11") (pintype "passive"))
      (node (ref "U7") (pin "8") (pinfunction "A7_8") (pintype "bidirectional"))
      (node (ref "U7") (pin "9") (pinfunction "A8_9") (pintype "bidirectional"))
      (node (ref "U8") (pin "2") (pinfunction "GND_2") (pintype "passive"))
      (node (ref "U9") (pin "2") (pinfunction "GND_2") (pintype "passive"))
      (node (ref "X1") (pin "G@1") (pinfunction "2_G@1") (pintype "passive"))
      (node (ref "X1") (pin "G@2") (pinfunction "2_G@2") (pintype "passive"))
      (node (ref "X1") (pin "G@3") (pinfunction "2_G@3") (pintype "passive"))
      (node (ref "X1") (pin "G@4") (pinfunction "2_G@4") (pintype "passive"))
      (node (ref "X2") (pin "G@1") (pinfunction "2_G@1") (pintype "passive"))
      (node (ref "X2") (pin "G@2") (pinfunction "2_G@2") (pintype "passive"))
      (node (ref "X2") (pin "G@3") (pinfunction "2_G@3") (pintype "passive"))
      (node (ref "X2") (pin "G@4") (pinfunction "2_G@4") (pintype "passive"))
      (node (ref "X3") (pin "G@1") (pinfunction "2_G@1") (pintype "passive"))
      (node (ref "X3") (pin "G@2") (pinfunction "2_G@2") (pintype "passive"))
      (node (ref "X3") (pin "G@3") (pinfunction "2_G@3") (pintype "passive"))
      (node (ref "X3") (pin "G@4") (pinfunction "2_G@4") (pintype "passive"))
      (node (ref "X4") (pin "G@1") (pinfunction "2_G@1") (pintype "passive"))
      (node (ref "X4") (pin "G@2") (pinfunction "2_G@2") (pintype "passive"))
      (node (ref "X4") (pin "G@3") (pinfunction "2_G@3") (pintype "passive"))
      (node (ref "X4") (pin "G@4") (pinfunction "2_G@4") (pintype "passive"))
      (node (ref "X5") (pin "4") (pinfunction "4_4") (pintype "passive"))
      (node (ref "X5") (pin "S1") (pinfunction "S1_S1") (pintype "passive"))
      (node (ref "X5") (pin "S2") (pinfunction "S2_S2") (pintype "passive"))
    )
    (net (code "38") (name "HS1") (class "Default")
      (node (ref "CON6") (pin "E14") (pinfunction "E14~{B16}IO_L63P_SCP7_0_E14") (pintype "bidirectional"))
      (node (ref "U8") (pin "3") (pinfunction "A_3") (pintype "input"))
    )
    (net (code "39") (name "HS1DIR") (class "Default")
      (node (ref "CON6") (pin "A15") (pinfunction "A15~{C14}IO_L46N_0_A15") (pintype "bidirectional"))
      (node (ref "U8") (pin "5") (pinfunction "DIR_5") (pintype "input"))
    )
    (net (code "40") (name "HS2") (class "Default")
      (node (ref "CON6") (pin "A14") (pinfunction "A14~{A17}IO_L64N_SCP4_0_A14") (pintype "bidirectional"))
      (node (ref "U9") (pin "3") (pinfunction "A_3") (pintype "input"))
    )
    (net (code "41") (name "HS2DIR") (class "Default")
      (node (ref "CON6") (pin "B14") (pinfunction "B14~{C17}IO_L64P_SCP5_0_B14") (pintype "bidirectional"))
      (node (ref "U9") (pin "5") (pinfunction "DIR_5") (pintype "input"))
    )
    (net (code "42") (name "LED1") (class "Default")
      (node (ref "CON6") (pin "F16") (pinfunction "F16~{AA18}IO_L2P_CMPCLK_2_F16") (pintype "bidirectional"))
      (node (ref "LED1") (pin "A") (pinfunction "A_A") (pintype "passive"))
    )
    (net (code "43") (name "LED2") (class "Default")
      (node (ref "CON6") (pin "D17") (pinfunction "D17~{Y15}IO_L5P_2_D17") (pintype "bidirectional"))
      (node (ref "LED2") (pin "A") (pinfunction "A_A") (pintype "passive"))
    )
    (net (code "44") (name "LED3") (class "Default")
      (node (ref "CON6") (pin "F17") (pinfunction "F17~{AA16}IO_L4P_2_F17") (pintype "bidirectional"))
      (node (ref "LED3") (pin "A") (pinfunction "A_A") (pintype "passive"))
    )
    (net (code "45") (name "LED4") (class "Default")
      (node (ref "CON6") (pin "F18") (pinfunction "F18~{AB15}IO_L5N_2_F18") (pintype "bidirectional"))
      (node (ref "LED4") (pin "A") (pinfunction "A_A") (pintype "passive"))
    )
    (net (code "46") (name "LED5") (class "Default")
      (node (ref "CON6") (pin "D19") (pinfunction "D19~{V15}IO_L13N_D10_2_D19") (pintype "bidirectional"))
      (node (ref "LED5") (pin "A") (pinfunction "A_A") (pintype "passive"))
    )
    (net (code "47") (name "LED6") (class "Default")
      (node (ref "CON6") (pin "F19") (pinfunction "F19~{W14}IO_L16P_2_F19") (pintype "bidirectional"))
      (node (ref "LED6") (pin "A") (pinfunction "A_A") (pintype "passive"))
    )
    (net (code "48") (name "Net-(C2-Pad2)") (class "Default")
      (node (ref "C2") (pin "2") (pinfunction "2_2") (pintype "passive"))
      (node (ref "R2") (pin "1") (pinfunction "1_1") (pintype "passive"))
    )
    (net (code "49") (name "Net-(C5-Pad2)") (class "Default")
      (node (ref "C5") (pin "2") (pinfunction "2_2") (pintype "passive"))
      (node (ref "R6") (pin "1") (pinfunction "1_1") (pintype "passive"))
    )
    (net (code "50") (name "Net-(C10-Pad2)") (class "Default")
      (node (ref "C10") (pin "2") (pinfunction "2_2") (pintype "passive"))
      (node (ref "R9") (pin "1") (pinfunction "1_1") (pintype "passive"))
    )
    (net (code "51") (name "Net-(C12-Pad2)") (class "Default")
      (node (ref "C12") (pin "2") (pinfunction "2_2") (pintype "passive"))
      (node (ref "R15") (pin "1") (pinfunction "1_1") (pintype "passive"))
    )
    (net (code "52") (name "Net-(C15-Pad2)") (class "Default")
      (node (ref "C15") (pin "2") (pinfunction "2_2") (pintype "passive"))
      (node (ref "R16") (pin "1") (pinfunction "1_1") (pintype "passive"))
    )
    (net (code "53") (name "Net-(C23-Pad2)") (class "Default")
      (node (ref "C23") (pin "2") (pinfunction "2_2") (pintype "passive"))
      (node (ref "JP3") (pin "1") (pinfunction "1_1") (pintype "passive"))
    )
    (net (code "54") (name "Net-(C46-Pad2)") (class "Default")
      (node (ref "C46") (pin "2") (pinfunction "2_2") (pintype "passive"))
      (node (ref "L7") (pin "2") (pinfunction "2_2") (pintype "passive"))
    )
    (net (code "55") (name "Net-(C51-Pad1)") (class "Default")
      (node (ref "C51") (pin "1") (pinfunction "1_1") (pintype "passive"))
      (node (ref "R27") (pin "2") (pinfunction "2_2") (pintype "passive"))
      (node (ref "R28") (pin "1") (pinfunction "1_1") (pintype "passive"))
    )
    (net (code "56") (name "Net-(C53-Pad1)") (class "Default")
      (node (ref "C53") (pin "1") (pinfunction "1_1") (pintype "passive"))
      (node (ref "L8") (pin "1") (pinfunction "1_1") (pintype "passive"))
    )
    (net (code "57") (name "Net-(C53-Pad2)") (class "Default")
      (node (ref "C53") (pin "2") (pinfunction "2_2") (pintype "passive"))
      (node (ref "X1") (pin "1") (pinfunction "1_1") (pintype "passive"))
    )
    (net (code "58") (name "Net-(CON3-TCK)") (class "Default")
      (node (ref "CON3") (pin "6") (pinfunction "TCK_6") (pintype "bidirectional"))
      (node (ref "CON6") (pin "D31") (pinfunction "D31~{D14}TCK_D31") (pintype "bidirectional"))
    )
    (net (code "59") (name "Net-(CON3-TDI)") (class "Default")
      (node (ref "CON3") (pin "10") (pinfunction "TDI_10") (pintype "bidirectional"))
      (node (ref "CON6") (pin "D29") (pinfunction "D29~{E18}TDI_D29") (pintype "bidirectional"))
    )
    (net (code "60") (name "Net-(CON3-TDO)") (class "Default")
      (node (ref "CON3") (pin "8") (pinfunction "TDO_8") (pintype "bidirectional"))
      (node (ref "CON6") (pin "D32") (pinfunction "D32~{TDO}_D32") (pintype "bidirectional"))
    )
    (net (code "61") (name "Net-(CON3-TMS)") (class "Default")
      (node (ref "CON3") (pin "4") (pinfunction "TMS_4") (pintype "bidirectional"))
      (node (ref "CON6") (pin "D30") (pinfunction "D30~{E16}TMS_D30") (pintype "bidirectional"))
    )
    (net (code "62") (name "Net-(CON6D-C21~{AA12}IO_L30P_GCLK1_D13_2)") (class "Default")
      (node (ref "CON6") (pin "C21") (pinfunction "C21~{AA12}IO_L30P_GCLK1_D13_2_C21") (pintype "bidirectional"))
      (node (ref "U$5") (pin "24") (pinfunction "ADC0_24") (pintype "bidirectional"))
    )
    (net (code "63") (name "Net-(CON6D-C22~{Y10}IO_L29N_GCLK2_2)") (class "Default")
      (node (ref "CON6") (pin "C22") (pinfunction "C22~{Y10}IO_L29N_GCLK2_2_C22") (pintype "bidirectional"))
      (node (ref "U$5") (pin "20") (pinfunction "ADC4_20") (pintype "bidirectional"))
    )
    (net (code "64") (name "Net-(CON6D-C24~{Y13}IO_L41P_2)") (class "Default")
      (node (ref "CON6") (pin "C24") (pinfunction "C24~{Y13}IO_L41P_2_C24") (pintype "bidirectional"))
      (node (ref "U$5") (pin "7") (pinfunction "ADC5_7") (pintype "bidirectional"))
    )
    (net (code "65") (name "Net-(CON6D-C25~{W9}IO_L47P_2)") (class "Default")
      (node (ref "CON6") (pin "C25") (pinfunction "C25~{W9}IO_L47P_2_C25") (pintype "bidirectional"))
      (node (ref "U$5") (pin "4") (pinfunction "ADCOR_4") (pintype "bidirectional"))
    )
    (net (code "66") (name "Net-(CON6D-D20~{W15}IO_L14P_D11_2)") (class "Default")
      (node (ref "CON6") (pin "D20") (pinfunction "D20~{W15}IO_L14P_D11_2_D20") (pintype "bidirectional"))
      (node (ref "U$5") (pin "26") (pinfunction "HILO_26") (pintype "bidirectional"))
    )
    (net (code "67") (name "Net-(CON6D-D21~{AA14}IO_L15P_2)") (class "Default")
      (node (ref "CON6") (pin "D21") (pinfunction "D21~{AA14}IO_L15P_2_D21") (pintype "bidirectional"))
      (node (ref "U$5") (pin "23") (pinfunction "CLKADC_23") (pintype "bidirectional"))
    )
    (net (code "68") (name "Net-(CON6D-D22~{AB12}IO_L30N_GCLK0_USERCCLK_2)") (class "Default")
      (node (ref "CON6") (pin "D22") (pinfunction "D22~{AB12}IO_L30N_GCLK0_USERCCLK_2_D22") (pintype "bidirectional"))
      (node (ref "U$5") (pin "19") (pinfunction "ADC3_19") (pintype "bidirectional"))
    )
    (net (code "69") (name "Net-(CON6D-D24~{T14}IO_L20P_2)") (class "Default")
      (node (ref "CON6") (pin "D24") (pinfunction "D24~{T14}IO_L20P_2_D24") (pintype "bidirectional"))
      (node (ref "U$5") (pin "6") (pinfunction "ADC8_6") (pintype "bidirectional"))
    )
    (net (code "70") (name "Net-(CON6D-D25~{W12}IO_L42P_2)") (class "Default")
      (node (ref "CON6") (pin "D25") (pinfunction "D25~{W12}IO_L42P_2_D25") (pintype "bidirectional"))
      (node (ref "U$5") (pin "3") (pinfunction "ADC9_3") (pintype "bidirectional"))
    )
    (net (code "71") (name "Net-(CON6D-F20~{Y16}IO_L14N_D12_2)") (class "Default")
      (node (ref "CON6") (pin "F20") (pinfunction "F20~{Y16}IO_L14N_D12_2_F20") (pintype "bidirectional"))
      (node (ref "U$5") (pin "25") (pinfunction "GAIN_25") (pintype "bidirectional"))
    )
    (net (code "72") (name "Net-(CON6D-F21~{AB14}IO_L15N_2)") (class "Default")
      (node (ref "CON6") (pin "F21") (pinfunction "F21~{AB14}IO_L15N_2_F21") (pintype "bidirectional"))
      (node (ref "U$5") (pin "22") (pinfunction "ADC2_22") (pintype "bidirectional"))
    )
    (net (code "73") (name "Net-(CON6D-F22~{AB11}IO_L31N_GCLK30_D15_2)") (class "Default")
      (node (ref "CON6") (pin "F22") (pinfunction "F22~{AB11}IO_L31N_GCLK30_D15_2_F22") (pintype "bidirectional"))
      (node (ref "U$5") (pin "8") (pinfunction "ADC6_8") (pintype "bidirectional"))
    )
    (net (code "74") (name "Net-(CON6D-F23~{W11}IO_L29P_GCLK3_2)") (class "Default")
      (node (ref "CON6") (pin "F23") (pinfunction "F23~{W11}IO_L29P_GCLK3_2_F23") (pintype "bidirectional"))
      (node (ref "U$5") (pin "1") (pinfunction "CLKIN_1") (pintype "bidirectional"))
    )
    (net (code "75") (name "Net-(CON6D-F24~{U14}IO_L20N_2)") (class "Default")
      (node (ref "CON6") (pin "F24") (pinfunction "F24~{U14}IO_L20N_2_F24") (pintype "bidirectional"))
      (node (ref "U$5") (pin "5") (pinfunction "ADC7_5") (pintype "bidirectional"))
    )
    (net (code "76") (name "Net-(CON6D-F25~{Y12}IO_L42N_2)") (class "Default")
      (node (ref "CON6") (pin "F25") (pinfunction "F25~{Y12}IO_L42N_2_F25") (pintype "bidirectional"))
      (node (ref "U$5") (pin "2") (pinfunction "TRIGIN_2") (pintype "bidirectional"))
    )
    (net (code "77") (name "Net-(CON6F-C1~{USB_5V})") (class "Default")
      (node (ref "CON6") (pin "C1") (pinfunction "C1~{USB_5V}_C1") (pintype "bidirectional"))
      (node (ref "CON6") (pin "D1") (pinfunction "D1~{USB_5V}_D1") (pintype "bidirectional"))
      (node (ref "JP1") (pin "2") (pinfunction "2_2") (pintype "passive"))
    )
    (net (code "78") (name "Net-(CON6F-C2~{5V})") (class "Default")
      (node (ref "CON6") (pin "C2") (pinfunction "C2~{5V}_C2") (pintype "bidirectional"))
      (node (ref "CON6") (pin "D2") (pinfunction "D2~{5V}_D2") (pintype "bidirectional"))
      (node (ref "CON6") (pin "D3") (pinfunction "D3~{5V}_D3") (pintype "bidirectional"))
    )
    (net (code "79") (name "Net-(CON6F-F26~{VREF_3.3})") (class "Default")
      (node (ref "CON6") (pin "F26") (pinfunction "F26~{VREF_3.3}_F26") (pintype "bidirectional"))
      (node (ref "CON6") (pin "F32") (pinfunction "F32~{VREF_3.3}_F32") (pintype "bidirectional"))
    )
    (net (code "80") (name "Net-(D1-PadC)") (class "Default")
      (node (ref "D1") (pin "C") (pinfunction "C_C") (pintype "passive"))
      (node (ref "IC3") (pin "LX") (pinfunction "LX_LX") (pintype "bidirectional"))
      (node (ref "L3") (pin "1") (pinfunction "1_1") (pintype "passive"))
    )
    (net (code "81") (name "Net-(D4-A)") (class "Default")
      (node (ref "C52") (pin "1") (pinfunction "1_1") (pintype "passive"))
      (node (ref "D4") (pin "3") (pinfunction "A_3") (pintype "passive"))
      (node (ref "R28") (pin "2") (pinfunction "2_2") (pintype "passive"))
      (node (ref "U2") (pin "10") (pinfunction "GAIN_10") (pintype "bidirectional"))
    )
    (net (code "82") (name "Net-(DC1-+VOUT)") (class "Default")
      (node (ref "C74") (pin "1") (pinfunction "1_1") (pintype "passive"))
      (node (ref "DC1") (pin "6") (pinfunction "+VOUT_6") (pintype "passive"))
      (node (ref "IC7") (pin "3") (pinfunction "IN_3") (pintype "input"))
    )
    (net (code "83") (name "Net-(DC1--VOUT)") (class "Default")
      (node (ref "C75") (pin "2") (pinfunction "2_2") (pintype "passive"))
      (node (ref "DC1") (pin "4") (pinfunction "-VOUT_4") (pintype "passive"))
      (node (ref "IC6") (pin "IN") (pinfunction "IN_IN") (pintype "input"))
    )
    (net (code "84") (name "Net-(IC1-PadCOMP)") (class "Default")
      (node (ref "IC1") (pin "COMP") (pinfunction "COMP_COMP") (pintype "bidirectional"))
      (node (ref "R2") (pin "2") (pinfunction "2_2") (pintype "passive"))
    )
    (net (code "85") (name "Net-(IC1-PadEN)") (class "Default")
      (node (ref "IC1") (pin "EN") (pinfunction "EN_EN") (pintype "bidirectional"))
      (node (ref "R1") (pin "1") (pinfunction "1_1") (pintype "passive"))
    )
    (net (code "86") (name "Net-(IC1-PadFB)") (class "Default")
      (node (ref "IC1") (pin "FB") (pinfunction "FB_FB") (pintype "bidirectional"))
      (node (ref "R3") (pin "1") (pinfunction "1_1") (pintype "passive"))
      (node (ref "R4") (pin "2") (pinfunction "2_2") (pintype "passive"))
    )
    (net (code "87") (name "Net-(IC2-PadCOMP)") (class "Default")
      (node (ref "IC2") (pin "COMP") (pinfunction "COMP_COMP") (pintype "bidirectional"))
      (node (ref "R6") (pin "2") (pinfunction "2_2") (pintype "passive"))
    )
    (net (code "88") (name "Net-(IC2-PadEN)") (class "Default")
      (node (ref "IC2") (pin "EN") (pinfunction "EN_EN") (pintype "bidirectional"))
      (node (ref "R5") (pin "1") (pinfunction "1_1") (pintype "passive"))
    )
    (net (code "89") (name "Net-(IC2-PadFB)") (class "Default")
      (node (ref "IC2") (pin "FB") (pinfunction "FB_FB") (pintype "bidirectional"))
      (node (ref "R7") (pin "1") (pinfunction "1_1") (pintype "passive"))
      (node (ref "R8") (pin "2") (pinfunction "2_2") (pintype "passive"))
    )
    (net (code "90") (name "Net-(IC3-PadCOMP)") (class "Default")
      (node (ref "IC3") (pin "COMP") (pinfunction "COMP_COMP") (pintype "bidirectional"))
      (node (ref "R9") (pin "2") (pinfunction "2_2") (pintype "passive"))
    )
    (net (code "91") (name "Net-(IC3-PadEN)") (class "Default")
      (node (ref "IC3") (pin "EN") (pinfunction "EN_EN") (pintype "bidirectional"))
      (node (ref "R12") (pin "1") (pinfunction "1_1") (pintype "passive"))
    )
    (net (code "92") (name "Net-(IC3-PadFB)") (class "Default")
      (node (ref "IC3") (pin "FB") (pinfunction "FB_FB") (pintype "bidirectional"))
      (node (ref "R10") (pin "1") (pinfunction "1_1") (pintype "passive"))
      (node (ref "R11") (pin "2") (pinfunction "2_2") (pintype "passive"))
    )
    (net (code "93") (name "Net-(IC5-D+)") (class "Default")
      (node (ref "IC5") (pin "29") (pinfunction "D+_29") (pintype "bidirectional"))
      (node (ref "R40") (pin "2") (pinfunction "2_2") (pintype "passive"))
    )
    (net (code "94") (name "Net-(IC5-D-)") (class "Default")
      (node (ref "IC5") (pin "30") (pinfunction "D-_30") (pintype "bidirectional"))
      (node (ref "R39") (pin "2") (pinfunction "2_2") (pintype "passive"))
    )
    (net (code "95") (name "Net-(IC5-PC1({slash}RESET))") (class "Default")
      (node (ref "IC5") (pin "24") (pinfunction "PC1(/RESET)_24") (pintype "bidirectional"))
      (node (ref "R58") (pin "2") (pinfunction "2_2") (pintype "passive"))
      (node (ref "SJ2") (pin "1") (pinfunction "1_1") (pintype "passive"))
    )
    (net (code "96") (name "Net-(IC5-PD2(INT2{slash}AIN1{slash}RXD1))") (class "Default")
      (node (ref "IC5") (pin "8") (pinfunction "PD2(INT2/AIN1/RXD1)_8") (pintype "bidirectional"))
      (node (ref "R41") (pin "1") (pinfunction "1_1") (pintype "passive"))
    )
    (net (code "97") (name "Net-(IC5-PD3(INT3{slash}TXD1))") (class "Default")
      (node (ref "IC5") (pin "9") (pinfunction "PD3(INT3/TXD1)_9") (pintype "bidirectional"))
      (node (ref "R42") (pin "1") (pinfunction "1_1") (pintype "passive"))
    )
    (net (code "98") (name "Net-(IC5-PD7(INT7{slash}HWB{slash}CTS{slash}T0))") (class "Default")
      (node (ref "IC5") (pin "13") (pinfunction "PD7(INT7/HWB/CTS/T0)_13") (pintype "bidirectional"))
      (node (ref "SJ1") (pin "1") (pinfunction "1_1") (pintype "passive"))
    )
    (net (code "99") (name "Net-(IC5-UCAP)") (class "Default")
      (node (ref "C73") (pin "1") (pinfunction "1_1") (pintype "passive"))
      (node (ref "IC5") (pin "27") (pinfunction "UCAP_27") (pintype "bidirectional"))
    )
    (net (code "100") (name "Net-(IC5-XTAL1)") (class "Default")
      (node (ref "C76") (pin "1") (pinfunction "1_1") (pintype "passive"))
      (node (ref "IC5") (pin "1") (pinfunction "XTAL1_1") (pintype "bidirectional"))
      (node (ref "XTAL1") (pin "2") (pinfunction "2_2") (pintype "passive"))
    )
    (net (code "101") (name "Net-(IC5-XTAL2)") (class "Default")
      (node (ref "C77") (pin "1") (pinfunction "1_1") (pintype "passive"))
      (node (ref "IC5") (pin "2") (pinfunction "XTAL2_2") (pintype "bidirectional"))
      (node (ref "XTAL1") (pin "1") (pinfunction "1_1") (pintype "passive"))
    )
    (net (code "102") (name "Net-(IC6-PadADJ)") (class "Default")
      (node (ref "IC6") (pin "ADJ") (pinfunction "ADJ_ADJ") (pintype "input"))
      (node (ref "R50") (pin "1") (pinfunction "1_1") (pintype "passive"))
      (node (ref "R51") (pin "2") (pinfunction "2_2") (pintype "passive"))
    )
    (net (code "103") (name "Net-(IC7-ADJ)") (class "Default")
      (node (ref "IC7") (pin "1") (pinfunction "ADJ_1") (pintype "input"))
      (node (ref "R48") (pin "1") (pinfunction "1_1") (pintype "passive"))
      (node (ref "R49") (pin "2") (pinfunction "2_2") (pintype "passive"))
    )
    (net (code "104") (name "Net-(JP3-Pad2)") (class "Default")
      (node (ref "JP3") (pin "2") (pinfunction "2_2") (pintype "passive"))
      (node (ref "R22") (pin "1") (pinfunction "1_1") (pintype "passive"))
    )
    (net (code "105") (name "Net-(JP9-Pad3)") (class "Default")
      (node (ref "JP9") (pin "3") (pinfunction "3_3") (pintype "passive"))
      (node (ref "R33") (pin "1") (pinfunction "1_1") (pintype "passive"))
      (node (ref "X3") (pin "1") (pinfunction "1_1") (pintype "passive"))
    )
    (net (code "106") (name "Net-(JP9-Pad5)") (class "Default")
      (node (ref "JP9") (pin "5") (pinfunction "5_5") (pintype "passive"))
      (node (ref "R32") (pin "1") (pinfunction "1_1") (pintype "passive"))
    )
    (net (code "107") (name "Net-(L1-1)") (class "Default")
      (node (ref "IC1") (pin "LX") (pinfunction "LX_LX") (pintype "bidirectional"))
      (node (ref "L1") (pin "P$1") (pinfunction "1_P$1") (pintype "passive"))
    )
    (net (code "108") (name "Net-(L4-1)") (class "Default")
      (node (ref "IC2") (pin "LX") (pinfunction "LX_LX") (pintype "bidirectional"))
      (node (ref "L4") (pin "P$1") (pinfunction "1_P$1") (pintype "passive"))
    )
    (net (code "109") (name "Net-(L7-Pad1)") (class "Default")
      (node (ref "L7") (pin "1") (pinfunction "1_1") (pintype "passive"))
      (node (ref "X2") (pin "1") (pinfunction "1_1") (pintype "passive"))
    )
    (net (code "110") (name "Net-(LED1-C)") (class "Default")
      (node (ref "LED1") (pin "K") (pinfunction "C_K") (pintype "passive"))
      (node (ref "R52") (pin "1") (pinfunction "1_1") (pintype "passive"))
    )
    (net (code "111") (name "Net-(LED2-C)") (class "Default")
      (node (ref "LED2") (pin "K") (pinfunction "C_K") (pintype "passive"))
      (node (ref "R53") (pin "1") (pinfunction "1_1") (pintype "passive"))
    )
    (net (code "112") (name "Net-(LED3-C)") (class "Default")
      (node (ref "LED3") (pin "K") (pinfunction "C_K") (pintype "passive"))
      (node (ref "R54") (pin "1") (pinfunction "1_1") (pintype "passive"))
    )
    (net (code "113") (name "Net-(LED4-C)") (class "Default")
      (node (ref "LED4") (pin "K") (pinfunction "C_K") (pintype "passive"))
      (node (ref "R55") (pin "1") (pinfunction "1_1") (pintype "passive"))
    )
    (net (code "114") (name "Net-(LED5-C)") (class "Default")
      (node (ref "LED5") (pin "K") (pinfunction "C_K") (pintype "passive"))
      (node (ref "R56") (pin "1") (pinfunction "1_1") (pintype "passive"))
    )
    (net (code "115") (name "Net-(LED6-C)") (class "Default")
      (node (ref "LED6") (pin "K") (pinfunction "C_K") (pintype "passive"))
      (node (ref "R57") (pin "1") (pinfunction "1_1") (pintype "passive"))
    )
    (net (code "116") (name "Net-(R26-A)") (class "Default")
      (node (ref "C41") (pin "2") (pinfunction "2_2") (pintype "passive"))
      (node (ref "C42") (pin "2") (pinfunction "2_2") (pintype "passive"))
      (node (ref "R26") (pin "3") (pinfunction "A_3") (pintype "passive"))
      (node (ref "U1") (pin "4") (pinfunction "VREF_4") (pintype "bidirectional"))
    )
    (net (code "117") (name "Net-(R26-S)") (class "Default")
      (node (ref "JP4") (pin "1") (pinfunction "1_1") (pintype "passive"))
      (node (ref "R26") (pin "2") (pinfunction "S_2") (pintype "passive"))
    )
    (net (code "118") (name "Net-(R31-Pad1)") (class "Default")
      (node (ref "R31") (pin "1") (pinfunction "1_1") (pintype "passive"))
      (node (ref "R34") (pin "2") (pinfunction "2_2") (pintype "passive"))
      (node (ref "X4") (pin "1") (pinfunction "1_1") (pintype "passive"))
    )
    (net (code "119") (name "Net-(R39-Pad1)") (class "Default")
      (node (ref "R39") (pin "1") (pinfunction "1_1") (pintype "passive"))
      (node (ref "X5") (pin "2") (pinfunction "2_2") (pintype "passive"))
    )
    (net (code "120") (name "Net-(R40-Pad1)") (class "Default")
      (node (ref "R40") (pin "1") (pinfunction "1_1") (pintype "passive"))
      (node (ref "X5") (pin "3") (pinfunction "3_3") (pintype "passive"))
    )
    (net (code "121") (name "Net-(T1-P1)") (class "Default")
      (node (ref "L8") (pin "2") (pinfunction "2_2") (pintype "passive"))
      (node (ref "T1") (pin "6") (pinfunction "P1_6") (pintype "passive"))
    )
    (net (code "122") (name "Net-(T1-S1)") (class "Default")
      (node (ref "R13") (pin "2") (pinfunction "2_2") (pintype "passive"))
      (node (ref "R29") (pin "2") (pinfunction "2_2") (pintype "passive"))
      (node (ref "T1") (pin "1") (pinfunction "S1_1") (pintype "passive"))
    )
    (net (code "123") (name "Net-(T1-S2)") (class "Default")
      (node (ref "R14") (pin "2") (pinfunction "2_2") (pintype "passive"))
      (node (ref "R30") (pin "1") (pinfunction "1_1") (pintype "passive"))
      (node (ref "T1") (pin "3") (pinfunction "S2_3") (pintype "passive"))
    )
    (net (code "124") (name "Net-(T1-ST)") (class "Default")
      (node (ref "C54") (pin "1") (pinfunction "1_1") (pintype "passive"))
      (node (ref "C55") (pin "1") (pinfunction "1_1") (pintype "passive"))
      (node (ref "C56") (pin "2") (pinfunction "2_2") (pintype "passive"))
      (node (ref "C57") (pin "2") (pinfunction "2_2") (pintype "passive"))
      (node (ref "R29") (pin "1") (pinfunction "1_1") (pintype "passive"))
      (node (ref "R30") (pin "2") (pinfunction "2_2") (pintype "passive"))
      (node (ref "T1") (pin "2") (pinfunction "ST_2") (pintype "passive"))
    )
    (net (code "125") (name "Net-(U1-MODE)") (class "Default")
      (node (ref "R23") (pin "1") (pinfunction "1_1") (pintype "passive"))
      (node (ref "R24") (pin "1") (pinfunction "1_1") (pintype "passive"))
      (node (ref "U1") (pin "2") (pinfunction "MODE_2") (pintype "bidirectional"))
    )
    (net (code "126") (name "Net-(U1-REFB)") (class "Default")
      (node (ref "C37") (pin "1") (pinfunction "1_1") (pintype "passive"))
      (node (ref "C38") (pin "1") (pinfunction "1_1") (pintype "passive"))
      (node (ref "C39") (pin "2") (pinfunction "2_2") (pintype "passive"))
      (node (ref "U1") (pin "5") (pinfunction "REFB_5") (pintype "bidirectional"))
    )
    (net (code "127") (name "Net-(U1-REFT)") (class "Default")
      (node (ref "C37") (pin "2") (pinfunction "2_2") (pintype "passive"))
      (node (ref "C38") (pin "2") (pinfunction "2_2") (pintype "passive"))
      (node (ref "C40") (pin "2") (pinfunction "2_2") (pintype "passive"))
      (node (ref "U1") (pin "6") (pinfunction "REFT_6") (pintype "bidirectional"))
    )
    (net (code "128") (name "Net-(U1-SENSE)") (class "Default")
      (node (ref "C45") (pin "1") (pinfunction "1_1") (pintype "passive"))
      (node (ref "JP4") (pin "2") (pinfunction "2_2") (pintype "passive"))
      (node (ref "U1") (pin "3") (pinfunction "SENSE_3") (pintype "bidirectional"))
    )
    (net (code "129") (name "Net-(U1-VIN+)") (class "Default")
      (node (ref "C44") (pin "1") (pinfunction "1_1") (pintype "passive"))
      (node (ref "R13") (pin "1") (pinfunction "1_1") (pintype "passive"))
      (node (ref "R15") (pin "2") (pinfunction "2_2") (pintype "passive"))
      (node (ref "R19") (pin "2") (pinfunction "2_2") (pintype "passive"))
      (node (ref "R20") (pin "2") (pinfunction "2_2") (pintype "passive"))
      (node (ref "U1") (pin "9") (pinfunction "VIN+_9") (pintype "bidirectional"))
    )
    (net (code "130") (name "Net-(U1-VIN-)") (class "Default")
      (node (ref "C43") (pin "1") (pinfunction "1_1") (pintype "passive"))
      (node (ref "R14") (pin "1") (pinfunction "1_1") (pintype "passive"))
      (node (ref "R16") (pin "2") (pinfunction "2_2") (pintype "passive"))
      (node (ref "R17") (pin "1") (pinfunction "1_1") (pintype "passive"))
      (node (ref "R18") (pin "1") (pinfunction "1_1") (pintype "passive"))
      (node (ref "U1") (pin "10") (pinfunction "VIN-_10") (pintype "bidirectional"))
    )
    (net (code "131") (name "Net-(U2-ENBL)") (class "Default")
      (node (ref "C24") (pin "1") (pinfunction "1_1") (pintype "passive"))
      (node (ref "C25") (pin "1") (pinfunction "1_1") (pintype "passive"))
      (node (ref "C50") (pin "1") (pinfunction "1_1") (pintype "passive"))
      (node (ref "C59") (pin "2") (pinfunction "2_2") (pintype "passive"))
      (node (ref "L2") (pin "2") (pinfunction "2_2") (pintype "passive"))
      (node (ref "U2") (pin "18") (pinfunction "ENBV_18") (pintype "bidirectional"))
      (node (ref "U2") (pin "19") (pinfunction "ENBL_19") (pintype "bidirectional"))
      (node (ref "U2") (pin "3") (pinfunction "VPSL_3") (pintype "bidirectional"))
    )
    (net (code "132") (name "Net-(U2-INH)") (class "Default")
      (node (ref "C23") (pin "1") (pinfunction "1_1") (pintype "passive"))
      (node (ref "C46") (pin "1") (pinfunction "1_1") (pintype "passive"))
      (node (ref "C61") (pin "1") (pinfunction "1_1") (pintype "passive"))
      (node (ref "U2") (pin "2") (pinfunction "INH_2") (pintype "bidirectional"))
    )
    (net (code "133") (name "Net-(U2-LMD)") (class "Default")
      (node (ref "C22") (pin "2") (pinfunction "2_2") (pintype "passive"))
      (node (ref "U2") (pin "1") (pinfunction "LMD_1") (pintype "bidirectional"))
    )
    (net (code "134") (name "Net-(U2-LON)") (class "Default")
      (node (ref "C16") (pin "1") (pinfunction "1_1") (pintype "passive"))
      (node (ref "R22") (pin "2") (pinfunction "2_2") (pintype "passive"))
      (node (ref "U2") (pin "4") (pinfunction "LON_4") (pintype "bidirectional"))
    )
    (net (code "135") (name "Net-(U2-LOP)") (class "Default")
      (node (ref "C17") (pin "2") (pinfunction "2_2") (pintype "passive"))
      (node (ref "U2") (pin "5") (pinfunction "LOP_5") (pintype "bidirectional"))
    )
    (net (code "136") (name "Net-(U2-RCLMP)") (class "Default")
      (node (ref "C20") (pin "1") (pinfunction "1_1") (pintype "passive"))
      (node (ref "C21") (pin "1") (pinfunction "1_1") (pintype "passive"))
      (node (ref "R21") (pin "1") (pinfunction "1_1") (pintype "passive"))
      (node (ref "U2") (pin "12") (pinfunction "RCLMP_12") (pintype "bidirectional"))
    )
    (net (code "137") (name "Net-(U2-VCM)") (class "Default")
      (node (ref "C18") (pin "1") (pinfunction "1_1") (pintype "passive"))
      (node (ref "C19") (pin "1") (pinfunction "1_1") (pintype "passive"))
      (node (ref "U2") (pin "11") (pinfunction "VCM_11") (pintype "bidirectional"))
    )
    (net (code "138") (name "Net-(U2-VIN)") (class "Default")
      (node (ref "C16") (pin "2") (pinfunction "2_2") (pintype "passive"))
      (node (ref "U2") (pin "8") (pinfunction "VIN_8") (pintype "bidirectional"))
    )
    (net (code "139") (name "Net-(U2-VIP)") (class "Default")
      (node (ref "C17") (pin "1") (pinfunction "1_1") (pintype "passive"))
      (node (ref "U2") (pin "7") (pinfunction "VIP_7") (pintype "bidirectional"))
    )
    (net (code "140") (name "Net-(U2-VOH)") (class "Default")
      (node (ref "C12") (pin "1") (pinfunction "1_1") (pintype "passive"))
      (node (ref "U2") (pin "15") (pinfunction "VOH_15") (pintype "bidirectional"))
    )
    (net (code "141") (name "Net-(U2-VOL)") (class "Default")
      (node (ref "C15") (pin "1") (pinfunction "1_1") (pintype "passive"))
      (node (ref "U2") (pin "16") (pinfunction "VOL_16") (pintype "bidirectional"))
    )
    (net (code "142") (name "Net-(U2-VPOS)") (class "Default")
      (node (ref "C26") (pin "1") (pinfunction "1_1") (pintype "passive"))
      (node (ref "C27") (pin "1") (pinfunction "1_1") (pintype "passive"))
      (node (ref "L6") (pin "2") (pinfunction "2_2") (pintype "passive"))
      (node (ref "U2") (pin "14") (pinfunction "VPOS_14") (pintype "bidirectional"))
    )
    (net (code "143") (name "Net-(U3-BP)") (class "Default")
      (node (ref "C30") (pin "2") (pinfunction "2_2") (pintype "passive"))
      (node (ref "U3") (pin "4") (pinfunction "BP_4") (pintype "input"))
    )
    (net (code "144") (name "Net-(U3-EN)") (class "Default")
      (node (ref "C33") (pin "1") (pinfunction "1_1") (pintype "passive"))
      (node (ref "L5") (pin "2") (pinfunction "2_2") (pintype "passive"))
      (node (ref "U3") (pin "1") (pinfunction "IN_1") (pintype "input"))
      (node (ref "U3") (pin "3") (pinfunction "EN_3") (pintype "input"))
    )
    (net (code "145") (name "Net-(U4-C+)") (class "Default")
      (node (ref "C85") (pin "2") (pinfunction "2_2") (pintype "passive"))
      (node (ref "U4") (pin "6") (pinfunction "C+_6") (pintype "bidirectional"))
    )
    (net (code "146") (name "Net-(U4-C-)") (class "Default")
      (node (ref "C85") (pin "1") (pinfunction "1_1") (pintype "passive"))
      (node (ref "U4") (pin "4") (pinfunction "C-_4") (pintype "bidirectional"))
    )
    (net (code "147") (name "Net-(U4-VIN)") (class "Default")
      (node (ref "C86") (pin "2") (pinfunction "2_2") (pintype "passive"))
      (node (ref "L9") (pin "1") (pinfunction "1_1") (pintype "passive"))
      (node (ref "U4") (pin "3") (pinfunction "~{SHDN}_3") (pintype "bidirectional"))
      (node (ref "U4") (pin "5") (pinfunction "VIN_5") (pintype "bidirectional"))
    )
    (net (code "148") (name "Net-(U4-VOUT)") (class "Default")
      (node (ref "C84") (pin "1") (pinfunction "1_1") (pintype "passive"))
      (node (ref "C87") (pin "2") (pinfunction "2_2") (pintype "passive"))
      (node (ref "L2") (pin "1") (pinfunction "1_1") (pintype "passive"))
      (node (ref "L6") (pin "1") (pinfunction "1_1") (pintype "passive"))
      (node (ref "U4") (pin "1") (pinfunction "VOUT_1") (pintype "bidirectional"))
    )
    (net (code "149") (name "Net-(U5-CLK_IN0)") (class "Default")
      (node (ref "R32") (pin "2") (pinfunction "2_2") (pintype "passive"))
      (node (ref "R44") (pin "1") (pinfunction "1_1") (pintype "passive"))
      (node (ref "R46") (pin "2") (pinfunction "2_2") (pintype "passive"))
      (node (ref "U5") (pin "5") (pinfunction "CLK_IN0_5") (pintype "input"))
    )
    (net (code "150") (name "Net-(U5-CLK_IN1)") (class "Default")
      (node (ref "R33") (pin "2") (pinfunction "2_2") (pintype "passive"))
      (node (ref "R43") (pin "1") (pinfunction "1_1") (pintype "passive"))
      (node (ref "R45") (pin "2") (pinfunction "2_2") (pintype "passive"))
      (node (ref "U5") (pin "6") (pinfunction "CLK_IN1_6") (pintype "input"))
    )
    (net (code "151") (name "Net-(U6-B1)") (class "Default")
      (node (ref "JP13") (pin "10") (pinfunction "10_10") (pintype "passive"))
      (node (ref "U6") (pin "13") (pinfunction "B1_13") (pintype "bidirectional"))
    )
    (net (code "152") (name "Net-(U6-B2)") (class "Default")
      (node (ref "JP13") (pin "12") (pinfunction "12_12") (pintype "passive"))
      (node (ref "U6") (pin "12") (pinfunction "B2_12") (pintype "bidirectional"))
    )
    (net (code "153") (name "Net-(U6-B3)") (class "Default")
      (node (ref "JP13") (pin "14") (pinfunction "14_14") (pintype "passive"))
      (node (ref "U6") (pin "11") (pinfunction "B3_11") (pintype "bidirectional"))
    )
    (net (code "154") (name "Net-(U6-B4)") (class "Default")
      (node (ref "JP13") (pin "16") (pinfunction "16_16") (pintype "passive"))
      (node (ref "U6") (pin "10") (pinfunction "B4_10") (pintype "bidirectional"))
    )
    (net (code "155") (name "Net-(U6-VCCB)") (class "Default")
      (node (ref "C68") (pin "1") (pinfunction "1_1") (pintype "passive"))
      (node (ref "C69") (pin "1") (pinfunction "1_1") (pintype "passive"))
      (node (ref "C70") (pin "1") (pinfunction "1_1") (pintype "passive"))
      (node (ref "C71") (pin "1") (pinfunction "1_1") (pintype "passive"))
      (node (ref "C72") (pin "1") (pinfunction "1_1") (pintype "passive"))
      (node (ref "JP13") (pin "8") (pinfunction "8_8") (pintype "passive"))
      (node (ref "U6") (pin "14") (pinfunction "VCCB_14") (pintype "power_in"))
      (node (ref "U7") (pin "10") (pinfunction "OE_10") (pintype "input"))
      (node (ref "U7") (pin "2") (pinfunction "VCCA_2") (pintype "power_in"))
      (node (ref "U8") (pin "6") (pinfunction "VCCB_6") (pintype "power_in"))
      (node (ref "U9") (pin "6") (pinfunction "VCCB_6") (pintype "power_in"))
    )
    (net (code "156") (name "Net-(U7-A1)") (class "Default")
      (node (ref "JP13") (pin "15") (pinfunction "15_15") (pintype "passive"))
      (node (ref "U7") (pin "1") (pinfunction "A1_1") (pintype "bidirectional"))
    )
    (net (code "157") (name "Net-(U7-A2)") (class "Default")
      (node (ref "JP13") (pin "13") (pinfunction "13_13") (pintype "passive"))
      (node (ref "U7") (pin "3") (pinfunction "A2_3") (pintype "bidirectional"))
    )
    (net (code "158") (name "Net-(U7-A3)") (class "Default")
      (node (ref "JP13") (pin "11") (pinfunction "11_11") (pintype "passive"))
      (node (ref "U7") (pin "4") (pinfunction "A3_4") (pintype "bidirectional"))
    )
    (net (code "159") (name "Net-(U7-A4)") (class "Default")
      (node (ref "JP13") (pin "9") (pinfunction "9_9") (pintype "passive"))
      (node (ref "U7") (pin "5") (pinfunction "A4_5") (pintype "bidirectional"))
    )
    (net (code "160") (name "Net-(U7-A5)") (class "Default")
      (node (ref "JP13") (pin "7") (pinfunction "7_7") (pintype "passive"))
      (node (ref "U7") (pin "6") (pinfunction "A5_6") (pintype "bidirectional"))
    )
    (net (code "161") (name "Net-(U7-A6)") (class "Default")
      (node (ref "JP13") (pin "5") (pinfunction "5_5") (pintype "passive"))
      (node (ref "U7") (pin "7") (pinfunction "A6_7") (pintype "bidirectional"))
    )
    (net (code "162") (name "Net-(U8-B)") (class "Default")
      (node (ref "JP13") (pin "4") (pinfunction "4_4") (pintype "passive"))
      (node (ref "U8") (pin "4") (pinfunction "B_4") (pintype "output"))
    )
    (net (code "163") (name "Net-(U9-B)") (class "Default")
      (node (ref "JP13") (pin "6") (pinfunction "6_6") (pintype "passive"))
      (node (ref "U9") (pin "4") (pinfunction "B_4") (pintype "output"))
    )
    (net (code "164") (name "OA_ADC0") (class "Default")
      (node (ref "CON6") (pin "D10") (pinfunction "D10~{AA22}IO_L63N_1_D10") (pintype "bidirectional"))
      (node (ref "U$3") (pin "24") (pinfunction "ADC0_24") (pintype "bidirectional"))
      (node (ref "U1") (pin "17") (pinfunction "D0_17") (pintype "bidirectional"))
    )
    (net (code "165") (name "OA_ADC1") (class "Default")
      (node (ref "CON6") (pin "F11") (pinfunction "F11~{AB21}IO_L61N_1_F11") (pintype "bidirectional"))
      (node (ref "U$3") (pin "21") (pinfunction "ADC1_21") (pintype "bidirectional"))
      (node (ref "U1") (pin "18") (pinfunction "D1_18") (pintype "bidirectional"))
    )
    (net (code "166") (name "OA_ADC2") (class "Default")
      (node (ref "CON6") (pin "D11") (pinfunction "D11~{Y21}IO_L59P_1_D11") (pintype "bidirectional"))
      (node (ref "U$3") (pin "22") (pinfunction "ADC2_22") (pintype "bidirectional"))
      (node (ref "U1") (pin "19") (pinfunction "D2_19") (pintype "bidirectional"))
    )
    (net (code "167") (name "OA_ADC3") (class "Default")
      (node (ref "CON6") (pin "F12") (pinfunction "F12~{Y20}IO_L67N_1_F12") (pintype "bidirectional"))
      (node (ref "U$3") (pin "19") (pinfunction "ADC3_19") (pintype "bidirectional"))
      (node (ref "U1") (pin "20") (pinfunction "D3_20") (pintype "bidirectional"))
    )
    (net (code "168") (name "OA_ADC4") (class "Default")
      (node (ref "CON6") (pin "D12") (pinfunction "D12~{W20}IO_L53P_1_D12") (pintype "bidirectional"))
      (node (ref "U$3") (pin "20") (pinfunction "ADC4_20") (pintype "bidirectional"))
      (node (ref "U1") (pin "21") (pinfunction "D4_21") (pintype "bidirectional"))
    )
    (net (code "169") (name "OA_ADC5") (class "Default")
      (node (ref "CON6") (pin "F13") (pinfunction "F13~{AB20}IO_L65N_1_F13") (pintype "bidirectional"))
      (node (ref "U$3") (pin "7") (pinfunction "ADC5_7") (pintype "bidirectional"))
      (node (ref "U1") (pin "22") (pinfunction "D5_22") (pintype "bidirectional"))
    )
    (net (code "170") (name "OA_ADC6") (class "Default")
      (node (ref "CON6") (pin "D13") (pinfunction "D13~{AA20}IO_L61P_1_D13") (pintype "bidirectional"))
      (node (ref "U$3") (pin "8") (pinfunction "ADC6_8") (pintype "bidirectional"))
      (node (ref "U1") (pin "25") (pinfunction "D6_25") (pintype "bidirectional"))
    )
    (net (code "171") (name "OA_ADC7") (class "Default")
      (node (ref "CON6") (pin "F14") (pinfunction "F14~{AB19}IO_L65P_1_F14") (pintype "bidirectional"))
      (node (ref "U$3") (pin "5") (pinfunction "ADC7_5") (pintype "bidirectional"))
      (node (ref "U1") (pin "26") (pinfunction "D7_26") (pintype "bidirectional"))
    )
    (net (code "172") (name "OA_ADC8") (class "Default")
      (node (ref "CON6") (pin "D14") (pinfunction "D14~{V19}IO_L71P_1_D14") (pintype "bidirectional"))
      (node (ref "U$3") (pin "6") (pinfunction "ADC8_6") (pintype "bidirectional"))
      (node (ref "U1") (pin "27") (pinfunction "D8_27") (pintype "bidirectional"))
    )
    (net (code "173") (name "OA_ADC9") (class "Default")
      (node (ref "CON6") (pin "F15") (pinfunction "F15~{AB18}IO_L2N_CMPMOSI_2_F15") (pintype "bidirectional"))
      (node (ref "U$3") (pin "3") (pinfunction "ADC9_3") (pintype "bidirectional"))
      (node (ref "U1") (pin "28") (pinfunction "D9_28") (pintype "bidirectional"))
    )
    (net (code "174") (name "OA_ADCOR") (class "Default")
      (node (ref "CON6") (pin "D15") (pinfunction "D15~{Y19}IO_L67P_1_D15") (pintype "bidirectional"))
      (node (ref "U$3") (pin "4") (pinfunction "ADCOR_4") (pintype "bidirectional"))
      (node (ref "U1") (pin "1") (pinfunction "OR_1") (pintype "bidirectional"))
    )
    (net (code "175") (name "OA_CLKADC") (class "Default")
      (node (ref "CON6") (pin "F10") (pinfunction "F10~{AA21}IO_L63P_1_F10") (pintype "bidirectional"))
      (node (ref "R25") (pin "2") (pinfunction "2_2") (pintype "passive"))
      (node (ref "U$3") (pin "23") (pinfunction "CLKADC_23") (pintype "bidirectional"))
      (node (ref "U1") (pin "13") (pinfunction "CLK_13") (pintype "bidirectional"))
    )
    (net (code "176") (name "OA_CLKIN") (class "Default")
      (node (ref "CON6") (pin "C20") (pinfunction "C20~{Y11}IO_L31P_GCLK31_D14_2_C20") (pintype "bidirectional"))
      (node (ref "D3") (pin "1") (pinfunction "CA_1") (pintype "passive"))
      (node (ref "R31") (pin "2") (pinfunction "2_2") (pintype "passive"))
      (node (ref "R47") (pin "2") (pinfunction "2_2") (pintype "passive"))
      (node (ref "U$3") (pin "1") (pinfunction "CLKIN_1") (pintype "bidirectional"))
    )
    (net (code "177") (name "OA_GAIN") (class "Default")
      (node (ref "CON6") (pin "D9") (pinfunction "D9~{Y22}IO_L59N_1_D9") (pintype "bidirectional"))
      (node (ref "R27") (pin "1") (pinfunction "1_1") (pintype "passive"))
      (node (ref "U$3") (pin "25") (pinfunction "GAIN_25") (pintype "bidirectional"))
    )
    (net (code "178") (name "OA_HILO") (class "Default")
      (node (ref "CON6") (pin "D8") (pinfunction "D8~{V20}IO_L71N_1_D8") (pintype "bidirectional"))
      (node (ref "U$3") (pin "26") (pinfunction "HILO_26") (pintype "bidirectional"))
      (node (ref "U2") (pin "13") (pinfunction "HILO_13") (pintype "bidirectional"))
    )
    (net (code "179") (name "OA_TRIGIN") (class "Default")
      (node (ref "CON6") (pin "D16") (pinfunction "D16~{V18}IO_L73N_1_D16") (pintype "bidirectional"))
      (node (ref "U$3") (pin "2") (pinfunction "TRIGIN_2") (pintype "bidirectional"))
    )
    (net (code "180") (name "PLLSCL") (class "Default")
      (node (ref "CON6") (pin "A29") (pinfunction "A29~{A5}IO_L2N_0_A29") (pintype "bidirectional"))
      (node (ref "JP7") (pin "2") (pinfunction "2_2") (pintype "passive"))
      (node (ref "R60") (pin "2") (pinfunction "2_2") (pintype "passive"))
      (node (ref "U5") (pin "10") (pinfunction "SCLOCK_10") (pintype "input"))
    )
    (net (code "181") (name "PLLSDA") (class "Default")
      (node (ref "CON6") (pin "B29") (pinfunction "B29~{C5}IO_L2P_0_B29") (pintype "bidirectional"))
      (node (ref "JP7") (pin "1") (pinfunction "1_1") (pintype "passive"))
      (node (ref "R59") (pin "2") (pinfunction "2_2") (pintype "passive"))
      (node (ref "U5") (pin "9") (pinfunction "SDATA_9") (pintype "input"))
    )
    (net (code "182") (name "PRG_MISO") (class "Default")
      (node (ref "IC5") (pin "17") (pinfunction "PB3(PDO/MISO)_17") (pintype "bidirectional"))
      (node (ref "U7") (pin "15") (pinfunction "B5_15") (pintype "bidirectional"))
    )
    (net (code "183") (name "PRG_MOSI") (class "Default")
      (node (ref "IC5") (pin "16") (pinfunction "PB2(PDI/MISO)_16") (pintype "bidirectional"))
      (node (ref "U7") (pin "16") (pinfunction "B4_16") (pintype "bidirectional"))
    )
    (net (code "184") (name "PRG_PDIC") (class "Default")
      (node (ref "IC5") (pin "11") (pinfunction "PD5(XCK)_11") (pintype "bidirectional"))
      (node (ref "U7") (pin "18") (pinfunction "B2_18") (pintype "bidirectional"))
    )
    (net (code "185") (name "PRG_PDID") (class "Default")
      (node (ref "R41") (pin "2") (pinfunction "2_2") (pintype "passive"))
      (node (ref "R42") (pin "2") (pinfunction "2_2") (pintype "passive"))
      (node (ref "U7") (pin "20") (pinfunction "B1_20") (pintype "bidirectional"))
    )
    (net (code "186") (name "PRG_RST") (class "Default")
      (node (ref "IC5") (pin "18") (pinfunction "PB4(T1)_18") (pintype "bidirectional"))
      (node (ref "R61") (pin "1") (pinfunction "1_1") (pintype "passive"))
      (node (ref "U7") (pin "14") (pinfunction "B6_14") (pintype "bidirectional"))
    )
    (net (code "187") (name "PRG_SCK") (class "Default")
      (node (ref "IC5") (pin "15") (pinfunction "PB1(SCK)_15") (pintype "bidirectional"))
      (node (ref "U7") (pin "17") (pinfunction "B3_17") (pintype "bidirectional"))
    )
    (net (code "188") (name "TARGET1") (class "Default")
      (node (ref "CON6") (pin "E13") (pinfunction "E13~{C16}IO_L65N_SCP2_0_E13") (pintype "bidirectional"))
      (node (ref "U6") (pin "2") (pinfunction "A1_2") (pintype "bidirectional"))
    )
    (net (code "189") (name "TARGET2") (class "Default")
      (node (ref "CON6") (pin "A13") (pinfunction "A13~{D17}IO_L65P_SCP3_0_A13") (pintype "bidirectional"))
      (node (ref "U6") (pin "3") (pinfunction "A2_3") (pintype "bidirectional"))
    )
    (net (code "190") (name "TARGET3") (class "Default")
      (node (ref "CON6") (pin "B12") (pinfunction "B12~{B18}IO_L66P_SCP1_0_B12") (pintype "bidirectional"))
      (node (ref "U6") (pin "4") (pinfunction "A3_4") (pintype "bidirectional"))
    )
    (net (code "191") (name "TARGET4") (class "Default")
      (node (ref "CON6") (pin "A12") (pinfunction "A12~{A18}IO_L66N_SCP0_0_A12") (pintype "bidirectional"))
      (node (ref "U6") (pin "5") (pinfunction "A4_5") (pintype "bidirectional"))
    )
    (net (code "192") (name "VIN") (class "Default")
      (node (ref "CON6") (pin "A1") (pinfunction "A1~{4..35V}_A1") (pintype "bidirectional"))
      (node (ref "CON6") (pin "B1") (pinfunction "B1~{4..35V}_B1") (pintype "bidirectional"))
      (node (ref "JP1") (pin "1") (pinfunction "1_1") (pintype "passive"))
    )
    (net (code "193") (name "unconnected-(CON6A-A9~{A20}IO_L16N_1-PadA9)") (class "Default")
      (node (ref "CON6") (pin "A9") (pinfunction "A9~{A20}IO_L16N_1_A9") (pintype "bidirectional"))
    )
    (net (code "194") (name "unconnected-(CON6A-A28~{C6}IO_L3N_0-PadA28)") (class "Default")
      (node (ref "CON6") (pin "A28") (pinfunction "A28~{C6}IO_L3N_0_A28") (pintype "bidirectional"))
    )
    (net (code "195") (name "unconnected-(CON6A-A30~{B3}IO_L1P_HSWAPEN_0-PadA30)") (class "Default")
      (node (ref "CON6") (pin "A30") (pinfunction "A30~{B3}IO_L1P_HSWAPEN_0_A30") (pintype "bidirectional"))
    )
    (net (code "196") (name "unconnected-(CON6A-B9~{A19}IO_L16P_1-PadB9)") (class "Default")
      (node (ref "CON6") (pin "B9") (pinfunction "B9~{A19}IO_L16P_1_B9") (pintype "bidirectional"))
    )
    (net (code "197") (name "unconnected-(CON6A-B15~{D15}IO_L46P_0-PadB15)") (class "Default")
      (node (ref "CON6") (pin "B15") (pinfunction "B15~{D15}IO_L46P_0_B15") (pintype "bidirectional"))
    )
    (net (code "198") (name "unconnected-(CON6A-B27~{D7}IO_L7P_0-PadB27)") (class "Default")
      (node (ref "CON6") (pin "B27") (pinfunction "B27~{D7}IO_L7P_0_B27") (pintype "bidirectional"))
    )
    (net (code "199") (name "unconnected-(CON6A-B28~{D6}IO_L3P_0-PadB28)") (class "Default")
      (node (ref "CON6") (pin "B28") (pinfunction "B28~{D6}IO_L3P_0_B28") (pintype "bidirectional"))
    )
    (net (code "200") (name "unconnected-(CON6A-B30~{A6}IO_L4N_0-PadB30)") (class "Default")
      (node (ref "CON6") (pin "B30") (pinfunction "B30~{A6}IO_L4N_0_B30") (pintype "bidirectional"))
    )
    (net (code "201") (name "unconnected-(CON6A-E15~{A16}IO_L63N_SCP6_0-PadE15)") (class "Default")
      (node (ref "CON6") (pin "E15") (pinfunction "E15~{A16}IO_L63N_SCP6_0_E15") (pintype "bidirectional"))
    )
    (net (code "202") (name "unconnected-(CON6A-E16~{B12}IO_L36P_GCLK15_0-PadE16)") (class "Default")
      (node (ref "CON6") (pin "E16") (pinfunction "E16~{B12}IO_L36P_GCLK15_0_E16") (pintype "bidirectional"))
    )
    (net (code "203") (name "unconnected-(CON6A-E26~{A7}IO_L5N_0-PadE26)") (class "Default")
      (node (ref "CON6") (pin "E26") (pinfunction "E26~{A7}IO_L5N_0_E26") (pintype "bidirectional"))
    )
    (net (code "204") (name "unconnected-(CON6A-E27~{B6}IO_L4P_0-PadE27)") (class "Default")
      (node (ref "CON6") (pin "E27") (pinfunction "E27~{B6}IO_L4P_0_E27") (pintype "bidirectional"))
    )
    (net (code "205") (name "unconnected-(CON6C-E12~{VREF_IO}-PadE12)") (class "Default")
      (node (ref "CON6") (pin "E12") (pinfunction "E12~{VREF_IO}_E12") (pintype "bidirectional"))
    )
    (net (code "206") (name "unconnected-(CON6C-E28~{VREF_IO}-PadE28)") (class "Default")
      (node (ref "CON6") (pin "E28") (pinfunction "E28~{VREF_IO}_E28") (pintype "bidirectional"))
    )
    (net (code "207") (name "unconnected-(CON6D-C3~{L20}IO_L43P_GCLK5_M1DQ4_1-PadC3)") (class "Default")
      (node (ref "CON6") (pin "C3") (pinfunction "C3~{L20}IO_L43P_GCLK5_M1DQ4_1_C3") (pintype "bidirectional"))
    )
    (net (code "208") (name "unconnected-(CON6D-F27~{Y8}IO_L47N_2-PadF27)") (class "Default")
      (node (ref "CON6") (pin "F27") (pinfunction "F27~{Y8}IO_L47N_2_F27") (pintype "bidirectional"))
    )
    (net (code "209") (name "unconnected-(CON6D-F28~{AB7}IO_L63N_2-PadF28)") (class "Default")
      (node (ref "CON6") (pin "F28") (pinfunction "F28~{AB7}IO_L63N_2_F28") (pintype "bidirectional"))
    )
    (net (code "210") (name "unconnected-(CON6D-F29~{Y7}IO_L63P_2-PadF29)") (class "Default")
      (node (ref "CON6") (pin "F29") (pinfunction "F29~{Y7}IO_L63P_2_F29") (pintype "bidirectional"))
    )
    (net (code "211") (name "unconnected-(CON6D-F30~{AB6}IO_L64N_D9_2-PadF30)") (class "Default")
      (node (ref "CON6") (pin "F30") (pinfunction "F30~{AB6}IO_L64N_D9_2_F30") (pintype "bidirectional"))
    )
    (net (code "212") (name "unconnected-(CON6D-F31~{AA6}IO_L64P_D8_2-PadF31)") (class "Default")
      (node (ref "CON6") (pin "F31") (pinfunction "F31~{AA6}IO_L64P_D8_2_F31") (pintype "bidirectional"))
    )
    (net (code "213") (name "unconnected-(CON6G-C30~{M0}-PadC30)") (class "Default")
      (node (ref "CON6") (pin "C30") (pinfunction "C30~{M0}_C30") (pintype "bidirectional"))
    )
    (net (code "214") (name "unconnected-(CON6G-C31~{M1}-PadC31)") (class "Default")
      (node (ref "CON6") (pin "C31") (pinfunction "C31~{M1}_C31") (pintype "bidirectional"))
    )
    (net (code "215") (name "unconnected-(D4-CA-Pad1)") (class "Default")
      (node (ref "D4") (pin "1") (pinfunction "CA_1") (pintype "passive"))
    )
    (net (code "216") (name "unconnected-(H1-MOUNT-PadB2,8)") (class "Default")
      (node (ref "H1") (pin "B2,8") (pinfunction "MOUNT_B2,8") (pintype "passive"))
    )
    (net (code "217") (name "unconnected-(IC5-PB0(SS)-Pad14)") (class "Default")
      (node (ref "IC5") (pin "14") (pinfunction "PB0(SS)_14") (pintype "bidirectional"))
    )
    (net (code "218") (name "unconnected-(IC5-PB5-Pad19)") (class "Default")
      (node (ref "IC5") (pin "19") (pinfunction "PB5_19") (pintype "bidirectional"))
    )
    (net (code "219") (name "unconnected-(IC5-PB6-Pad20)") (class "Default")
      (node (ref "IC5") (pin "20") (pinfunction "PB6_20") (pintype "bidirectional"))
    )
    (net (code "220") (name "unconnected-(IC5-PB7(OC0A{slash}OC1C)-Pad21)") (class "Default")
      (node (ref "IC5") (pin "21") (pinfunction "PB7(OC0A/OC1C)_21") (pintype "bidirectional"))
    )
    (net (code "221") (name "unconnected-(IC5-PC2-Pad5)") (class "Default")
      (node (ref "IC5") (pin "5") (pinfunction "PC2_5") (pintype "bidirectional"))
    )
    (net (code "222") (name "unconnected-(IC5-PC4-Pad26)") (class "Default")
      (node (ref "IC5") (pin "26") (pinfunction "PC4_26") (pintype "bidirectional"))
    )
    (net (code "223") (name "unconnected-(IC5-PC5(OC1B)-Pad25)") (class "Default")
      (node (ref "IC5") (pin "25") (pinfunction "PC5(OC1B)_25") (pintype "bidirectional"))
    )
    (net (code "224") (name "unconnected-(IC5-PC6(OC1A)-Pad23)") (class "Default")
      (node (ref "IC5") (pin "23") (pinfunction "PC6(OC1A)_23") (pintype "bidirectional"))
    )
    (net (code "225") (name "unconnected-(IC5-PC7(ICP1{slash}INT4)-Pad22)") (class "Default")
      (node (ref "IC5") (pin "22") (pinfunction "PC7(ICP1/INT4)_22") (pintype "bidirectional"))
    )
    (net (code "226") (name "unconnected-(IC5-PD0(INT0{slash}OC0B)-Pad6)") (class "Default")
      (node (ref "IC5") (pin "6") (pinfunction "PD0(INT0/OC0B)_6") (pintype "bidirectional"))
    )
    (net (code "227") (name "unconnected-(IC5-PD1(INT1{slash}AIN0)-Pad7)") (class "Default")
      (node (ref "IC5") (pin "7") (pinfunction "PD1(INT1/AIN0)_7") (pintype "bidirectional"))
    )
    (net (code "228") (name "unconnected-(IC5-PD4(XCK{slash}T0)-Pad10)") (class "Default")
      (node (ref "IC5") (pin "10") (pinfunction "PD4(XCK/T0)_10") (pintype "bidirectional"))
    )
    (net (code "229") (name "unconnected-(IC5-PD6(INT6{slash}RTS)-Pad12)") (class "Default")
      (node (ref "IC5") (pin "12") (pinfunction "PD6(INT6/RTS)_12") (pintype "bidirectional"))
    )
    (net (code "230") (name "unconnected-(JP2-Pad3)") (class "Default")
      (node (ref "JP2") (pin "3") (pinfunction "3_3") (pintype "passive"))
    )
    (net (code "231") (name "unconnected-(U$3-NC-Pad13)") (class "Default")
      (node (ref "U$3") (pin "13") (pinfunction "NC_13") (pintype "bidirectional"))
    )
    (net (code "232") (name "unconnected-(U$3-NC-Pad14)") (class "Default")
      (node (ref "U$3") (pin "14") (pinfunction "NC_14") (pintype "bidirectional"))
    )
    (net (code "233") (name "unconnected-(U$3-NC-Pad15)") (class "Default")
      (node (ref "U$3") (pin "15") (pinfunction "NC_15") (pintype "bidirectional"))
    )
    (net (code "234") (name "unconnected-(U$3-NC-Pad16)") (class "Default")
      (node (ref "U$3") (pin "16") (pinfunction "NC_16") (pintype "bidirectional"))
    )
    (net (code "235") (name "unconnected-(U$3-NC-Pad17)") (class "Default")
      (node (ref "U$3") (pin "17") (pinfunction "NC_17") (pintype "bidirectional"))
    )
    (net (code "236") (name "unconnected-(U$3-NC-Pad18)") (class "Default")
      (node (ref "U$3") (pin "18") (pinfunction "NC_18") (pintype "bidirectional"))
    )
    (net (code "237") (name "unconnected-(U$5-ADC1-Pad21)") (class "Default")
      (node (ref "U$5") (pin "21") (pinfunction "ADC1_21") (pintype "bidirectional"))
    )
    (net (code "238") (name "unconnected-(U$5-NC-Pad13)") (class "Default")
      (node (ref "U$5") (pin "13") (pinfunction "NC_13") (pintype "bidirectional"))
    )
    (net (code "239") (name "unconnected-(U$5-NC-Pad14)") (class "Default")
      (node (ref "U$5") (pin "14") (pinfunction "NC_14") (pintype "bidirectional"))
    )
    (net (code "240") (name "unconnected-(U$5-NC-Pad15)") (class "Default")
      (node (ref "U$5") (pin "15") (pinfunction "NC_15") (pintype "bidirectional"))
    )
    (net (code "241") (name "unconnected-(U$5-NC-Pad16)") (class "Default")
      (node (ref "U$5") (pin "16") (pinfunction "NC_16") (pintype "bidirectional"))
    )
    (net (code "242") (name "unconnected-(U$5-NC-Pad17)") (class "Default")
      (node (ref "U$5") (pin "17") (pinfunction "NC_17") (pintype "bidirectional"))
    )
    (net (code "243") (name "unconnected-(U$5-NC-Pad18)") (class "Default")
      (node (ref "U$5") (pin "18") (pinfunction "NC_18") (pintype "bidirectional"))
    )
    (net (code "244") (name "unconnected-(U5-S0{slash}A0{slash}CLK_SEL-Pad1)") (class "Default")
      (node (ref "U5") (pin "1") (pinfunction "S0/A0/CLK_SEL_1") (pintype "input"))
    )
    (net (code "245") (name "unconnected-(U5-S1{slash}A1-Pad2)") (class "Default")
      (node (ref "U5") (pin "2") (pinfunction "S1/A1_2") (pintype "input"))
    )
    (net (code "246") (name "unconnected-(U5-Y2-Pad15)") (class "Default")
      (node (ref "U5") (pin "15") (pinfunction "Y2_15") (pintype "output"))
    )
    (net (code "247") (name "unconnected-(U5-Y3-Pad16)") (class "Default")
      (node (ref "U5") (pin "16") (pinfunction "Y3_16") (pintype "output"))
    )
    (net (code "248") (name "unconnected-(U5-Y4-Pad19)") (class "Default")
      (node (ref "U5") (pin "19") (pinfunction "Y4_19") (pintype "output"))
    )
    (net (code "249") (name "unconnected-(U5-Y5-Pad20)") (class "Default")
      (node (ref "U5") (pin "20") (pinfunction "Y5_20") (pintype "output"))
    )
    (net (code "250") (name "unconnected-(U6-NC-Pad6)") (class "Default")
      (node (ref "U6") (pin "6") (pinfunction "NC_6") (pintype "no_connect"))
    )
    (net (code "251") (name "unconnected-(U6-NC_2-Pad9)") (class "Default")
      (node (ref "U6") (pin "9") (pinfunction "NC_2_9") (pintype "no_connect"))
    )
    (net (code "252") (name "unconnected-(U7-B7-Pad13)") (class "Default")
      (node (ref "U7") (pin "13") (pinfunction "B7_13") (pintype "bidirectional"))
    )
    (net (code "253") (name "unconnected-(U7-B8-Pad12)") (class "Default")
      (node (ref "U7") (pin "12") (pinfunction "B8_12") (pintype "bidirectional"))
    )
  )
)
